# tc08.net
KiCad netlist of a schematic drawn in EAGLE
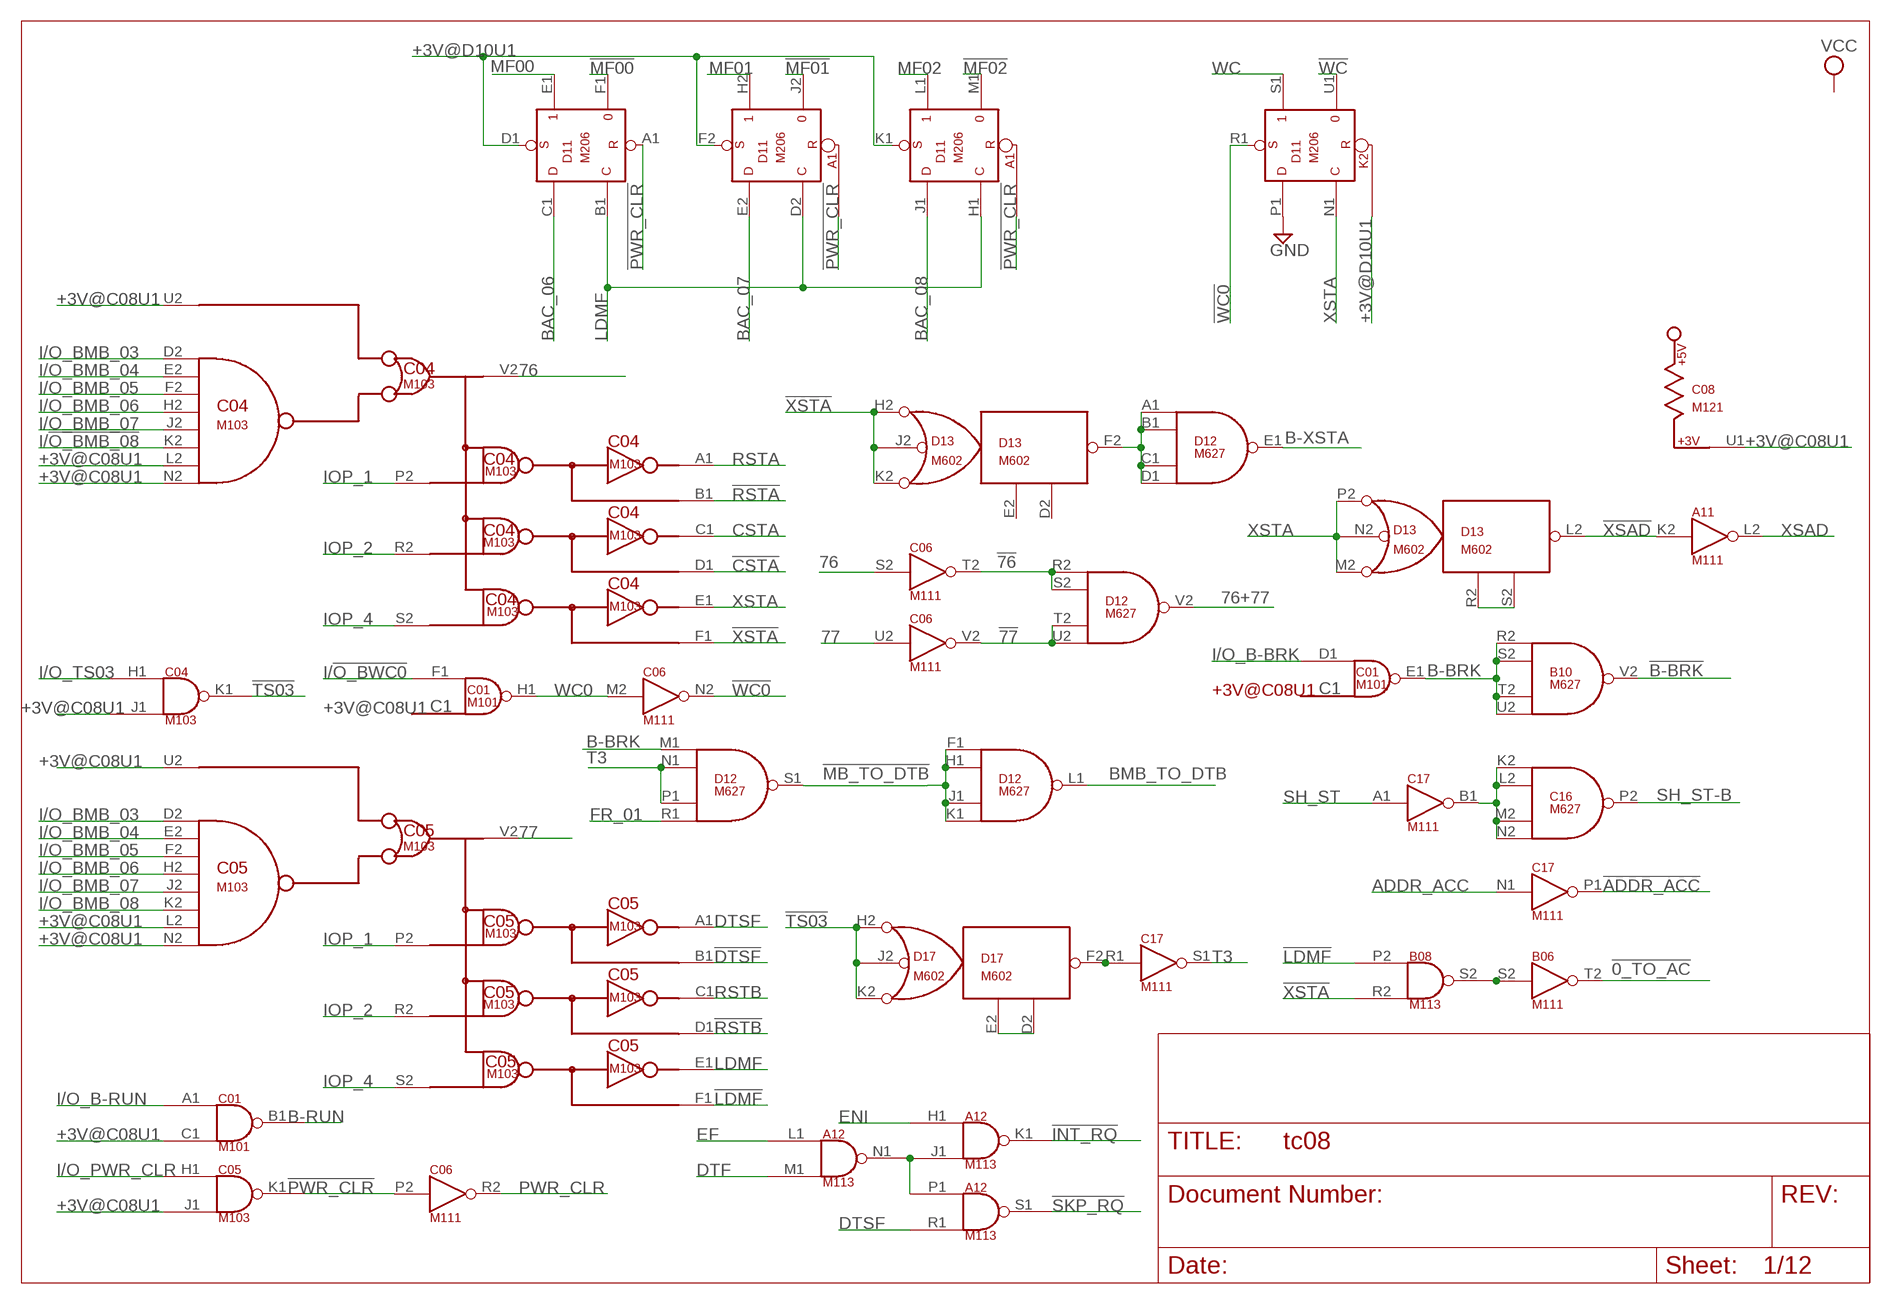
[diagram p0: schematic, sheet 1]
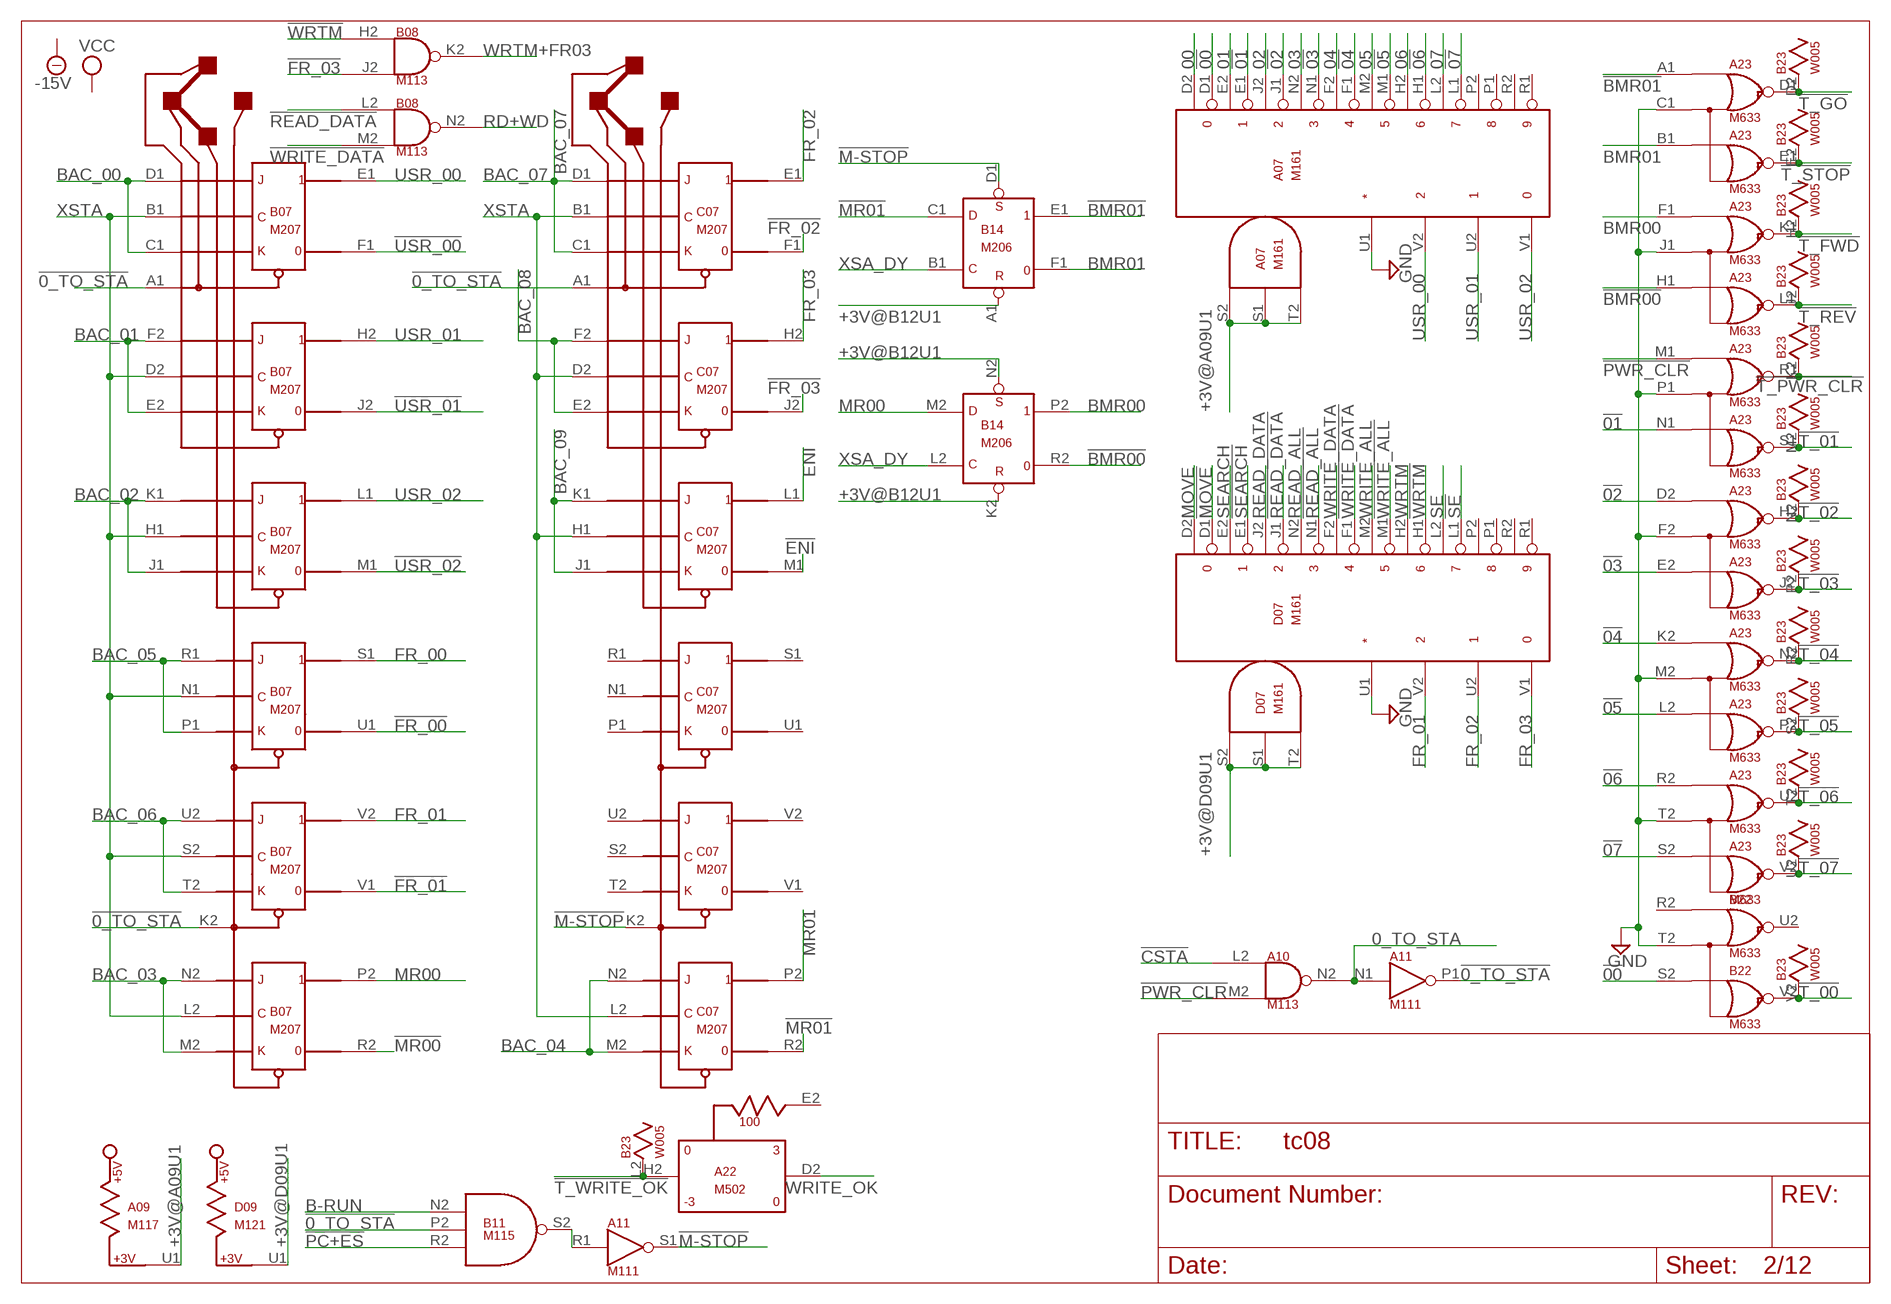
[diagram p1: schematic, sheet 2]
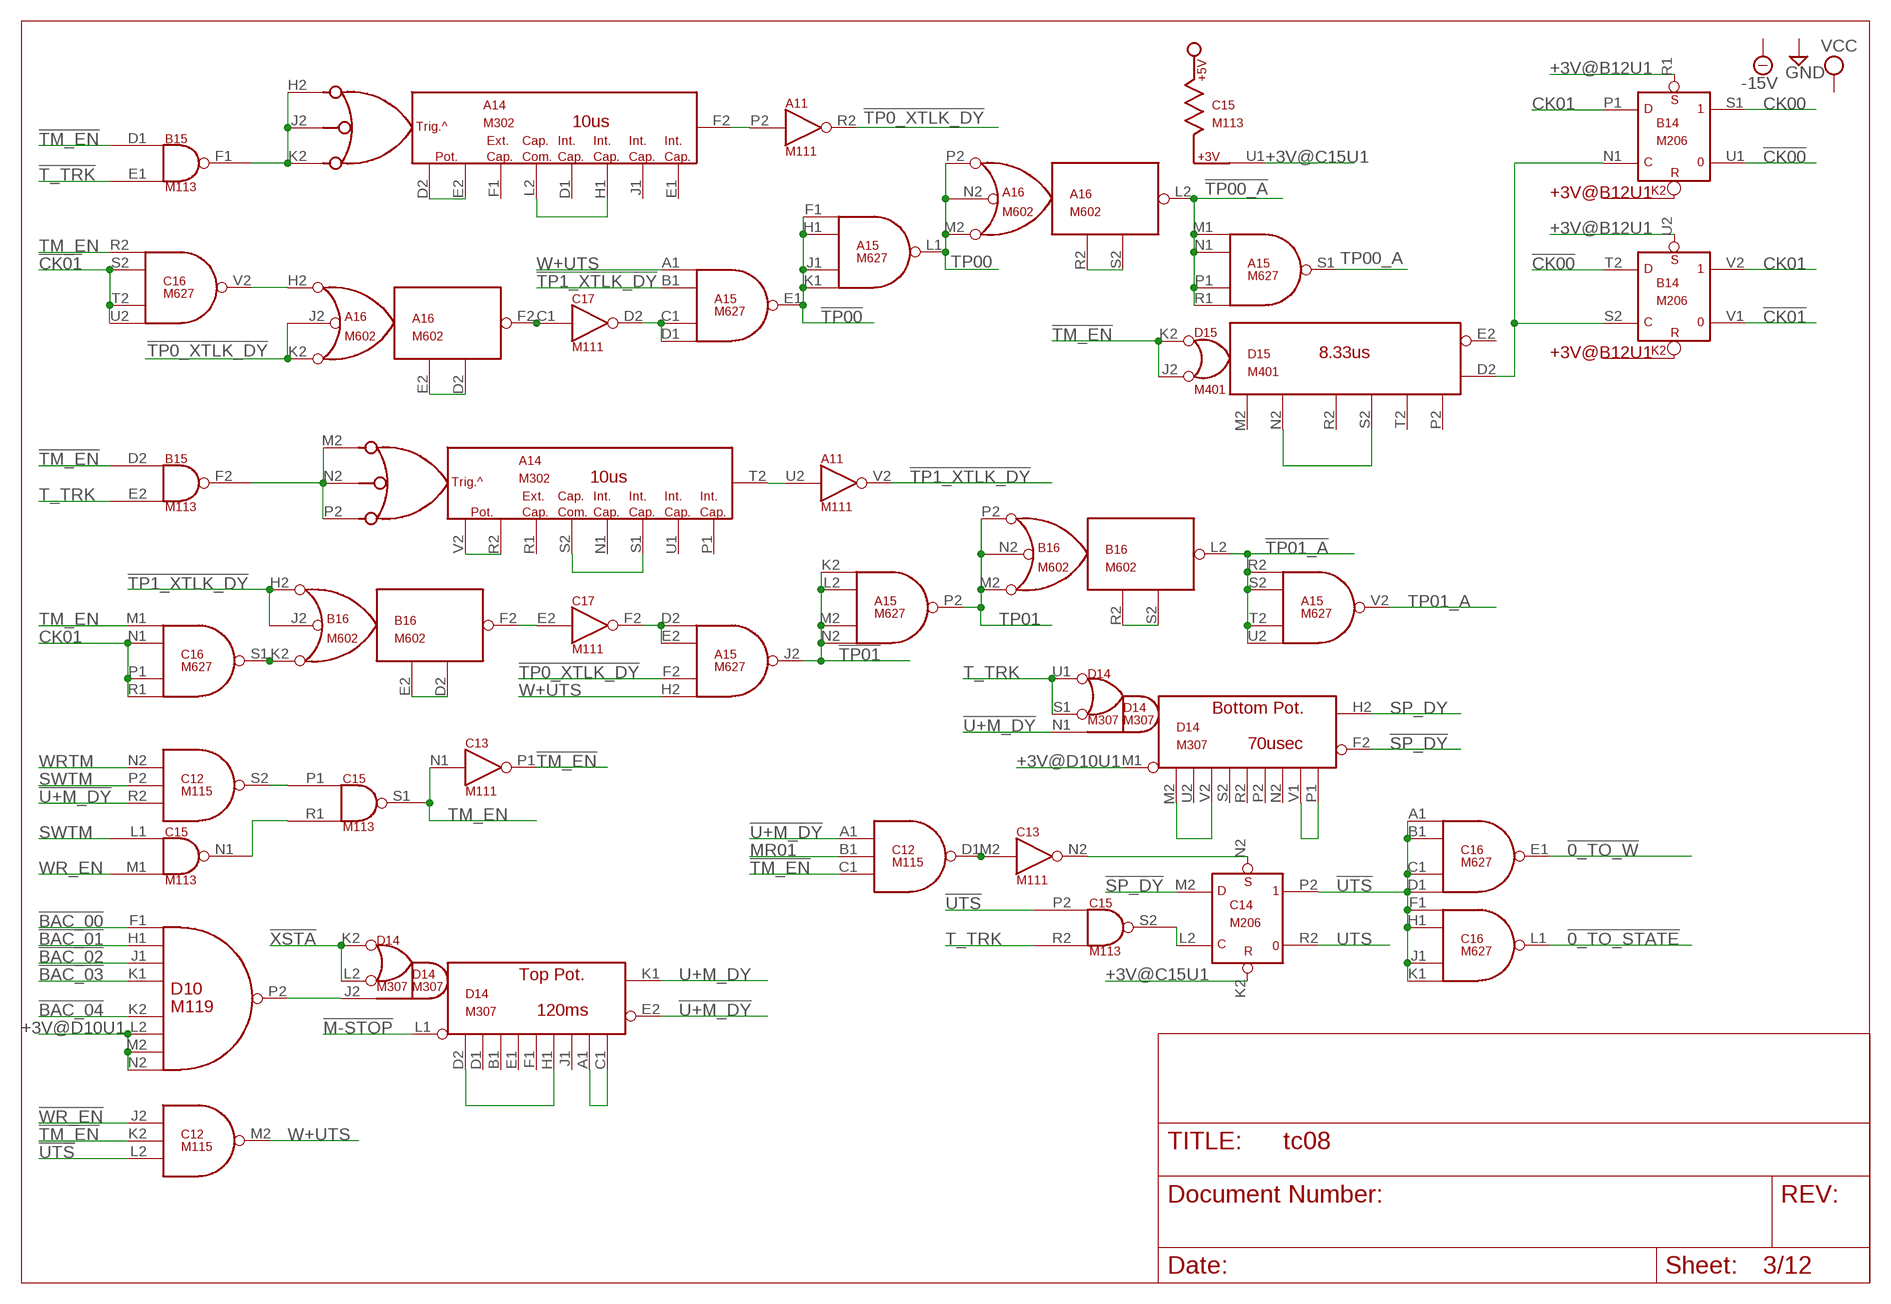
[diagram p2: schematic, sheet 3]
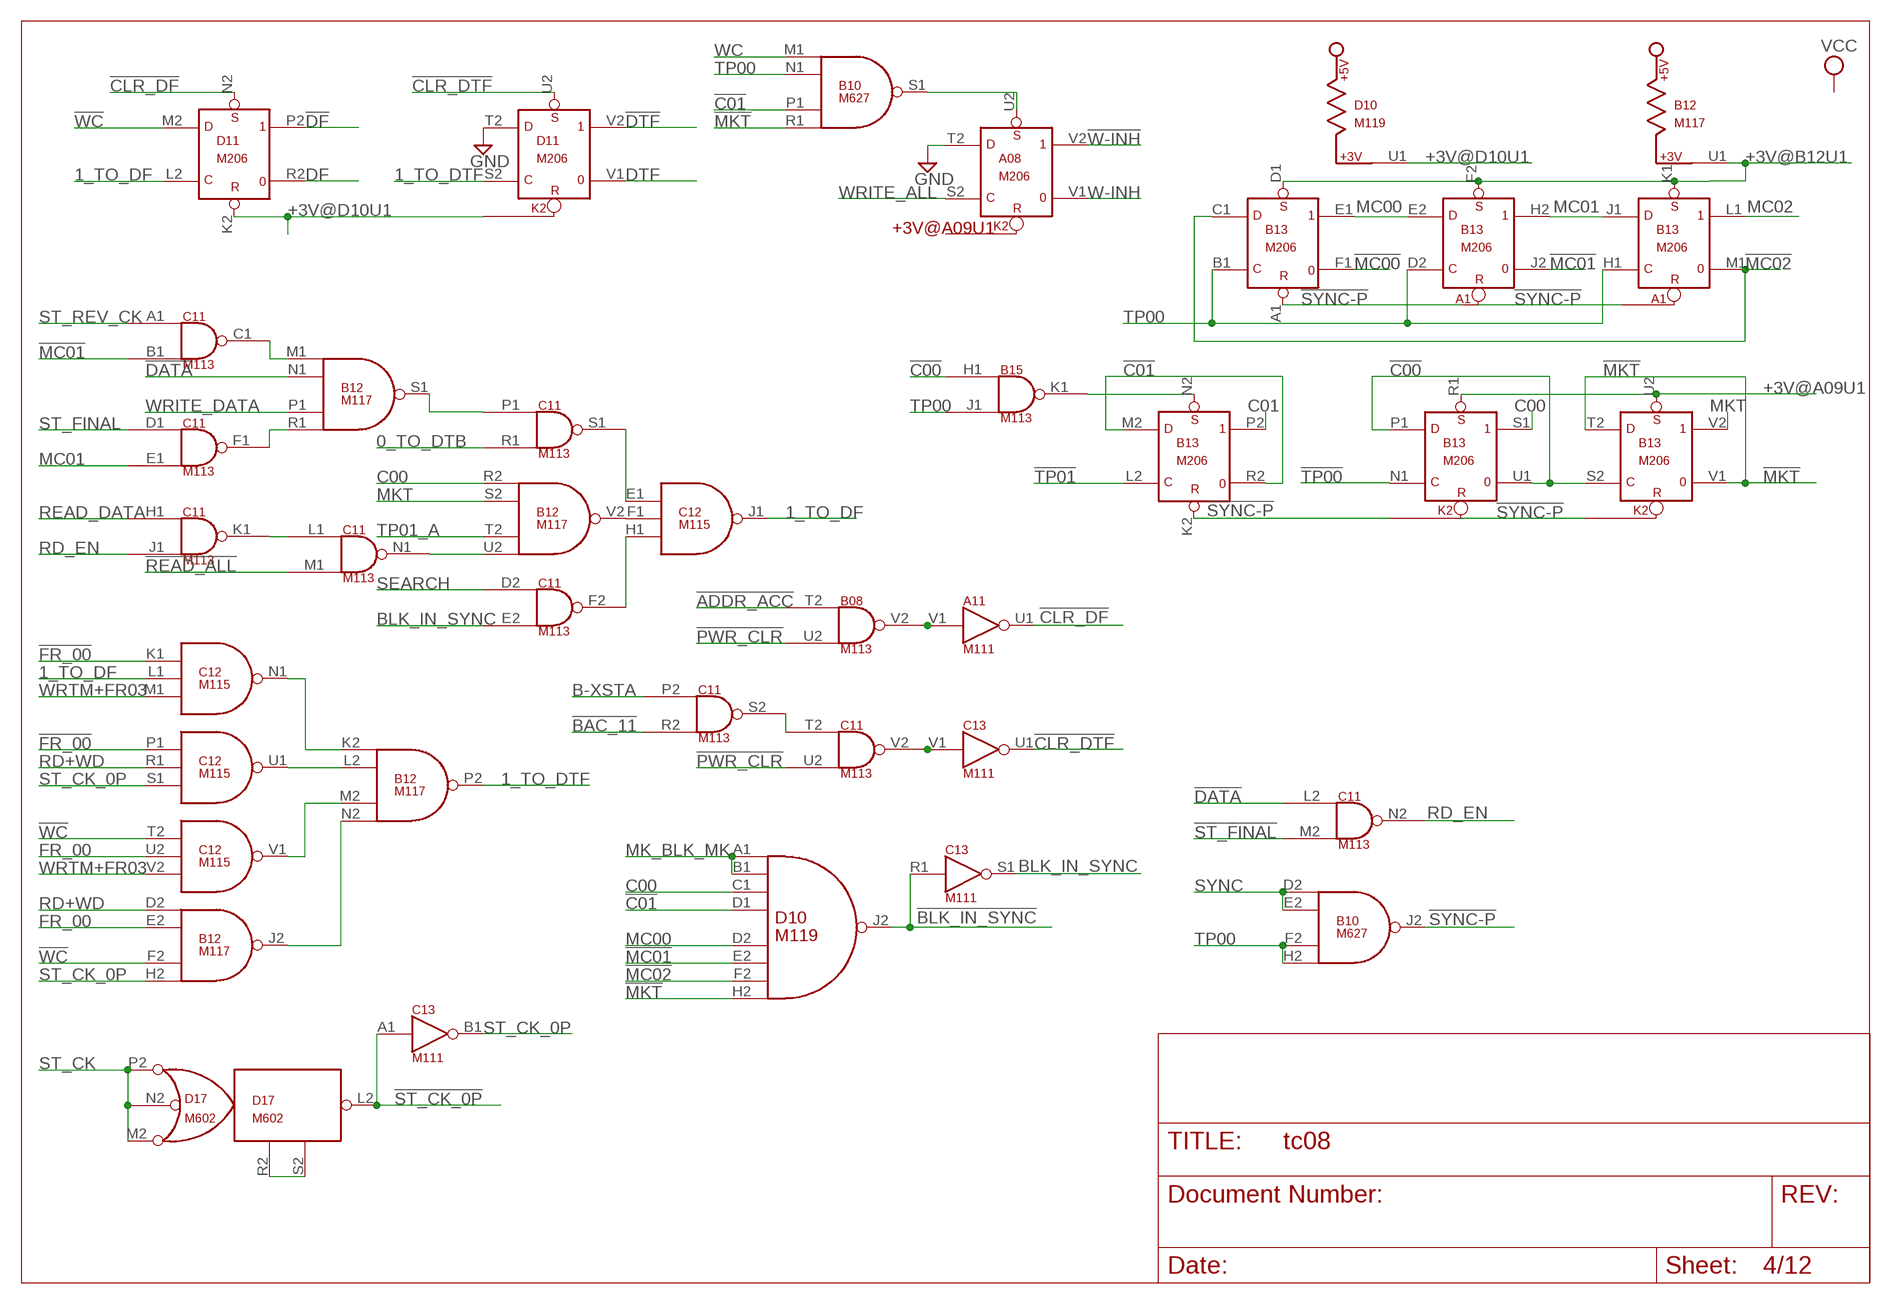
[diagram p3: schematic, sheet 4]
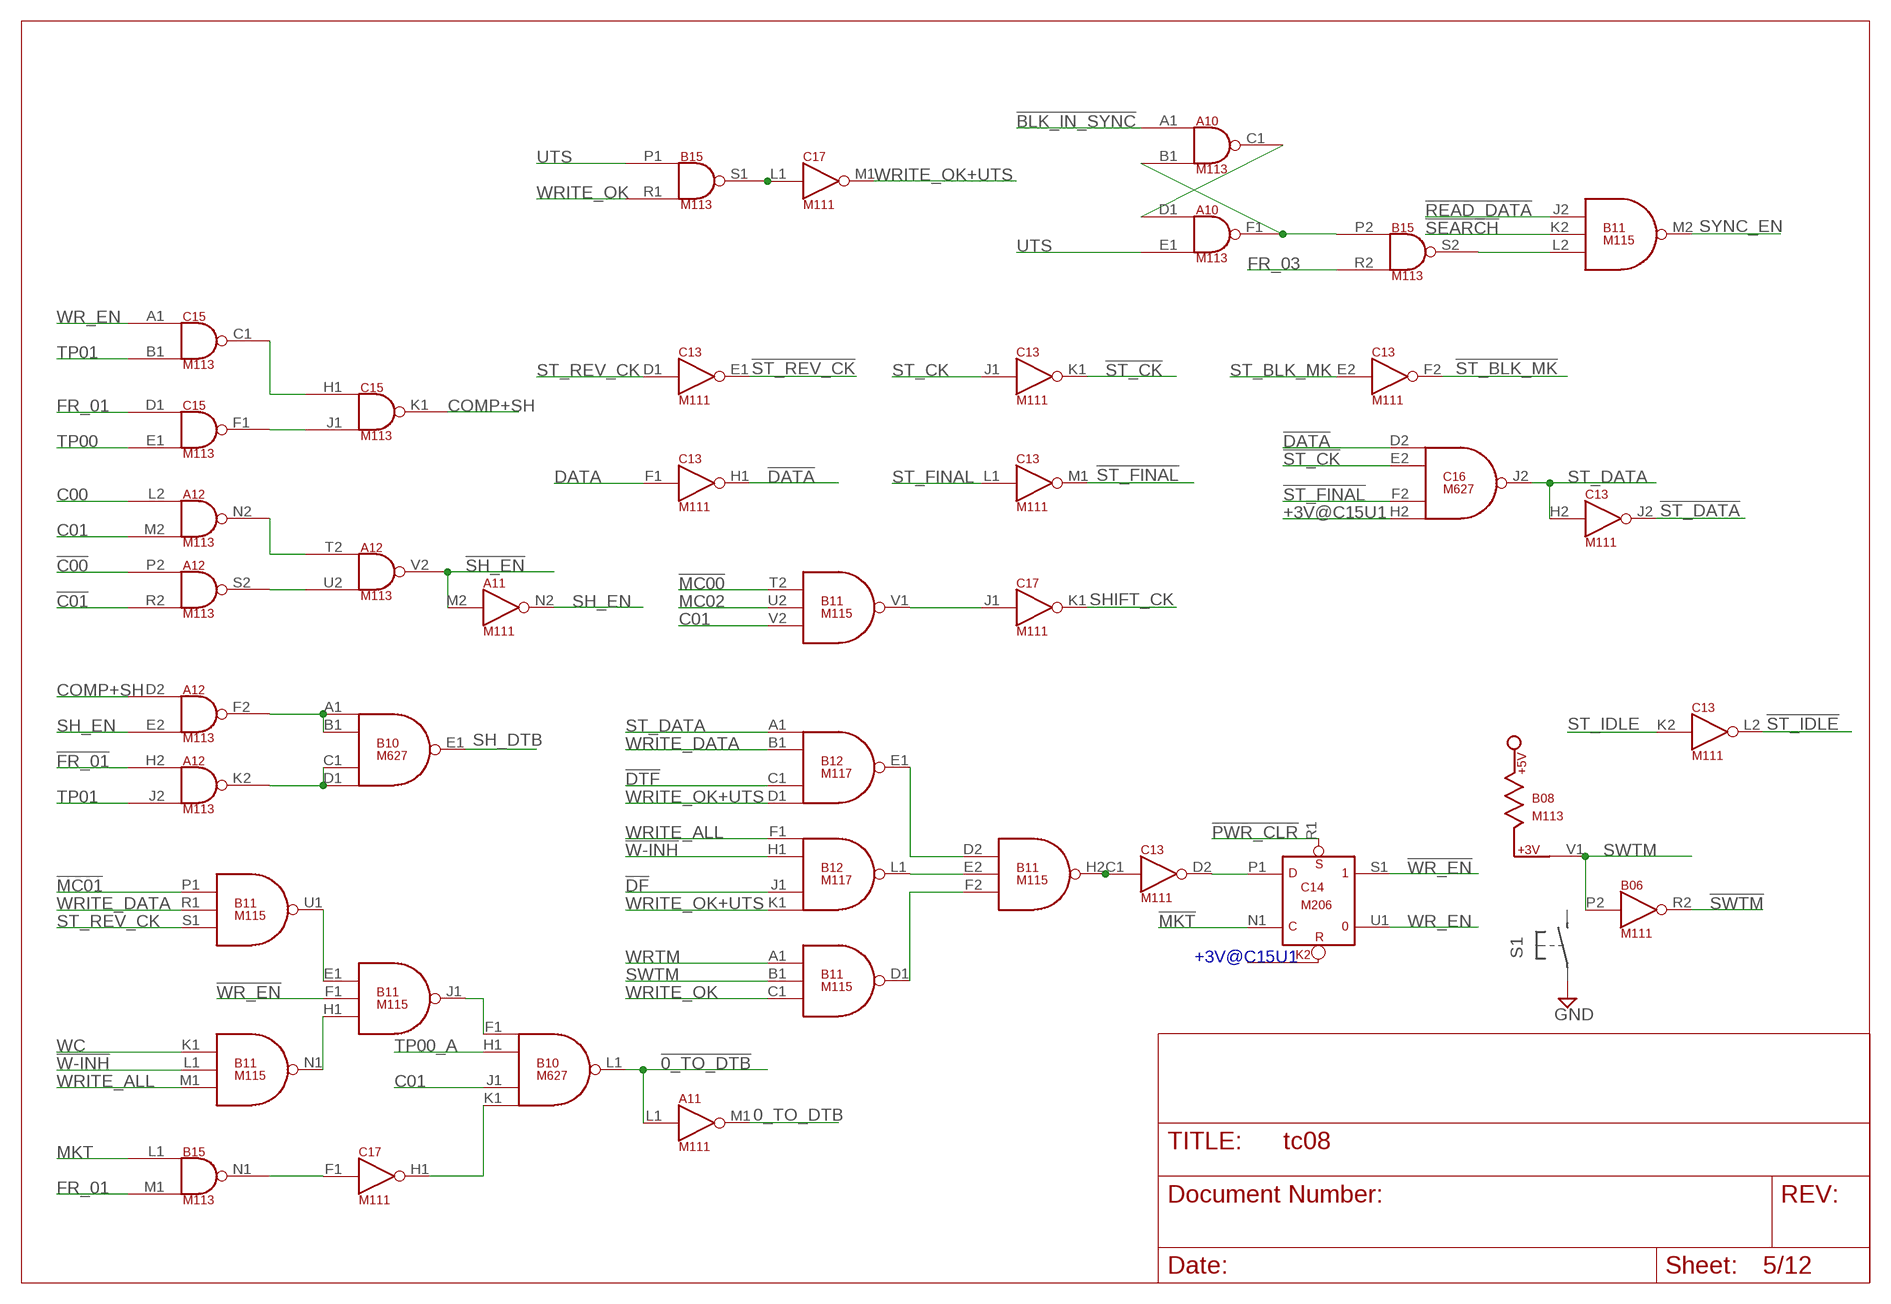
[diagram p4: schematic, sheet 5]
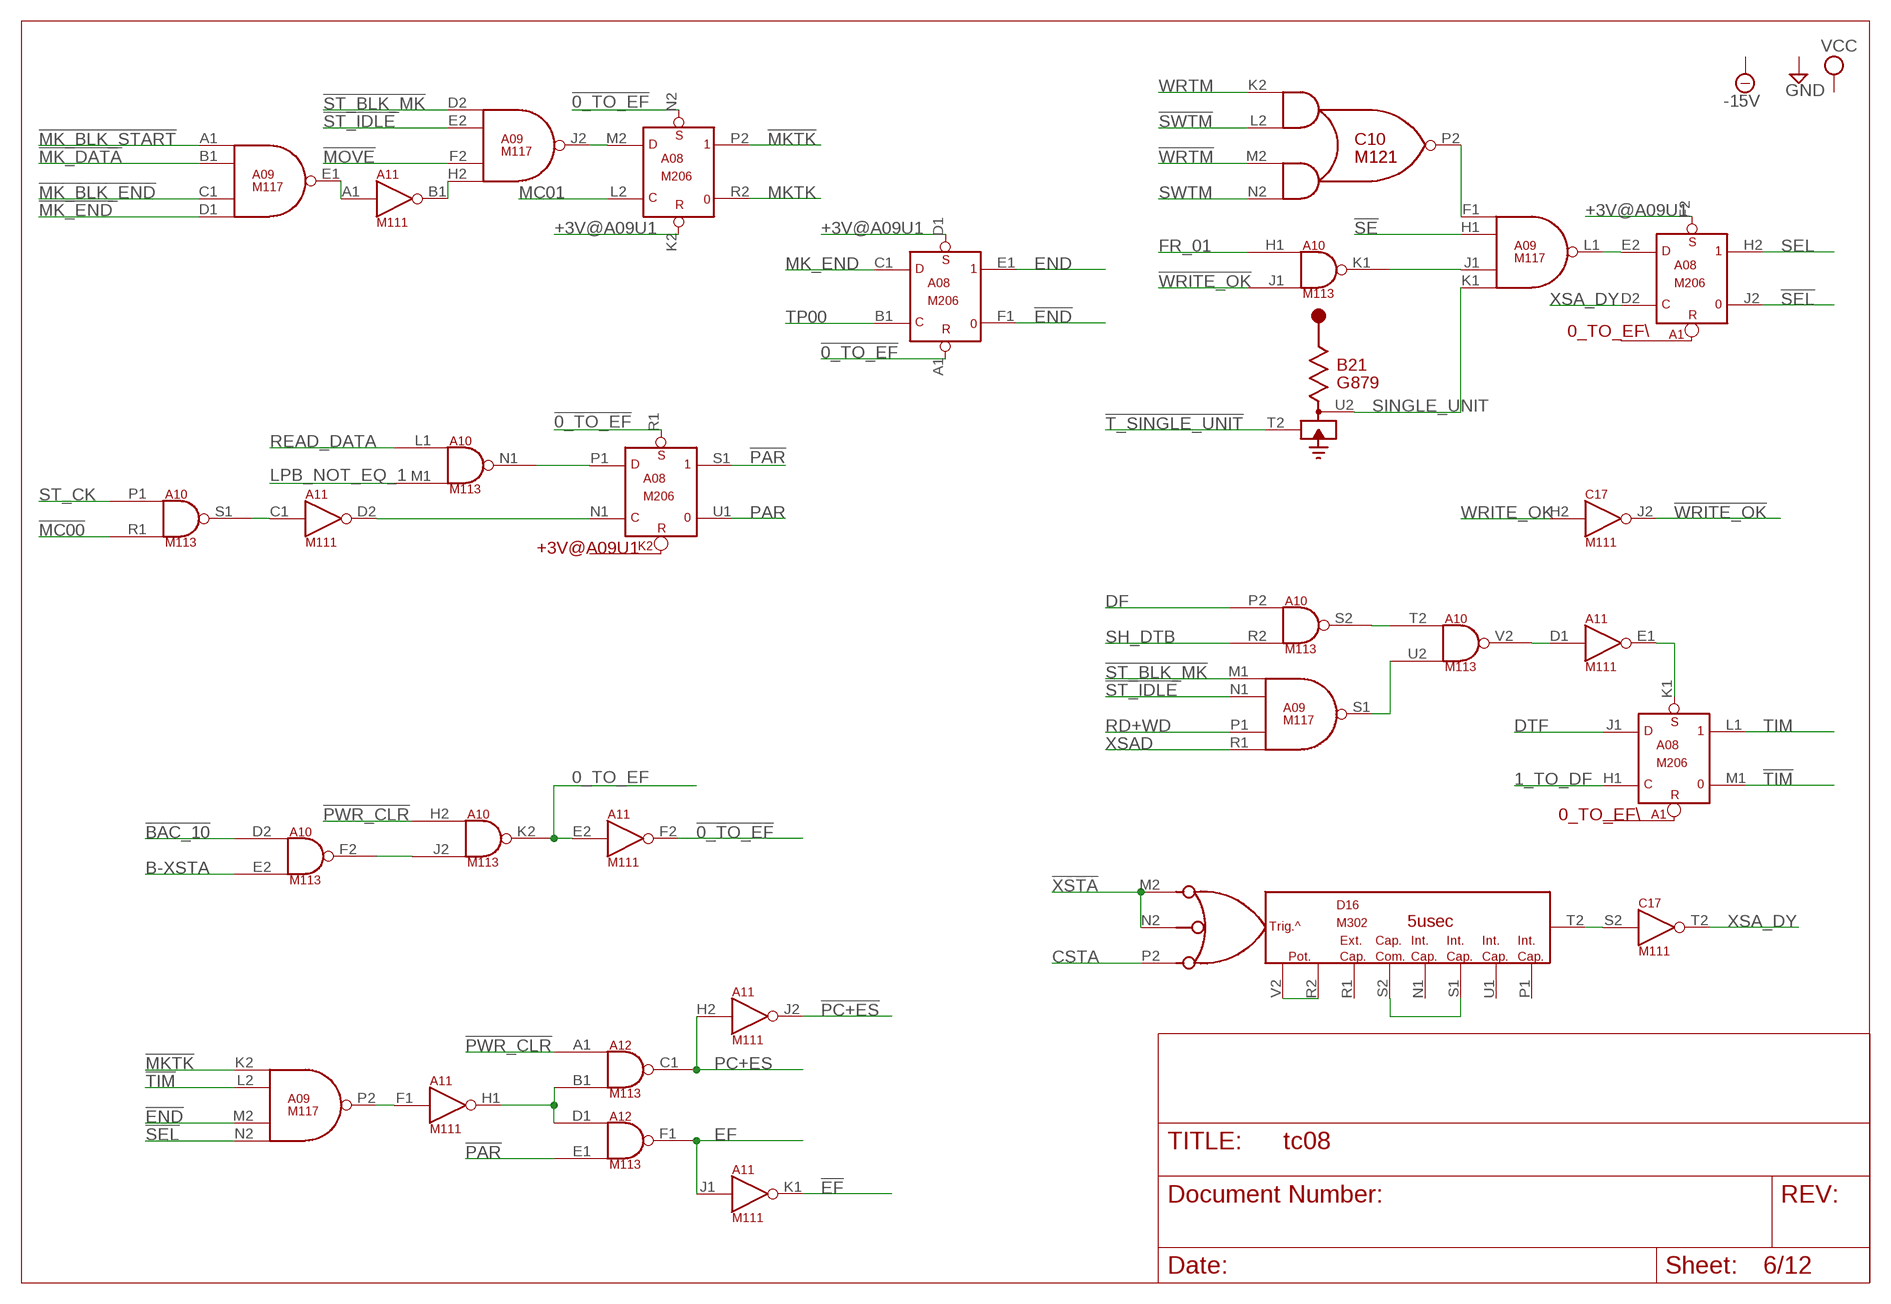
[diagram p5: schematic, sheet 6]
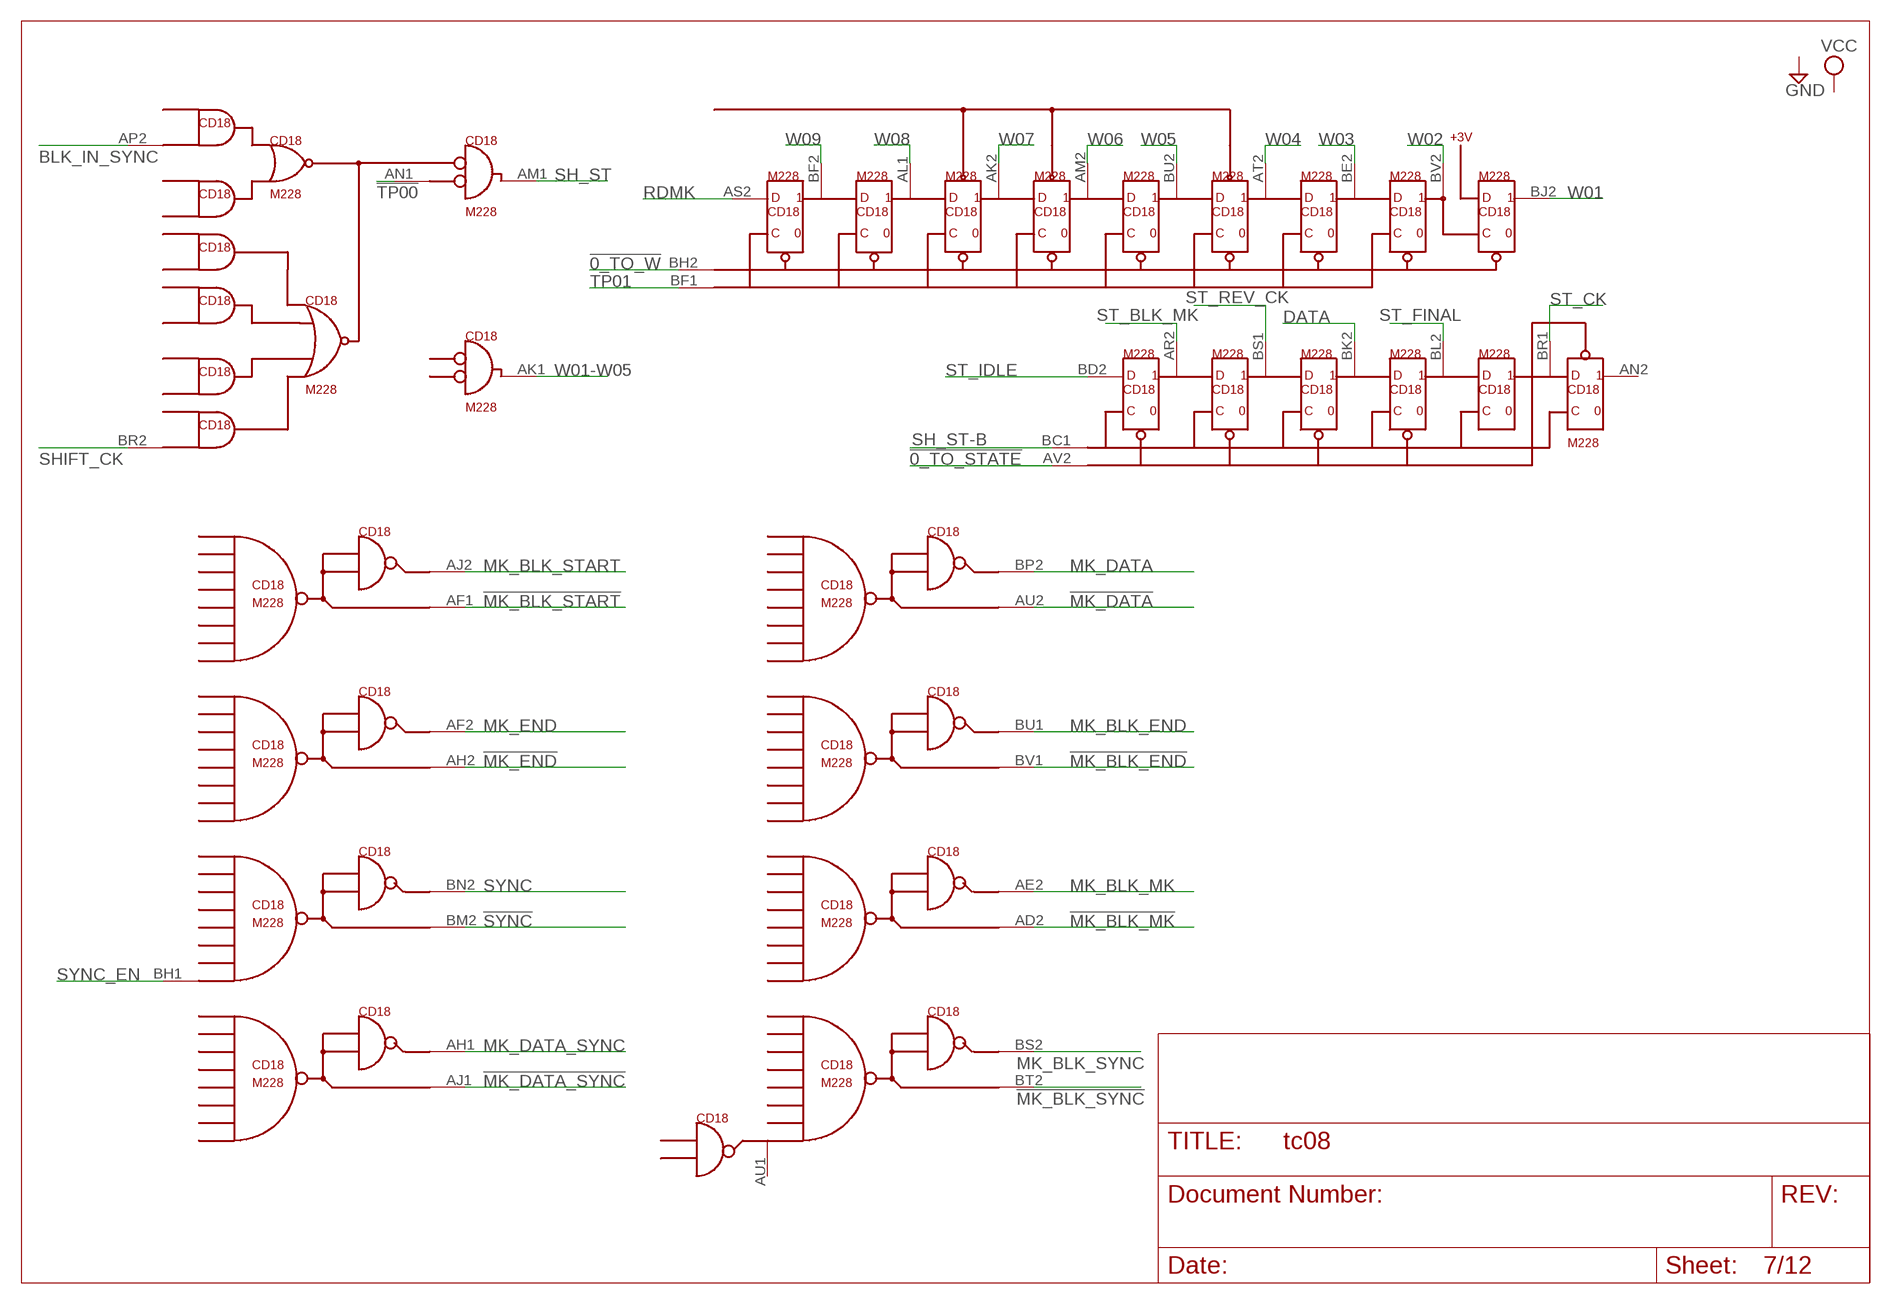
[diagram p6: schematic, sheet 7]
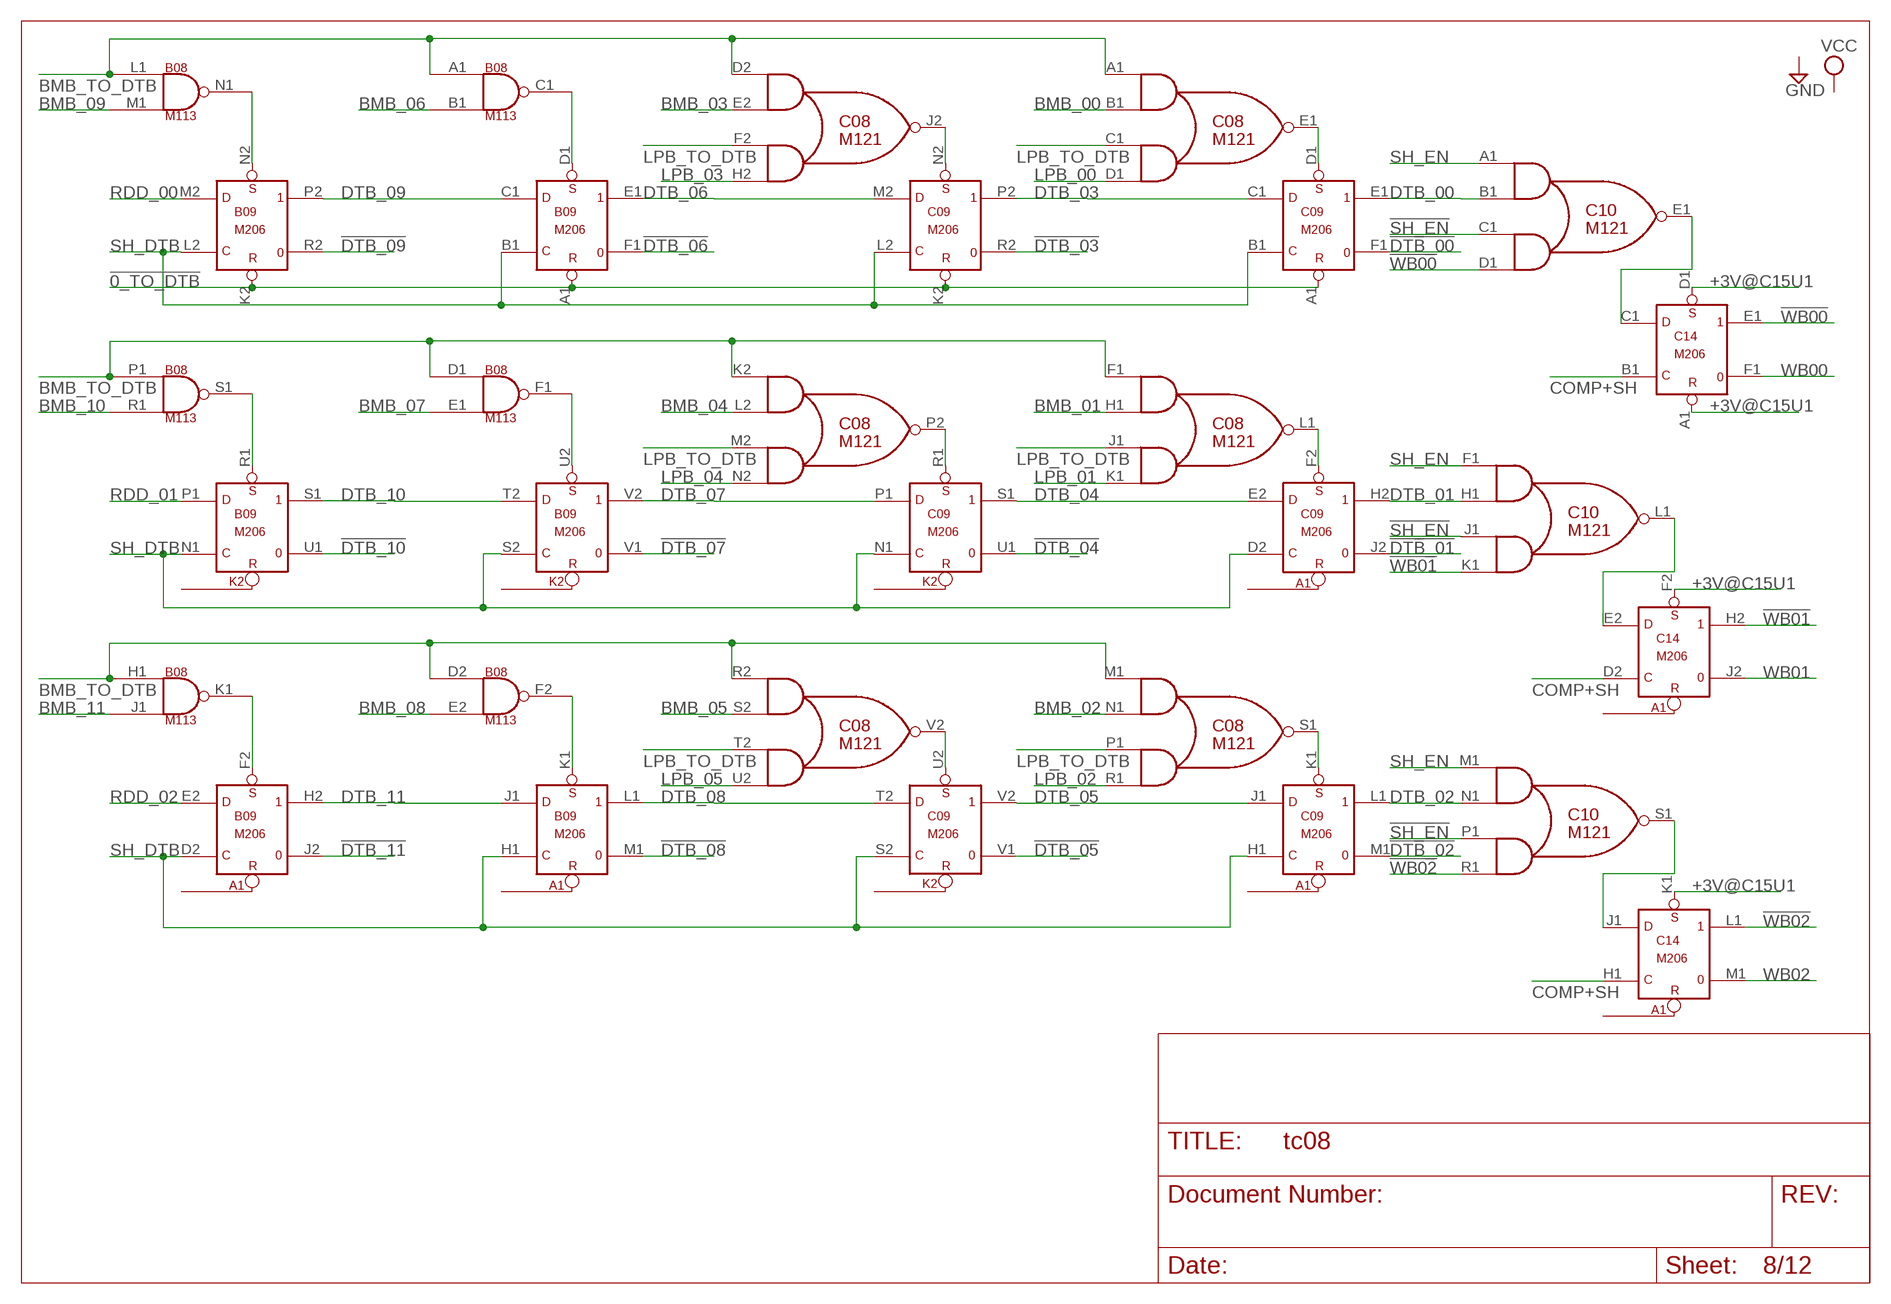
[diagram p7: schematic, sheet 8]
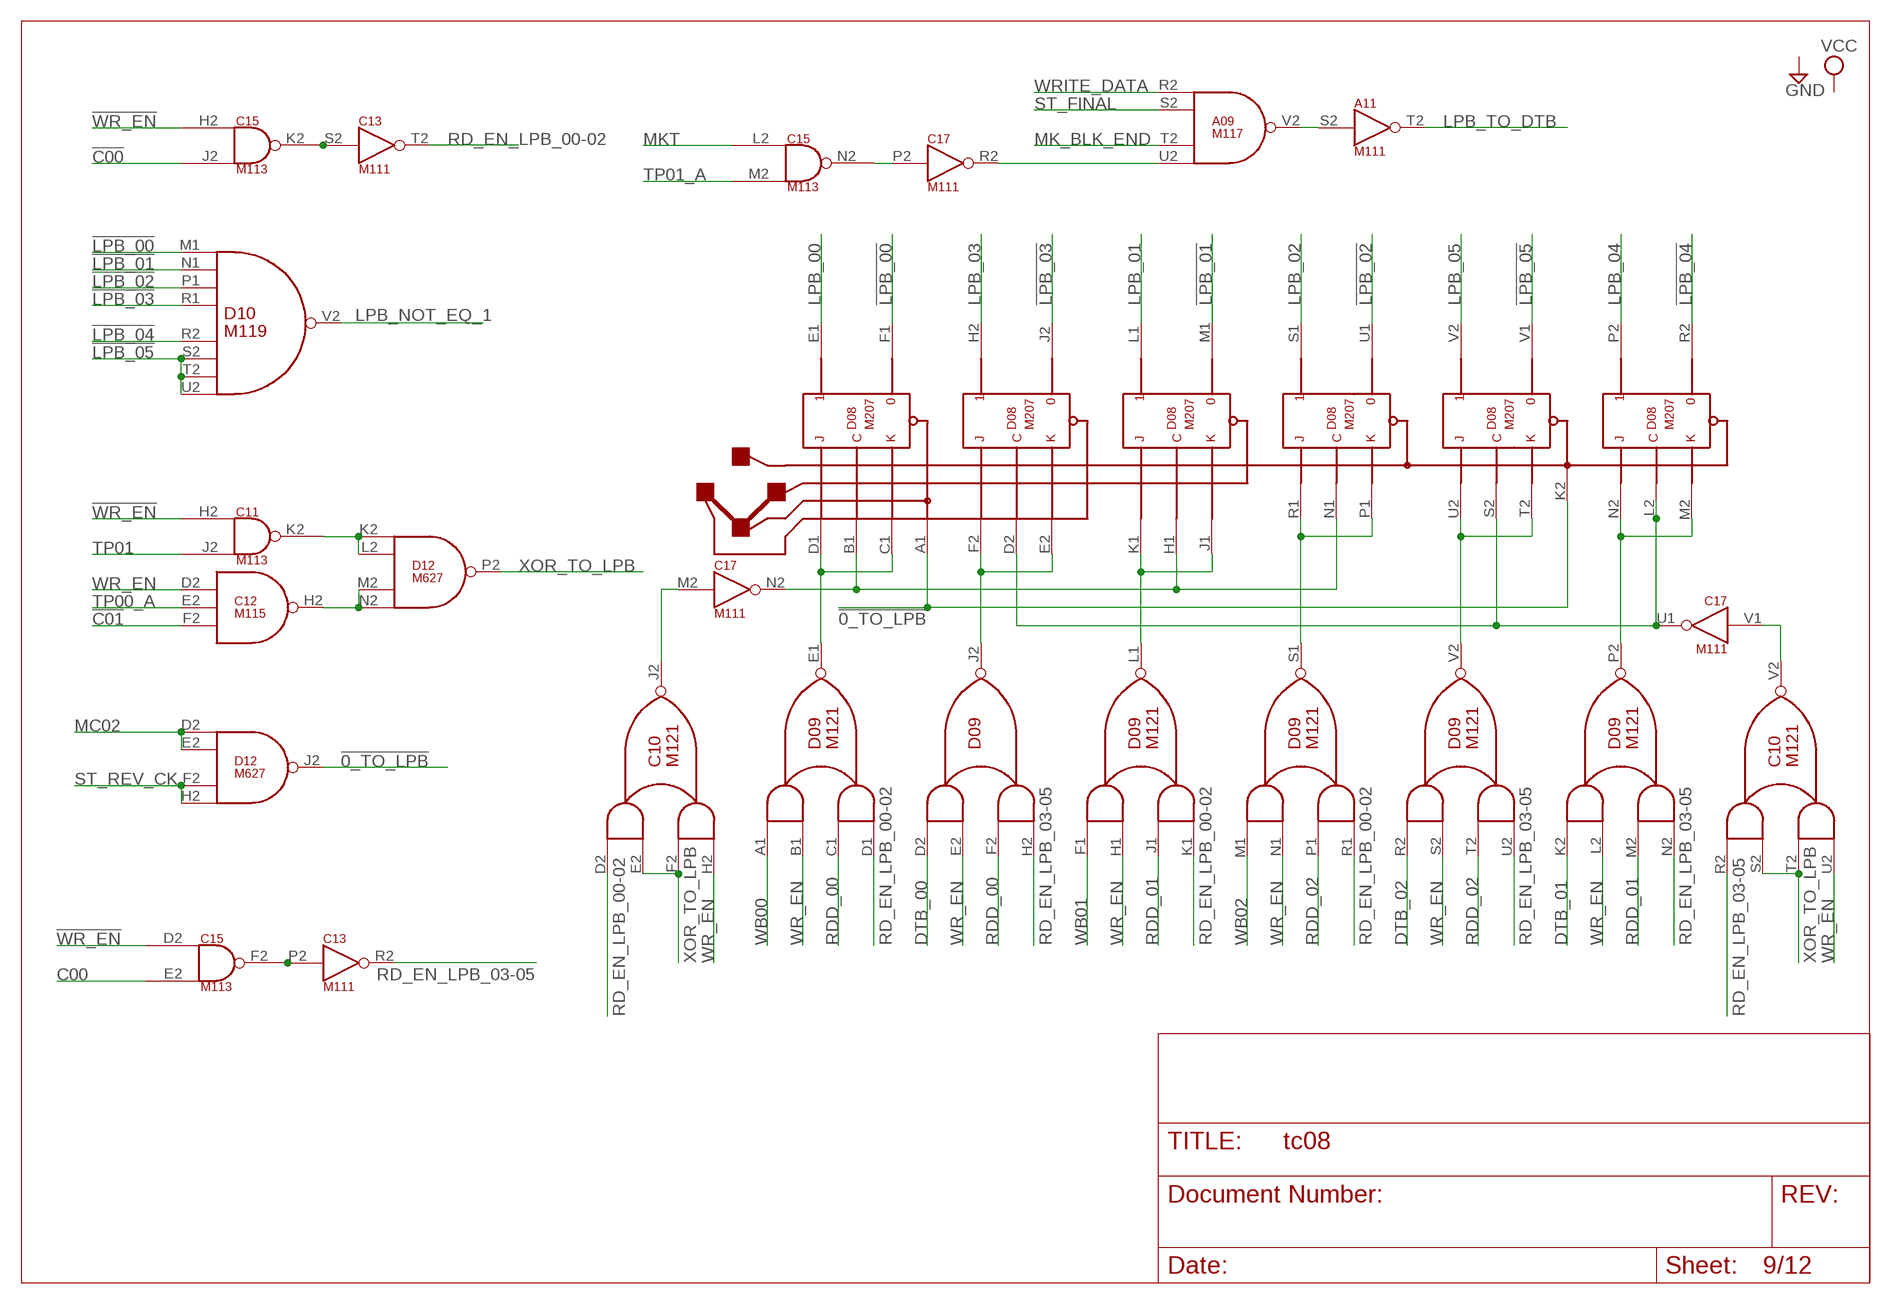
[diagram p8: schematic, sheet 9]
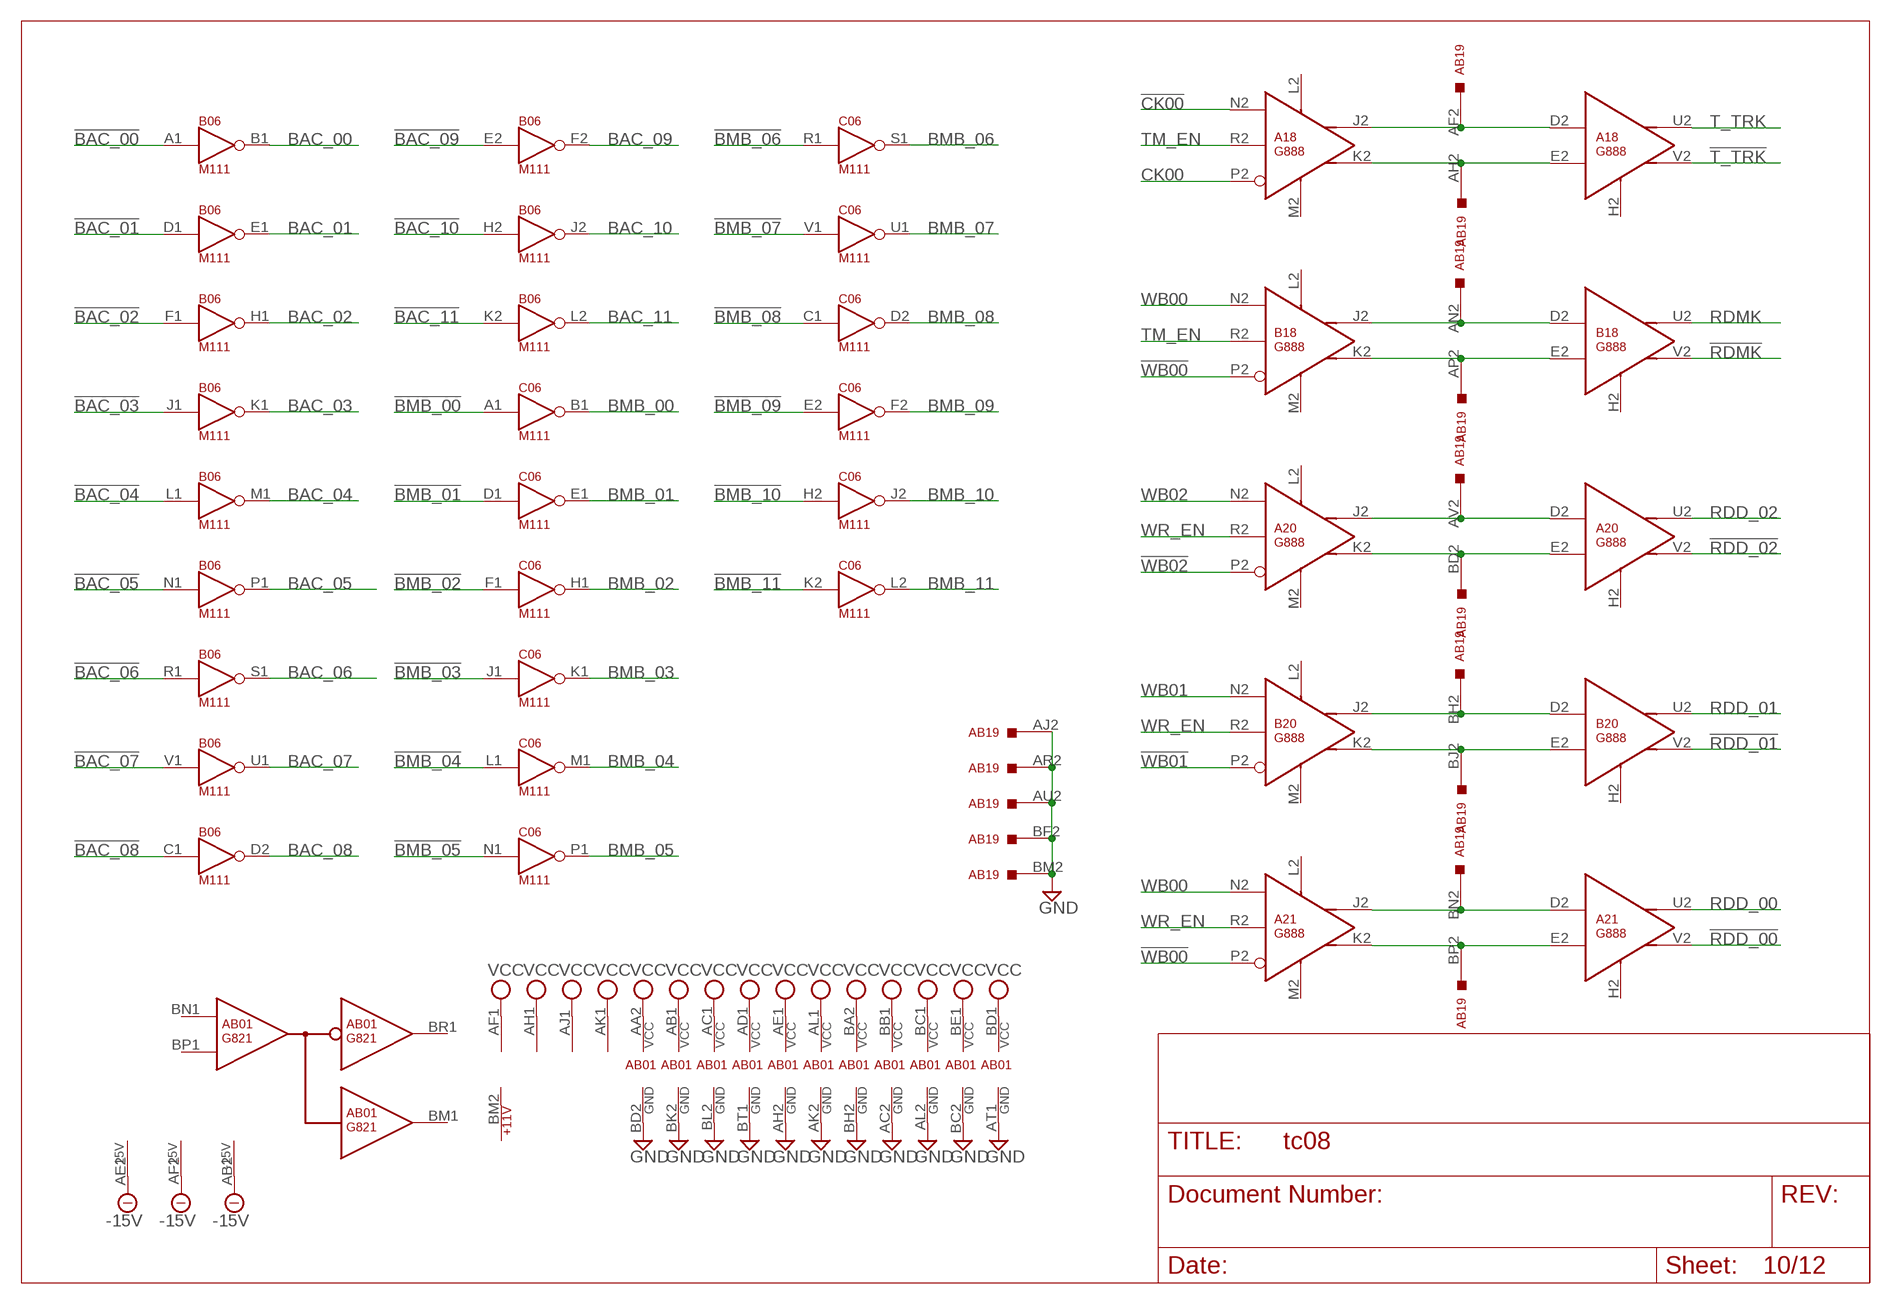
[diagram p9: schematic, sheet 10]
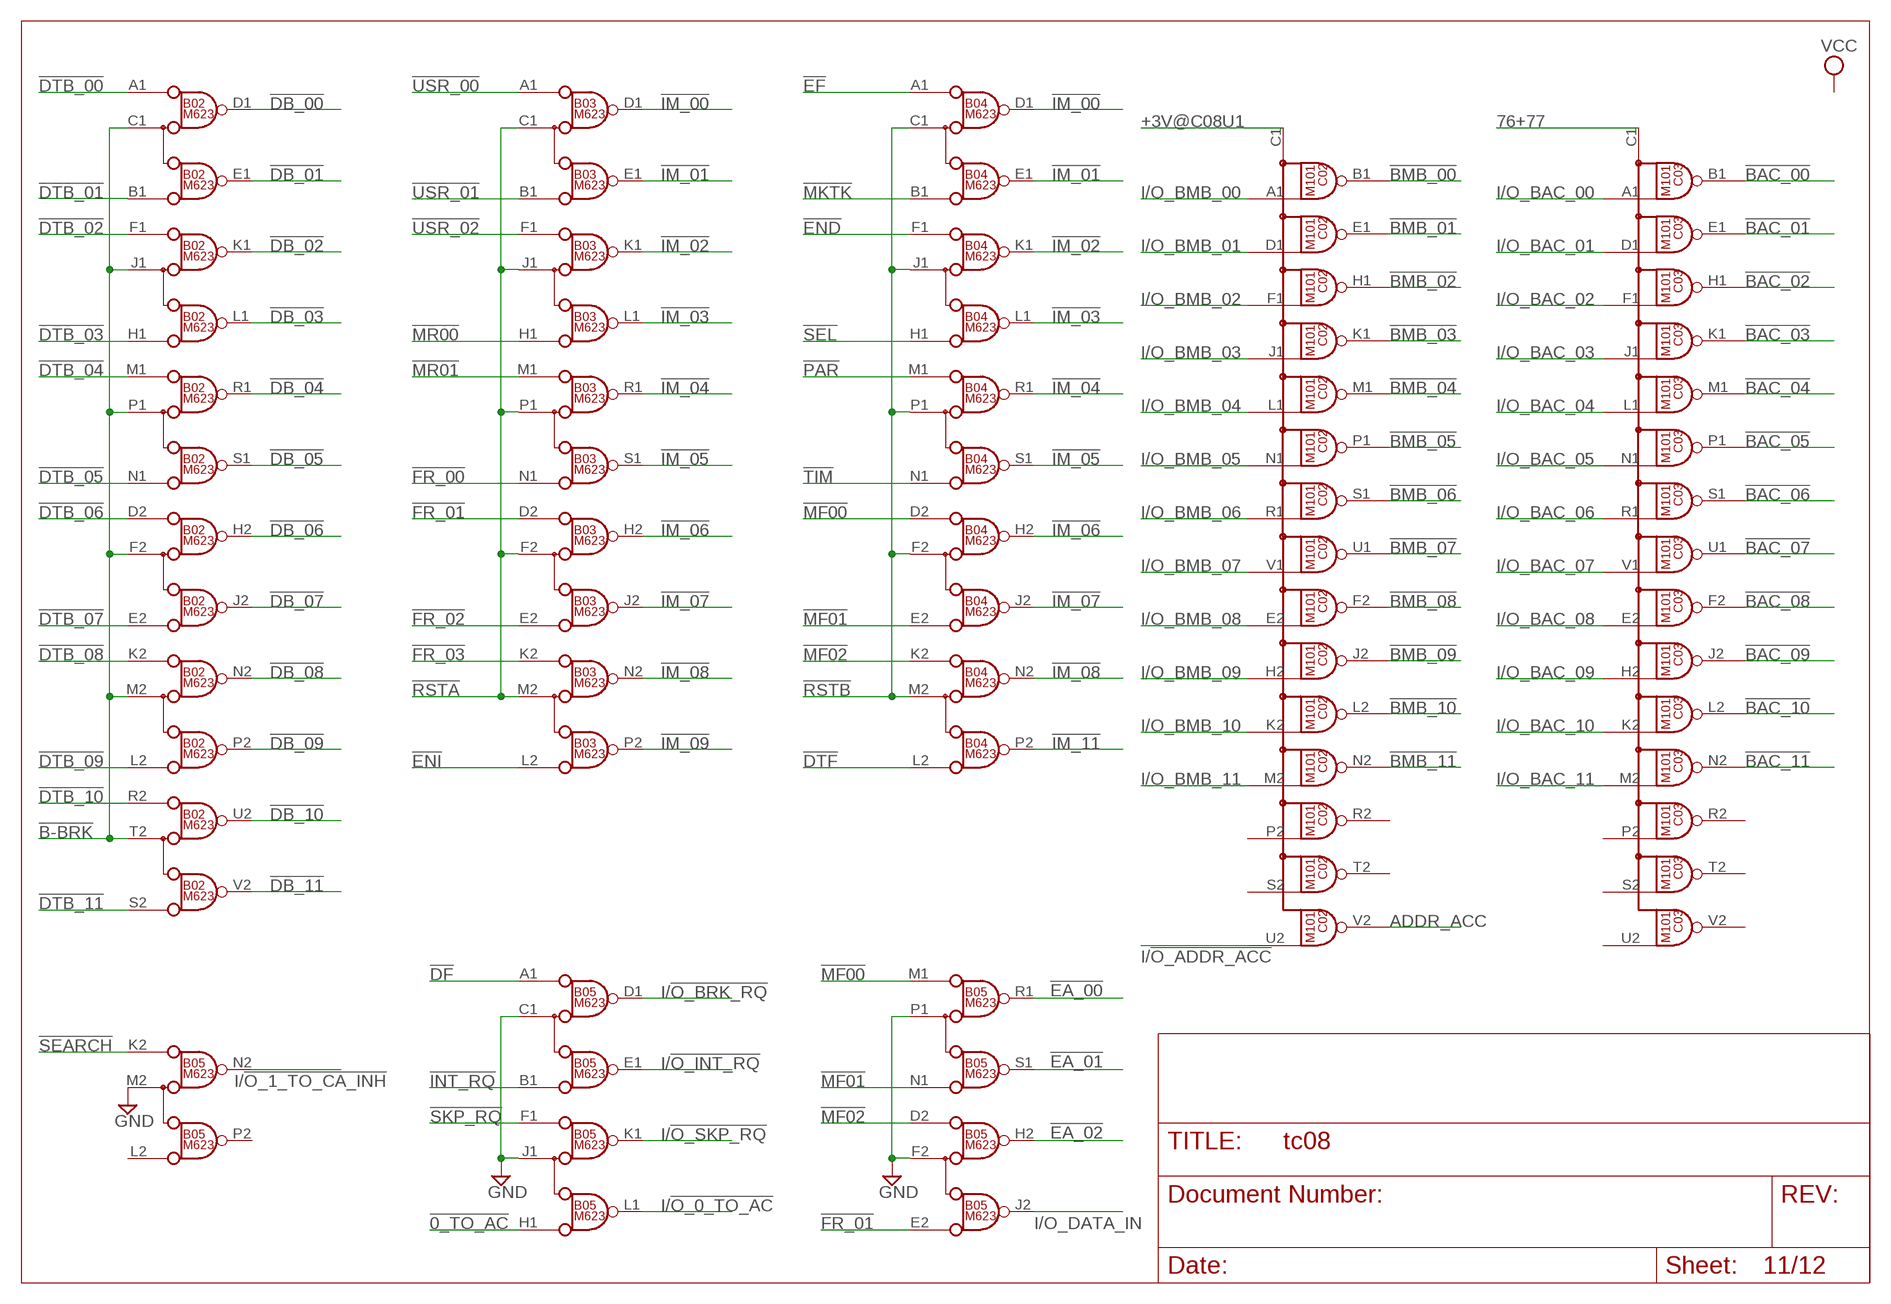
[diagram p10: schematic, sheet 11]
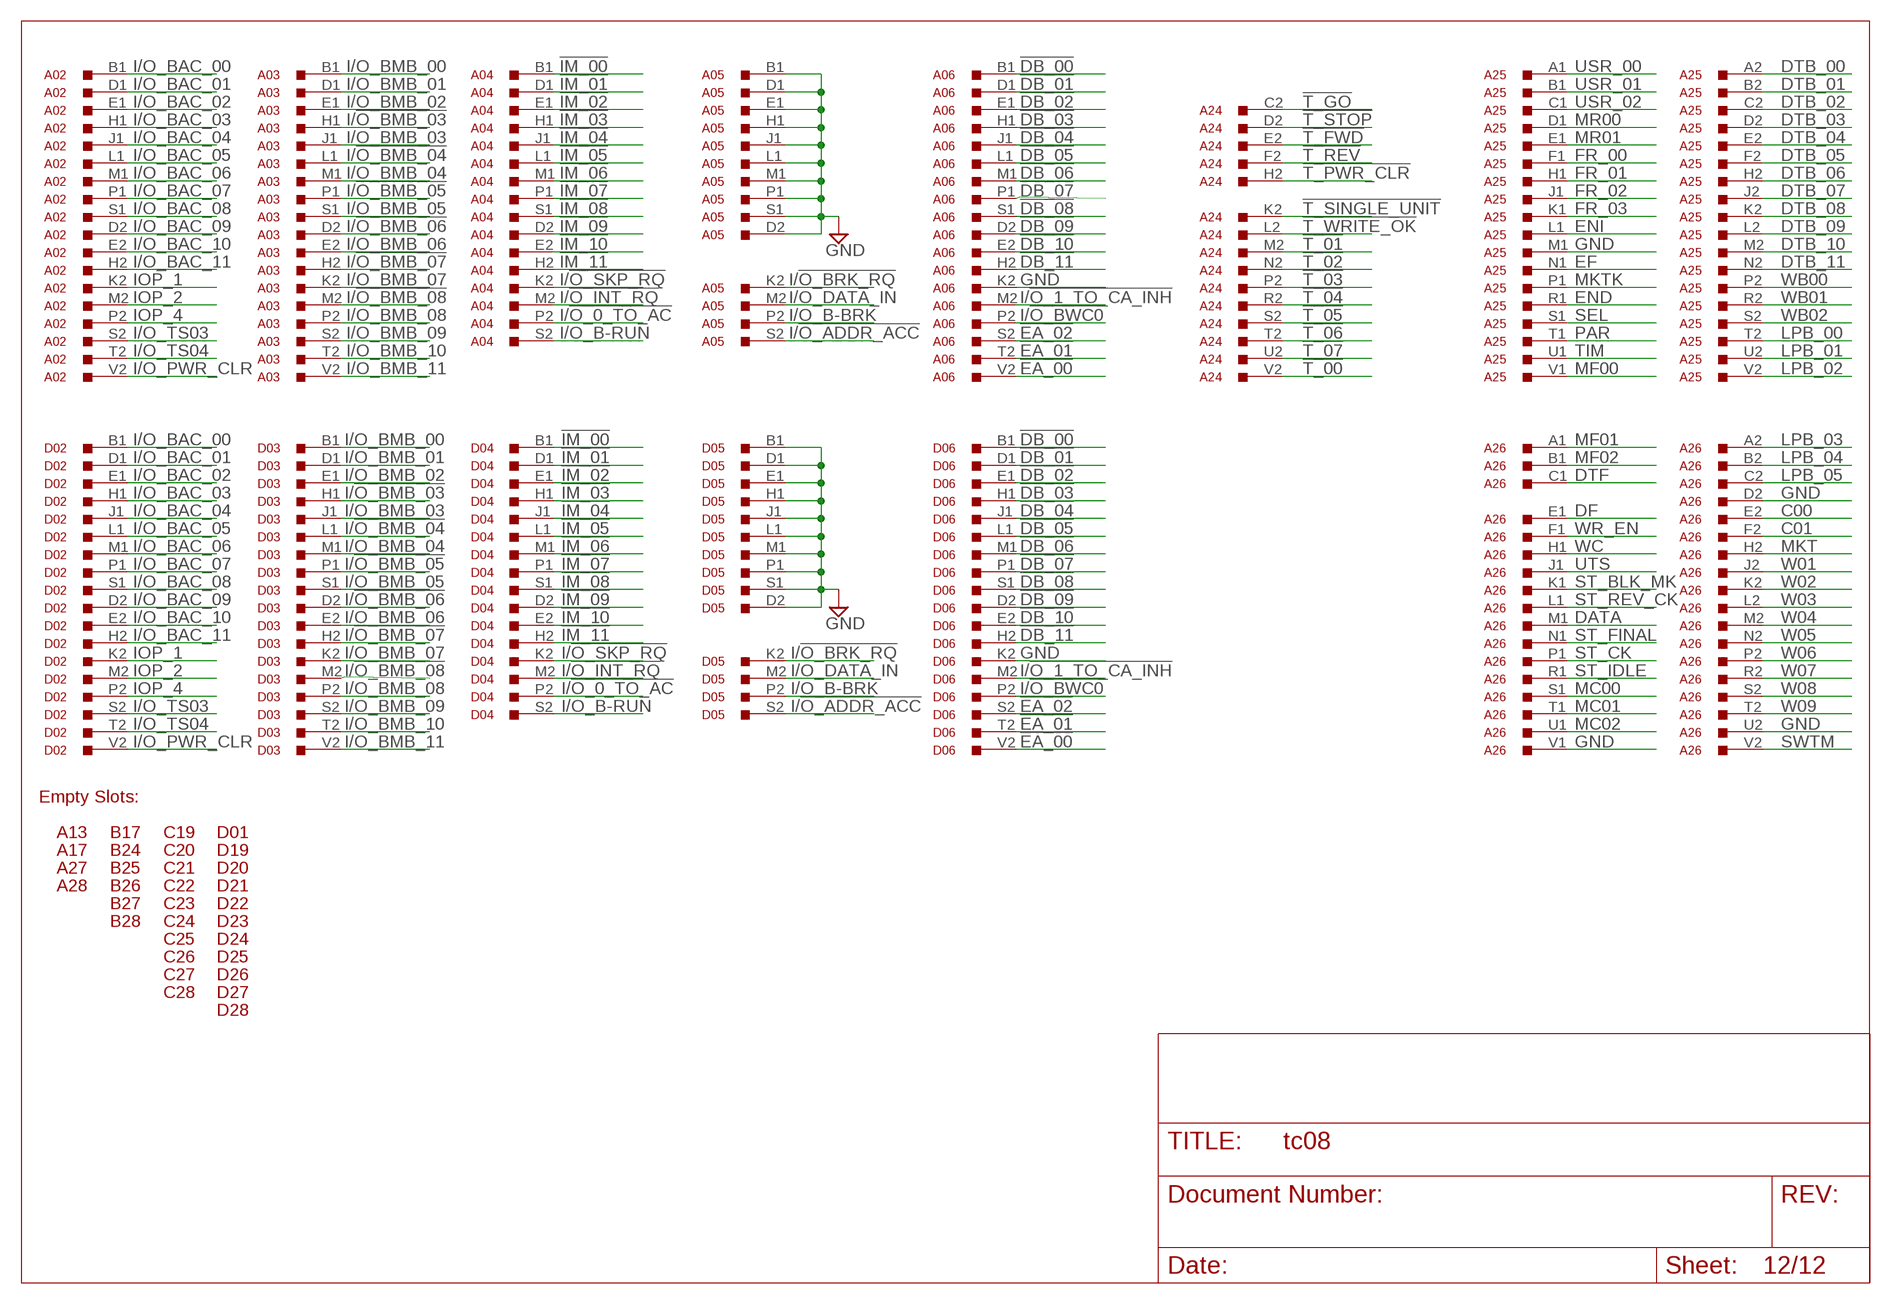
[diagram p11: schematic, sheet 12]

(export (version "E")
  (design (tool "Eeschema 10.0.6"))
  (components
    (comp (ref "B08")
      (value "M113")
      (footprint "eagle-import:H807")
      (libsource (lib "eagle-import") (part "M113"))
    )
    (comp (ref "B09")
      (value "M206")
      (footprint "eagle-import:H807")
      (libsource (lib "eagle-import") (part "M206X"))
    )
    (comp (ref "C08")
      (value "M121")
      (footprint "eagle-import:H807")
      (libsource (lib "eagle-import") (part "M121"))
    )
    (comp (ref "C09")
      (value "M206")
      (footprint "eagle-import:H807")
      (libsource (lib "eagle-import") (part "M206X"))
    )
    (comp (ref "C10")
      (value "M121")
      (footprint "eagle-import:H807")
      (libsource (lib "eagle-import") (part "M121"))
    )
    (comp (ref "C14")
      (value "M206")
      (footprint "eagle-import:H807")
      (libsource (lib "eagle-import") (part "M206X"))
    )
    (comp (ref "A02")
      (value "M903")
      (footprint "eagle-import:H807")
      (libsource (lib "eagle-import") (part "M903"))
    )
    (comp (ref "A03")
      (value "M903")
      (footprint "eagle-import:H807")
      (libsource (lib "eagle-import") (part "M903"))
    )
    (comp (ref "A04")
      (value "M903")
      (footprint "eagle-import:H807")
      (libsource (lib "eagle-import") (part "M903"))
    )
    (comp (ref "A05")
      (value "M903")
      (footprint "eagle-import:H807")
      (libsource (lib "eagle-import") (part "M903"))
    )
    (comp (ref "A06")
      (value "M903")
      (footprint "eagle-import:H807")
      (libsource (lib "eagle-import") (part "M903"))
    )
    (comp (ref "A13")
      (value "H807")
      (footprint "eagle-import:H807")
      (libsource (lib "eagle-import") (part "H807"))
    )
    (comp (ref "A17")
      (value "H807")
      (footprint "eagle-import:H807")
      (libsource (lib "eagle-import") (part "H807"))
    )
    (comp (ref "A24")
      (value "W023")
      (footprint "eagle-import:H807")
      (libsource (lib "eagle-import") (part "W023"))
    )
    (comp (ref "A25")
      (value "M916")
      (footprint "eagle-import:H807")
      (libsource (lib "eagle-import") (part "M916"))
    )
    (comp (ref "A26")
      (value "M916")
      (footprint "eagle-import:H807")
      (libsource (lib "eagle-import") (part "M916"))
    )
    (comp (ref "A27")
      (value "H807")
      (footprint "eagle-import:H807")
      (libsource (lib "eagle-import") (part "H807"))
    )
    (comp (ref "A28")
      (value "H807")
      (footprint "eagle-import:H807")
      (libsource (lib "eagle-import") (part "H807"))
    )
    (comp (ref "B17")
      (value "H807")
      (footprint "eagle-import:H807")
      (libsource (lib "eagle-import") (part "H807"))
    )
    (comp (ref "B24")
      (value "H807")
      (footprint "eagle-import:H807")
      (libsource (lib "eagle-import") (part "H807"))
    )
    (comp (ref "B25")
      (value "H807")
      (footprint "eagle-import:H807")
      (libsource (lib "eagle-import") (part "H807"))
    )
    (comp (ref "B26")
      (value "H807")
      (footprint "eagle-import:H807")
      (libsource (lib "eagle-import") (part "H807"))
    )
    (comp (ref "B27")
      (value "H807")
      (footprint "eagle-import:H807")
      (libsource (lib "eagle-import") (part "H807"))
    )
    (comp (ref "B28")
      (value "H807")
      (footprint "eagle-import:H807")
      (libsource (lib "eagle-import") (part "H807"))
    )
    (comp (ref "C19")
      (value "H807")
      (footprint "eagle-import:H807")
      (libsource (lib "eagle-import") (part "H807"))
    )
    (comp (ref "C20")
      (value "H807")
      (footprint "eagle-import:H807")
      (libsource (lib "eagle-import") (part "H807"))
    )
    (comp (ref "C21")
      (value "H807")
      (footprint "eagle-import:H807")
      (libsource (lib "eagle-import") (part "H807"))
    )
    (comp (ref "C22")
      (value "H807")
      (footprint "eagle-import:H807")
      (libsource (lib "eagle-import") (part "H807"))
    )
    (comp (ref "C23")
      (value "H807")
      (footprint "eagle-import:H807")
      (libsource (lib "eagle-import") (part "H807"))
    )
    (comp (ref "C24")
      (value "H807")
      (footprint "eagle-import:H807")
      (libsource (lib "eagle-import") (part "H807"))
    )
    (comp (ref "C25")
      (value "H807")
      (footprint "eagle-import:H807")
      (libsource (lib "eagle-import") (part "H807"))
    )
    (comp (ref "C26")
      (value "H807")
      (footprint "eagle-import:H807")
      (libsource (lib "eagle-import") (part "H807"))
    )
    (comp (ref "C27")
      (value "H807")
      (footprint "eagle-import:H807")
      (libsource (lib "eagle-import") (part "H807"))
    )
    (comp (ref "C28")
      (value "H807")
      (footprint "eagle-import:H807")
      (libsource (lib "eagle-import") (part "H807"))
    )
    (comp (ref "D01")
      (value "H807")
      (footprint "eagle-import:H807")
      (libsource (lib "eagle-import") (part "H807"))
    )
    (comp (ref "D02")
      (value "M903")
      (footprint "eagle-import:H807")
      (libsource (lib "eagle-import") (part "M903"))
    )
    (comp (ref "D03")
      (value "M903")
      (footprint "eagle-import:H807")
      (libsource (lib "eagle-import") (part "M903"))
    )
    (comp (ref "D04")
      (value "M903")
      (footprint "eagle-import:H807")
      (libsource (lib "eagle-import") (part "M903"))
    )
    (comp (ref "D05")
      (value "M903")
      (footprint "eagle-import:H807")
      (libsource (lib "eagle-import") (part "M903"))
    )
    (comp (ref "D06")
      (value "M903")
      (footprint "eagle-import:H807")
      (libsource (lib "eagle-import") (part "M903"))
    )
    (comp (ref "D19")
      (value "H807")
      (footprint "eagle-import:H807")
      (libsource (lib "eagle-import") (part "H807"))
    )
    (comp (ref "D20")
      (value "H807")
      (footprint "eagle-import:H807")
      (libsource (lib "eagle-import") (part "H807"))
    )
    (comp (ref "D21")
      (value "H807")
      (footprint "eagle-import:H807")
      (libsource (lib "eagle-import") (part "H807"))
    )
    (comp (ref "D22")
      (value "H807")
      (footprint "eagle-import:H807")
      (libsource (lib "eagle-import") (part "H807"))
    )
    (comp (ref "D23")
      (value "H807")
      (footprint "eagle-import:H807")
      (libsource (lib "eagle-import") (part "H807"))
    )
    (comp (ref "D24")
      (value "H807")
      (footprint "eagle-import:H807")
      (libsource (lib "eagle-import") (part "H807"))
    )
    (comp (ref "D25")
      (value "H807")
      (footprint "eagle-import:H807")
      (libsource (lib "eagle-import") (part "H807"))
    )
    (comp (ref "D26")
      (value "H807")
      (footprint "eagle-import:H807")
      (libsource (lib "eagle-import") (part "H807"))
    )
    (comp (ref "D27")
      (value "H807")
      (footprint "eagle-import:H807")
      (libsource (lib "eagle-import") (part "H807"))
    )
    (comp (ref "D28")
      (value "H807")
      (footprint "eagle-import:H807")
      (libsource (lib "eagle-import") (part "H807"))
    )
    (comp (ref "A11")
      (value "M111")
      (footprint "eagle-import:H807")
      (libsource (lib "eagle-import") (part "M111"))
    )
    (comp (ref "A14")
      (value "M302")
      (footprint "eagle-import:H807")
      (libsource (lib "eagle-import") (part "M302"))
    )
    (comp (ref "A15")
      (value "M627")
      (footprint "eagle-import:H807")
      (libsource (lib "eagle-import") (part "M627"))
    )
    (comp (ref "A16")
      (value "M602")
      (footprint "eagle-import:H807")
      (libsource (lib "eagle-import") (part "M602"))
    )
    (comp (ref "B14")
      (value "M206")
      (footprint "eagle-import:H807")
      (libsource (lib "eagle-import") (part "M206X"))
    )
    (comp (ref "B15")
      (value "M113")
      (footprint "eagle-import:H807")
      (libsource (lib "eagle-import") (part "M113"))
    )
    (comp (ref "B16")
      (value "M602")
      (footprint "eagle-import:H807")
      (libsource (lib "eagle-import") (part "M602"))
    )
    (comp (ref "C12")
      (value "M115")
      (footprint "eagle-import:H807")
      (libsource (lib "eagle-import") (part "M115"))
    )
    (comp (ref "C13")
      (value "M111")
      (footprint "eagle-import:H807")
      (libsource (lib "eagle-import") (part "M111"))
    )
    (comp (ref "C15")
      (value "M113")
      (footprint "eagle-import:H807")
      (libsource (lib "eagle-import") (part "M113"))
    )
    (comp (ref "C16")
      (value "M627")
      (footprint "eagle-import:H807")
      (libsource (lib "eagle-import") (part "M627"))
    )
    (comp (ref "C17")
      (value "M111")
      (footprint "eagle-import:H807")
      (libsource (lib "eagle-import") (part "M111"))
    )
    (comp (ref "D10")
      (value "M119")
      (footprint "eagle-import:H807")
      (libsource (lib "eagle-import") (part "M119"))
    )
    (comp (ref "D14")
      (value "M307")
      (footprint "eagle-import:H807")
      (libsource (lib "eagle-import") (part "M307"))
    )
    (comp (ref "D15")
      (value "M401")
      (footprint "eagle-import:H807")
      (libsource (lib "eagle-import") (part "M401"))
    )
    (comp (ref "A07")
      (value "M161")
      (footprint "eagle-import:H807")
      (libsource (lib "eagle-import") (part "M161"))
    )
    (comp (ref "A09")
      (value "M117")
      (footprint "eagle-import:H807")
      (libsource (lib "eagle-import") (part "M117"))
    )
    (comp (ref "A10")
      (value "M113")
      (footprint "eagle-import:H807")
      (libsource (lib "eagle-import") (part "M113"))
    )
    (comp (ref "A22")
      (value "M502")
      (footprint "eagle-import:H807")
      (libsource (lib "eagle-import") (part "M502"))
    )
    (comp (ref "A23")
      (value "M633")
      (footprint "eagle-import:H807")
      (libsource (lib "eagle-import") (part "M633"))
    )
    (comp (ref "B07")
      (value "M207")
      (footprint "eagle-import:H807")
      (libsource (lib "eagle-import") (part "M207"))
    )
    (comp (ref "B11")
      (value "M115")
      (footprint "eagle-import:H807")
      (libsource (lib "eagle-import") (part "M115"))
    )
    (comp (ref "B22")
      (value "M633")
      (footprint "eagle-import:H807")
      (libsource (lib "eagle-import") (part "M633"))
    )
    (comp (ref "B23")
      (value "W005")
      (footprint "eagle-import:H807")
      (libsource (lib "eagle-import") (part "W005"))
    )
    (comp (ref "C07")
      (value "M207")
      (footprint "eagle-import:H807")
      (libsource (lib "eagle-import") (part "M207"))
    )
    (comp (ref "D07")
      (value "M161")
      (footprint "eagle-import:H807")
      (libsource (lib "eagle-import") (part "M161"))
    )
    (comp (ref "D09")
      (value "M121")
      (footprint "eagle-import:H807")
      (libsource (lib "eagle-import") (part "M121"))
    )
    (comp (ref "B02")
      (value "M623")
      (footprint "eagle-import:H807")
      (libsource (lib "eagle-import") (part "M623"))
    )
    (comp (ref "B03")
      (value "M623")
      (footprint "eagle-import:H807")
      (libsource (lib "eagle-import") (part "M623"))
    )
    (comp (ref "B04")
      (value "M623")
      (footprint "eagle-import:H807")
      (libsource (lib "eagle-import") (part "M623"))
    )
    (comp (ref "B05")
      (value "M623")
      (footprint "eagle-import:H807")
      (libsource (lib "eagle-import") (part "M623"))
    )
    (comp (ref "C02")
      (value "M101")
      (footprint "eagle-import:H807")
      (libsource (lib "eagle-import") (part "M101-ARRAY"))
    )
    (comp (ref "C03")
      (value "M101")
      (footprint "eagle-import:H807")
      (libsource (lib "eagle-import") (part "M101-ARRAY"))
    )
    (comp (ref "A12")
      (value "M113")
      (footprint "eagle-import:H807")
      (libsource (lib "eagle-import") (part "M113"))
    )
    (comp (ref "B06")
      (value "M111")
      (footprint "eagle-import:H807")
      (libsource (lib "eagle-import") (part "M111"))
    )
    (comp (ref "B10")
      (value "M627")
      (footprint "eagle-import:H807")
      (libsource (lib "eagle-import") (part "M627"))
    )
    (comp (ref "C01")
      (value "M101")
      (footprint "eagle-import:H807")
      (libsource (lib "eagle-import") (part "M101"))
    )
    (comp (ref "C04")
      (value "M103")
      (footprint "eagle-import:H807")
      (libsource (lib "eagle-import") (part "M103"))
    )
    (comp (ref "C05")
      (value "M103")
      (footprint "eagle-import:H807")
      (libsource (lib "eagle-import") (part "M103"))
    )
    (comp (ref "C06")
      (value "M111")
      (footprint "eagle-import:H807")
      (libsource (lib "eagle-import") (part "M111"))
    )
    (comp (ref "D11")
      (value "M206")
      (footprint "eagle-import:H807")
      (libsource (lib "eagle-import") (part "M206X"))
    )
    (comp (ref "D12")
      (value "M627")
      (footprint "eagle-import:H807")
      (libsource (lib "eagle-import") (part "M627"))
    )
    (comp (ref "D13")
      (value "M602")
      (footprint "eagle-import:H807")
      (libsource (lib "eagle-import") (part "M602"))
    )
    (comp (ref "D17")
      (value "M602")
      (footprint "eagle-import:H807")
      (libsource (lib "eagle-import") (part "M602"))
    )
    (comp (ref "B12")
      (value "M117")
      (footprint "eagle-import:H807")
      (libsource (lib "eagle-import") (part "M117"))
    )
    (comp (ref "C11")
      (value "M113")
      (footprint "eagle-import:H807")
      (libsource (lib "eagle-import") (part "M113"))
    )
    (comp (ref "D08")
      (value "M207")
      (footprint "eagle-import:H807")
      (libsource (lib "eagle-import") (part "M207"))
    )
    (comp (ref "CD18")
      (value "M228")
      (footprint "eagle-import:H807-2")
      (libsource (lib "eagle-import") (part "M228"))
    )
    (comp (ref "A08")
      (value "M206")
      (footprint "eagle-import:H807")
      (libsource (lib "eagle-import") (part "M206X"))
    )
    (comp (ref "B13")
      (value "M206")
      (footprint "eagle-import:H807")
      (libsource (lib "eagle-import") (part "M206X"))
    )
    (comp (ref "B21")
      (value "G879")
      (footprint "eagle-import:H807")
      (libsource (lib "eagle-import") (part "G879"))
    )
    (comp (ref "D16")
      (value "M302")
      (footprint "eagle-import:H807")
      (libsource (lib "eagle-import") (part "M302"))
    )
    (comp (ref "A18")
      (value "G888")
      (footprint "eagle-import:H807")
      (libsource (lib "eagle-import") (part "G888"))
    )
    (comp (ref "A20")
      (value "G888")
      (footprint "eagle-import:H807")
      (libsource (lib "eagle-import") (part "G888"))
    )
    (comp (ref "A21")
      (value "G888")
      (footprint "eagle-import:H807")
      (libsource (lib "eagle-import") (part "G888"))
    )
    (comp (ref "AB01")
      (value "G821")
      (footprint "eagle-import:H807-2")
      (libsource (lib "eagle-import") (part "G821"))
    )
    (comp (ref "AB19")
      (value "W032")
      (footprint "eagle-import:H807-2")
      (libsource (lib "eagle-import") (part "W032"))
    )
    (comp (ref "B18")
      (value "G888")
      (footprint "eagle-import:H807")
      (libsource (lib "eagle-import") (part "G888"))
    )
    (comp (ref "B20")
      (value "G888")
      (footprint "eagle-import:H807")
      (libsource (lib "eagle-import") (part "G888"))
    )
  )
  (nets
    (net (code "1") (name "+3V@A09U1") (class "Default")
      (node (ref "A07") (pin "S1") (pinfunction "EN2_S1") (pintype "input"))
      (node (ref "A07") (pin "S2") (pinfunction "EN1_S2") (pintype "input"))
      (node (ref "A07") (pin "T2") (pinfunction "EN3_T2") (pintype "input"))
      (node (ref "A08") (pin "D1") (pinfunction "S_D1") (pintype "input"))
      (node (ref "A08") (pin "F2") (pinfunction "S_F2") (pintype "input"))
      (node (ref "A08") (pin "K2") (pinfunction "R_K2") (pintype "input"))
      (node (ref "A09") (pin "U1") (pinfunction "P$1_U1") (pintype "passive"))
      (node (ref "B13") (pin "R1") (pinfunction "S_R1") (pintype "input"))
      (node (ref "B13") (pin "U2") (pinfunction "S_U2") (pintype "input"))
    )
    (net (code "2") (name "+3V@B12U1") (class "Default")
      (node (ref "B12") (pin "U1") (pinfunction "P$1_U1") (pintype "passive"))
      (node (ref "B13") (pin "D1") (pinfunction "S_D1") (pintype "input"))
      (node (ref "B13") (pin "F2") (pinfunction "S_F2") (pintype "input"))
      (node (ref "B13") (pin "K1") (pinfunction "S_K1") (pintype "input"))
      (node (ref "B14") (pin "A1") (pinfunction "R_A1") (pintype "input"))
      (node (ref "B14") (pin "K2") (pinfunction "R_K2") (pintype "input"))
      (node (ref "B14") (pin "N2") (pinfunction "S_N2") (pintype "input"))
      (node (ref "B14") (pin "R1") (pinfunction "S_R1") (pintype "input"))
      (node (ref "B14") (pin "U2") (pinfunction "S_U2") (pintype "input"))
    )
    (net (code "3") (name "+3V@C08U1") (class "Default")
      (node (ref "C01") (pin "C1") (pinfunction "IN2_C1") (pintype "input"))
      (node (ref "C02") (pin "C1") (pinfunction "ENABLE_C1") (pintype "input"))
      (node (ref "C04") (pin "J1") (pinfunction "IN2_J1") (pintype "input"))
      (node (ref "C04") (pin "L2") (pinfunction "L2_L2") (pintype "input"))
      (node (ref "C04") (pin "N2") (pinfunction "N2_N2") (pintype "input"))
      (node (ref "C04") (pin "U2") (pinfunction "U2_U2") (pintype "input"))
      (node (ref "C05") (pin "J1") (pinfunction "IN2_J1") (pintype "input"))
      (node (ref "C05") (pin "L2") (pinfunction "L2_L2") (pintype "input"))
      (node (ref "C05") (pin "N2") (pinfunction "N2_N2") (pintype "input"))
      (node (ref "C05") (pin "U2") (pinfunction "U2_U2") (pintype "input"))
      (node (ref "C08") (pin "U1") (pinfunction "P$1_U1") (pintype "passive"))
    )
    (net (code "4") (name "+3V@C15U1") (class "Default")
      (node (ref "C14") (pin "A1") (pinfunction "R_A1") (pintype "input"))
      (node (ref "C14") (pin "D1") (pinfunction "S_D1") (pintype "input"))
      (node (ref "C14") (pin "F2") (pinfunction "S_F2") (pintype "input"))
      (node (ref "C14") (pin "K1") (pinfunction "S_K1") (pintype "input"))
      (node (ref "C14") (pin "K2") (pinfunction "R_K2") (pintype "input"))
      (node (ref "C15") (pin "U1") (pinfunction "P$1_U1") (pintype "passive"))
      (node (ref "C16") (pin "H2") (pinfunction "IN4_H2") (pintype "input"))
    )
    (net (code "5") (name "+3V@D09U1") (class "Default")
      (node (ref "D07") (pin "S1") (pinfunction "EN2_S1") (pintype "input"))
      (node (ref "D07") (pin "S2") (pinfunction "EN1_S2") (pintype "input"))
      (node (ref "D07") (pin "T2") (pinfunction "EN3_T2") (pintype "input"))
      (node (ref "D09") (pin "U1") (pinfunction "P$1_U1") (pintype "passive"))
    )
    (net (code "6") (name "+3V@D10U1") (class "Default")
      (node (ref "D10") (pin "L2") (pinfunction "IN6_L2") (pintype "input"))
      (node (ref "D10") (pin "M2") (pinfunction "IN7_M2") (pintype "input"))
      (node (ref "D10") (pin "N2") (pinfunction "IN8_N2") (pintype "input"))
      (node (ref "D10") (pin "U1") (pinfunction "P$1_U1") (pintype "passive"))
      (node (ref "D11") (pin "D1") (pinfunction "S_D1") (pintype "input"))
      (node (ref "D11") (pin "F2") (pinfunction "S_F2") (pintype "input"))
      (node (ref "D11") (pin "K1") (pinfunction "S_K1") (pintype "input"))
      (node (ref "D11") (pin "K2") (pinfunction "R_K2") (pintype "input"))
      (node (ref "D14") (pin "M1") (pinfunction "M1_M1") (pintype "input"))
    )
    (net (code "7") (name "+11V") (class "Default")
      (node (ref "AB01") (pin "BM2") (pinfunction "+11V_BM2") (pintype "power_in"))
    )
    (net (code "8") (name "-15V") (class "Default")
      (node (ref "AB01") (pin "AB2") (pinfunction "-15V_AB2") (pintype "power_in"))
      (node (ref "AB01") (pin "AE2") (pinfunction "-15V_AE2") (pintype "power_in"))
      (node (ref "AB01") (pin "AF2") (pinfunction "-15V_AF2") (pintype "power_in"))
    )
    (net (code "9") (name "00") (class "Default")
      (node (ref "A07") (pin "D2") (pinfunction "O0_D2") (pintype "output"))
    )
    (net (code "10") (name "0_TO_DTB") (class "Default")
      (node (ref "A11") (pin "M1") (pinfunction "OUT_M1") (pintype "output"))
      (node (ref "C11") (pin "R1") (pinfunction "IN2_R1") (pintype "input"))
    )
    (net (code "11") (name "0_TO_EF") (class "Default")
      (node (ref "A10") (pin "K2") (pinfunction "OUT_K2") (pintype "output"))
      (node (ref "A11") (pin "E2") (pinfunction "IN_E2") (pintype "input"))
    )
    (net (code "12") (name "0_TO_STA") (class "Default")
      (node (ref "A10") (pin "N2") (pinfunction "OUT_N2") (pintype "output"))
      (node (ref "A11") (pin "N1") (pinfunction "IN_N1") (pintype "input"))
    )
    (net (code "13") (name "01") (class "Default")
      (node (ref "A07") (pin "E2") (pinfunction "O1_E2") (pintype "output"))
    )
    (net (code "14") (name "1_TO_DF") (class "Default")
      (node (ref "A08") (pin "H1") (pinfunction "C_H1") (pintype "input"))
      (node (ref "C12") (pin "J1") (pinfunction "OUT_J1") (pintype "output"))
      (node (ref "C12") (pin "L1") (pinfunction "IN2_L1") (pintype "input"))
      (node (ref "D11") (pin "L2") (pinfunction "C_L2") (pintype "input"))
    )
    (net (code "15") (name "1_TO_DTF") (class "Default")
      (node (ref "B12") (pin "P2") (pinfunction "OUT_P2") (pintype "output"))
      (node (ref "D11") (pin "S2") (pinfunction "C_S2") (pintype "input"))
    )
    (net (code "16") (name "02") (class "Default")
      (node (ref "A07") (pin "J2") (pinfunction "O2_J2") (pintype "output"))
    )
    (net (code "17") (name "03") (class "Default")
      (node (ref "A07") (pin "N2") (pinfunction "O3_N2") (pintype "output"))
    )
    (net (code "18") (name "04") (class "Default")
      (node (ref "A07") (pin "F2") (pinfunction "O4_F2") (pintype "output"))
    )
    (net (code "19") (name "05") (class "Default")
      (node (ref "A07") (pin "M2") (pinfunction "O5_M2") (pintype "output"))
    )
    (net (code "20") (name "06") (class "Default")
      (node (ref "A07") (pin "H2") (pinfunction "O6_H2") (pintype "output"))
    )
    (net (code "21") (name "07") (class "Default")
      (node (ref "A07") (pin "L2") (pinfunction "O7_L2") (pintype "output"))
    )
    (net (code "22") (name "76") (class "Default")
      (node (ref "C04") (pin "V2") (pinfunction "V2_V2") (pintype "output"))
      (node (ref "C06") (pin "S2") (pinfunction "IN_S2") (pintype "input"))
    )
    (net (code "23") (name "76+77") (class "Default")
      (node (ref "C03") (pin "C1") (pinfunction "ENABLE_C1") (pintype "input"))
      (node (ref "D12") (pin "V2") (pinfunction "OUT_V2") (pintype "output"))
    )
    (net (code "24") (name "77") (class "Default")
      (node (ref "C05") (pin "V2") (pinfunction "V2_V2") (pintype "output"))
      (node (ref "C06") (pin "U2") (pinfunction "IN_U2") (pintype "input"))
    )
    (net (code "25") (name "ADDR_ACC") (class "Default")
      (node (ref "C02") (pin "V2") (pinfunction "O15_V2") (pintype "output"))
      (node (ref "C17") (pin "N1") (pinfunction "IN_N1") (pintype "input"))
    )
    (net (code "26") (name "B-BRK") (class "Default")
      (node (ref "B10") (pin "R2") (pinfunction "IN1_R2") (pintype "input"))
      (node (ref "B10") (pin "S2") (pinfunction "IN2_S2") (pintype "input"))
      (node (ref "B10") (pin "T2") (pinfunction "IN3_T2") (pintype "input"))
      (node (ref "B10") (pin "U2") (pinfunction "IN4_U2") (pintype "input"))
      (node (ref "C01") (pin "E1") (pinfunction "OUT_E1") (pintype "output"))
      (node (ref "D12") (pin "M1") (pinfunction "IN1_M1") (pintype "input"))
    )
    (net (code "27") (name "B-RUN") (class "Default")
      (node (ref "B11") (pin "N2") (pinfunction "IN1_N2") (pintype "input"))
      (node (ref "C01") (pin "B1") (pinfunction "OUT_B1") (pintype "output"))
    )
    (net (code "28") (name "B-XSTA") (class "Default")
      (node (ref "A10") (pin "E2") (pinfunction "IN2_E2") (pintype "input"))
      (node (ref "C11") (pin "P2") (pinfunction "IN1_P2") (pintype "input"))
      (node (ref "D12") (pin "E1") (pinfunction "OUT_E1") (pintype "output"))
    )
    (net (code "29") (name "BAC_00") (class "Default")
      (node (ref "B06") (pin "B1") (pinfunction "OUT_B1") (pintype "output"))
      (node (ref "B07") (pin "C1") (pinfunction "C1_C1") (pintype "input"))
      (node (ref "B07") (pin "D1") (pinfunction "D1_D1") (pintype "input"))
    )
    (net (code "30") (name "BAC_01") (class "Default")
      (node (ref "B06") (pin "E1") (pinfunction "OUT_E1") (pintype "output"))
      (node (ref "B07") (pin "E2") (pinfunction "E2_E2") (pintype "input"))
      (node (ref "B07") (pin "F2") (pinfunction "F2_F2") (pintype "input"))
    )
    (net (code "31") (name "BAC_02") (class "Default")
      (node (ref "B06") (pin "H1") (pinfunction "OUT_H1") (pintype "output"))
      (node (ref "B07") (pin "J1") (pinfunction "J1_J1") (pintype "input"))
      (node (ref "B07") (pin "K1") (pinfunction "K1_K1") (pintype "input"))
    )
    (net (code "32") (name "BAC_03") (class "Default")
      (node (ref "B06") (pin "K1") (pinfunction "OUT_K1") (pintype "output"))
      (node (ref "B07") (pin "M2") (pinfunction "M2_M2") (pintype "input"))
      (node (ref "B07") (pin "N2") (pinfunction "N2_N2") (pintype "input"))
    )
    (net (code "33") (name "BAC_04") (class "Default")
      (node (ref "B06") (pin "M1") (pinfunction "OUT_M1") (pintype "output"))
      (node (ref "C07") (pin "M2") (pinfunction "M2_M2") (pintype "input"))
      (node (ref "C07") (pin "N2") (pinfunction "N2_N2") (pintype "input"))
    )
    (net (code "34") (name "BAC_05") (class "Default")
      (node (ref "B06") (pin "P1") (pinfunction "OUT_P1") (pintype "output"))
      (node (ref "B07") (pin "P1") (pinfunction "P1_P1") (pintype "input"))
      (node (ref "B07") (pin "R1") (pinfunction "R1_R1") (pintype "input"))
    )
    (net (code "35") (name "BAC_06") (class "Default")
      (node (ref "B06") (pin "S1") (pinfunction "OUT_S1") (pintype "output"))
      (node (ref "B07") (pin "T2") (pinfunction "T2_T2") (pintype "input"))
      (node (ref "B07") (pin "U2") (pinfunction "U2_U2") (pintype "input"))
      (node (ref "D11") (pin "C1") (pinfunction "D_C1") (pintype "input"))
    )
    (net (code "36") (name "BAC_07") (class "Default")
      (node (ref "B06") (pin "U1") (pinfunction "OUT_U1") (pintype "output"))
      (node (ref "C07") (pin "C1") (pinfunction "C1_C1") (pintype "input"))
      (node (ref "C07") (pin "D1") (pinfunction "D1_D1") (pintype "input"))
      (node (ref "D11") (pin "E2") (pinfunction "D_E2") (pintype "input"))
    )
    (net (code "37") (name "BAC_08") (class "Default")
      (node (ref "B06") (pin "D2") (pinfunction "OUT_D2") (pintype "output"))
      (node (ref "C07") (pin "E2") (pinfunction "E2_E2") (pintype "input"))
      (node (ref "C07") (pin "F2") (pinfunction "F2_F2") (pintype "input"))
      (node (ref "D11") (pin "J1") (pinfunction "D_J1") (pintype "input"))
    )
    (net (code "38") (name "BAC_09") (class "Default")
      (node (ref "B06") (pin "F2") (pinfunction "OUT_F2") (pintype "output"))
      (node (ref "C07") (pin "J1") (pinfunction "J1_J1") (pintype "input"))
      (node (ref "C07") (pin "K1") (pinfunction "K1_K1") (pintype "input"))
    )
    (net (code "39") (name "BAC_10") (class "Default")
      (node (ref "B06") (pin "J2") (pinfunction "OUT_J2") (pintype "output"))
    )
    (net (code "40") (name "BAC_11") (class "Default")
      (node (ref "B06") (pin "L2") (pinfunction "OUT_L2") (pintype "output"))
    )
    (net (code "41") (name "BLK_IN_SYNC") (class "Default")
      (node (ref "C11") (pin "E2") (pinfunction "IN2_E2") (pintype "input"))
      (node (ref "C13") (pin "S1") (pinfunction "OUT_S1") (pintype "output"))
      (node (ref "CD18") (pin "AP2") (pinfunction "AP2_AP2") (pintype "input"))
    )
    (net (code "42") (name "BMB_00") (class "Default")
      (node (ref "C06") (pin "B1") (pinfunction "OUT_B1") (pintype "output"))
      (node (ref "C08") (pin "B1") (pinfunction "IN1B_B1") (pintype "input"))
    )
    (net (code "43") (name "BMB_01") (class "Default")
      (node (ref "C06") (pin "E1") (pinfunction "OUT_E1") (pintype "output"))
      (node (ref "C08") (pin "H1") (pinfunction "IN1B_H1") (pintype "input"))
    )
    (net (code "44") (name "BMB_02") (class "Default")
      (node (ref "C06") (pin "H1") (pinfunction "OUT_H1") (pintype "output"))
      (node (ref "C08") (pin "N1") (pinfunction "IN1B_N1") (pintype "input"))
    )
    (net (code "45") (name "BMB_03") (class "Default")
      (node (ref "C06") (pin "K1") (pinfunction "OUT_K1") (pintype "output"))
      (node (ref "C08") (pin "E2") (pinfunction "IN1B_E2") (pintype "input"))
    )
    (net (code "46") (name "BMB_04") (class "Default")
      (node (ref "C06") (pin "M1") (pinfunction "OUT_M1") (pintype "output"))
      (node (ref "C08") (pin "L2") (pinfunction "IN1B_L2") (pintype "input"))
    )
    (net (code "47") (name "BMB_05") (class "Default")
      (node (ref "C06") (pin "P1") (pinfunction "OUT_P1") (pintype "output"))
      (node (ref "C08") (pin "S2") (pinfunction "IN1B_S2") (pintype "input"))
    )
    (net (code "48") (name "BMB_06") (class "Default")
      (node (ref "B08") (pin "B1") (pinfunction "IN2_B1") (pintype "input"))
      (node (ref "C06") (pin "S1") (pinfunction "OUT_S1") (pintype "output"))
    )
    (net (code "49") (name "BMB_07") (class "Default")
      (node (ref "B08") (pin "E1") (pinfunction "IN2_E1") (pintype "input"))
      (node (ref "C06") (pin "U1") (pinfunction "OUT_U1") (pintype "output"))
    )
    (net (code "50") (name "BMB_08") (class "Default")
      (node (ref "B08") (pin "E2") (pinfunction "IN2_E2") (pintype "input"))
      (node (ref "C06") (pin "D2") (pinfunction "OUT_D2") (pintype "output"))
    )
    (net (code "51") (name "BMB_09") (class "Default")
      (node (ref "B08") (pin "M1") (pinfunction "IN2_M1") (pintype "input"))
      (node (ref "C06") (pin "F2") (pinfunction "OUT_F2") (pintype "output"))
    )
    (net (code "52") (name "BMB_10") (class "Default")
      (node (ref "B08") (pin "R1") (pinfunction "IN2_R1") (pintype "input"))
      (node (ref "C06") (pin "J2") (pinfunction "OUT_J2") (pintype "output"))
    )
    (net (code "53") (name "BMB_11") (class "Default")
      (node (ref "B08") (pin "J1") (pinfunction "IN2_J1") (pintype "input"))
      (node (ref "C06") (pin "L2") (pinfunction "OUT_L2") (pintype "output"))
    )
    (net (code "54") (name "BMB_TO_DTB") (class "Default")
      (node (ref "B08") (pin "A1") (pinfunction "IN1_A1") (pintype "input"))
      (node (ref "B08") (pin "D1") (pinfunction "IN1_D1") (pintype "input"))
      (node (ref "B08") (pin "D2") (pinfunction "IN1_D2") (pintype "input"))
      (node (ref "B08") (pin "H1") (pinfunction "IN1_H1") (pintype "input"))
      (node (ref "B08") (pin "L1") (pinfunction "IN1_L1") (pintype "input"))
      (node (ref "B08") (pin "P1") (pinfunction "IN1_P1") (pintype "input"))
      (node (ref "C08") (pin "A1") (pinfunction "IN1A_A1") (pintype "input"))
      (node (ref "C08") (pin "D2") (pinfunction "IN1A_D2") (pintype "input"))
      (node (ref "C08") (pin "F1") (pinfunction "IN1A_F1") (pintype "input"))
      (node (ref "C08") (pin "K2") (pinfunction "IN1A_K2") (pintype "input"))
      (node (ref "C08") (pin "M1") (pinfunction "IN1A_M1") (pintype "input"))
      (node (ref "C08") (pin "R2") (pinfunction "IN1A_R2") (pintype "input"))
      (node (ref "D12") (pin "L1") (pinfunction "OUT_L1") (pintype "output"))
    )
    (net (code "55") (name "BMR00") (class "Default")
      (node (ref "A23") (pin "F1") (pinfunction "A_F1") (pintype "input"))
      (node (ref "B14") (pin "P2") (pinfunction "1_P2") (pintype "output"))
    )
    (net (code "56") (name "BMR01") (class "Default")
      (node (ref "A23") (pin "B1") (pinfunction "B_B1") (pintype "input"))
      (node (ref "B14") (pin "F1") (pinfunction "0_F1") (pintype "output"))
    )
    (net (code "57") (name "C00") (class "Default")
      (node (ref "A12") (pin "L2") (pinfunction "IN1_L2") (pintype "input"))
      (node (ref "A26") (pin "E2") (pinfunction "P$2_E2") (pintype "bidirectional"))
      (node (ref "B12") (pin "R2") (pinfunction "IN1_R2") (pintype "input"))
      (node (ref "B13") (pin "S1") (pinfunction "1_S1") (pintype "output"))
      (node (ref "C15") (pin "E2") (pinfunction "IN2_E2") (pintype "input"))
      (node (ref "D10") (pin "C1") (pinfunction "IN3_C1") (pintype "input"))
    )
    (net (code "58") (name "C01") (class "Default")
      (node (ref "A12") (pin "M2") (pinfunction "IN2_M2") (pintype "input"))
      (node (ref "A26") (pin "F2") (pinfunction "P$2_F2") (pintype "bidirectional"))
      (node (ref "B10") (pin "J1") (pinfunction "IN3_J1") (pintype "input"))
      (node (ref "B11") (pin "V2") (pinfunction "IN3_V2") (pintype "input"))
      (node (ref "B13") (pin "P2") (pinfunction "1_P2") (pintype "output"))
    )
    (net (code "59") (name "CK00") (class "Default")
      (node (ref "A18") (pin "P2") (pinfunction "P2_P2") (pintype "input"))
      (node (ref "B14") (pin "S1") (pinfunction "1_S1") (pintype "output"))
    )
    (net (code "60") (name "CK01") (class "Default")
      (node (ref "B14") (pin "P1") (pinfunction "D_P1") (pintype "input"))
      (node (ref "B14") (pin "V2") (pinfunction "1_V2") (pintype "output"))
      (node (ref "C16") (pin "N1") (pinfunction "IN2_N1") (pintype "input"))
      (node (ref "C16") (pin "P1") (pinfunction "IN3_P1") (pintype "input"))
      (node (ref "C16") (pin "R1") (pinfunction "IN4_R1") (pintype "input"))
    )
    (net (code "61") (name "COMP+SH") (class "Default")
      (node (ref "A12") (pin "D2") (pinfunction "IN1_D2") (pintype "input"))
      (node (ref "C14") (pin "B1") (pinfunction "C_B1") (pintype "input"))
      (node (ref "C14") (pin "D2") (pinfunction "C_D2") (pintype "input"))
      (node (ref "C14") (pin "H1") (pinfunction "C_H1") (pintype "input"))
      (node (ref "C15") (pin "K1") (pinfunction "OUT_K1") (pintype "output"))
    )
    (net (code "62") (name "CSTA") (class "Default")
      (node (ref "C04") (pin "C1") (pinfunction "C1_C1") (pintype "output"))
      (node (ref "D16") (pin "P2") (pinfunction "K2_P2") (pintype "input"))
    )
    (net (code "63") (name "DATA") (class "Default")
      (node (ref "A26") (pin "M1") (pinfunction "P$2_M1") (pintype "bidirectional"))
      (node (ref "C13") (pin "F1") (pinfunction "IN_F1") (pintype "input"))
      (node (ref "CD18") (pin "BK2") (pinfunction "BK2_BK2") (pintype "output"))
    )
    (net (code "64") (name "DF") (class "Default")
      (node (ref "A10") (pin "P2") (pinfunction "IN1_P2") (pintype "input"))
      (node (ref "A26") (pin "E1") (pinfunction "P$2_E1") (pintype "bidirectional"))
      (node (ref "D11") (pin "R2") (pinfunction "0_R2") (pintype "output"))
    )
    (net (code "65") (name "DTB_00") (class "Default")
      (node (ref "A25") (pin "A2") (pinfunction "P$2_A2") (pintype "bidirectional"))
      (node (ref "C09") (pin "E1") (pinfunction "1_E1") (pintype "output"))
      (node (ref "C10") (pin "B1") (pinfunction "IN1B_B1") (pintype "input"))
      (node (ref "D09") (pin "D2") (pinfunction "IN1A_D2") (pintype "input"))
    )
    (net (code "66") (name "DTB_01") (class "Default")
      (node (ref "A25") (pin "B2") (pinfunction "P$2_B2") (pintype "bidirectional"))
      (node (ref "C09") (pin "H2") (pinfunction "1_H2") (pintype "output"))
      (node (ref "C10") (pin "H1") (pinfunction "IN1B_H1") (pintype "input"))
      (node (ref "D09") (pin "K2") (pinfunction "IN1A_K2") (pintype "input"))
    )
    (net (code "67") (name "DTB_02") (class "Default")
      (node (ref "A25") (pin "C2") (pinfunction "P$2_C2") (pintype "bidirectional"))
      (node (ref "C09") (pin "L1") (pinfunction "1_L1") (pintype "output"))
      (node (ref "C10") (pin "N1") (pinfunction "IN1B_N1") (pintype "input"))
      (node (ref "D09") (pin "R2") (pinfunction "IN1A_R2") (pintype "input"))
    )
    (net (code "68") (name "DTB_03") (class "Default")
      (node (ref "A25") (pin "D2") (pinfunction "P$2_D2") (pintype "bidirectional"))
      (node (ref "C09") (pin "C1") (pinfunction "D_C1") (pintype "input"))
      (node (ref "C09") (pin "P2") (pinfunction "1_P2") (pintype "output"))
    )
    (net (code "69") (name "DTB_04") (class "Default")
      (node (ref "A25") (pin "E2") (pinfunction "P$2_E2") (pintype "bidirectional"))
      (node (ref "C09") (pin "E2") (pinfunction "D_E2") (pintype "input"))
      (node (ref "C09") (pin "S1") (pinfunction "1_S1") (pintype "output"))
    )
    (net (code "70") (name "DTB_05") (class "Default")
      (node (ref "A25") (pin "F2") (pinfunction "P$2_F2") (pintype "bidirectional"))
      (node (ref "C09") (pin "J1") (pinfunction "D_J1") (pintype "input"))
      (node (ref "C09") (pin "V2") (pinfunction "1_V2") (pintype "output"))
    )
    (net (code "71") (name "DTB_06") (class "Default")
      (node (ref "A25") (pin "H2") (pinfunction "P$2_H2") (pintype "bidirectional"))
      (node (ref "B09") (pin "E1") (pinfunction "1_E1") (pintype "output"))
      (node (ref "C09") (pin "M2") (pinfunction "D_M2") (pintype "input"))
    )
    (net (code "72") (name "DTB_07") (class "Default")
      (node (ref "A25") (pin "J2") (pinfunction "P$2_J2") (pintype "bidirectional"))
      (node (ref "B09") (pin "V2") (pinfunction "1_V2") (pintype "output"))
      (node (ref "C09") (pin "P1") (pinfunction "D_P1") (pintype "input"))
    )
    (net (code "73") (name "DTB_08") (class "Default")
      (node (ref "A25") (pin "K2") (pinfunction "P$2_K2") (pintype "bidirectional"))
      (node (ref "B09") (pin "L1") (pinfunction "1_L1") (pintype "output"))
      (node (ref "C09") (pin "T2") (pinfunction "D_T2") (pintype "input"))
    )
    (net (code "74") (name "DTB_09") (class "Default")
      (node (ref "A25") (pin "L2") (pinfunction "P$2_L2") (pintype "bidirectional"))
      (node (ref "B09") (pin "C1") (pinfunction "D_C1") (pintype "input"))
      (node (ref "B09") (pin "P2") (pinfunction "1_P2") (pintype "output"))
    )
    (net (code "75") (name "DTB_10") (class "Default")
      (node (ref "A25") (pin "M2") (pinfunction "P$2_M2") (pintype "bidirectional"))
      (node (ref "B09") (pin "S1") (pinfunction "1_S1") (pintype "output"))
      (node (ref "B09") (pin "T2") (pinfunction "D_T2") (pintype "input"))
    )
    (net (code "76") (name "DTB_11") (class "Default")
      (node (ref "A25") (pin "N2") (pinfunction "P$2_N2") (pintype "bidirectional"))
      (node (ref "B09") (pin "H2") (pinfunction "1_H2") (pintype "output"))
      (node (ref "B09") (pin "J1") (pinfunction "D_J1") (pintype "input"))
    )
    (net (code "77") (name "DTF") (class "Default")
      (node (ref "A08") (pin "J1") (pinfunction "D_J1") (pintype "input"))
      (node (ref "A12") (pin "M1") (pinfunction "IN2_M1") (pintype "input"))
      (node (ref "A26") (pin "C1") (pinfunction "P$2_C1") (pintype "bidirectional"))
      (node (ref "D11") (pin "V1") (pinfunction "0_V1") (pintype "output"))
    )
    (net (code "78") (name "DTSF") (class "Default")
      (node (ref "A12") (pin "R1") (pinfunction "IN2_R1") (pintype "input"))
      (node (ref "C05") (pin "A1") (pinfunction "A1_A1") (pintype "output"))
    )
    (net (code "79") (name "EF") (class "Default")
      (node (ref "A11") (pin "J1") (pinfunction "IN_J1") (pintype "input"))
      (node (ref "A12") (pin "F1") (pinfunction "OUT_F1") (pintype "output"))
      (node (ref "A12") (pin "L1") (pinfunction "IN1_L1") (pintype "input"))
      (node (ref "A25") (pin "N1") (pinfunction "P$2_N1") (pintype "bidirectional"))
    )
    (net (code "80") (name "END") (class "Default")
      (node (ref "A08") (pin "E1") (pinfunction "1_E1") (pintype "output"))
      (node (ref "A25") (pin "R1") (pinfunction "P$2_R1") (pintype "bidirectional"))
    )
    (net (code "81") (name "ENI") (class "Default")
      (node (ref "A12") (pin "H1") (pinfunction "IN1_H1") (pintype "input"))
      (node (ref "A25") (pin "L1") (pinfunction "P$2_L1") (pintype "bidirectional"))
      (node (ref "C07") (pin "L1") (pinfunction "L1_L1") (pintype "output"))
    )
    (net (code "82") (name "FR_00") (class "Default")
      (node (ref "A25") (pin "F1") (pinfunction "P$2_F1") (pintype "bidirectional"))
      (node (ref "B07") (pin "S1") (pinfunction "S1_S1") (pintype "output"))
      (node (ref "B12") (pin "E2") (pinfunction "IN2_E2") (pintype "input"))
      (node (ref "C12") (pin "U2") (pinfunction "IN2_U2") (pintype "input"))
    )
    (net (code "83") (name "FR_01") (class "Default")
      (node (ref "A10") (pin "H1") (pinfunction "IN1_H1") (pintype "input"))
      (node (ref "A25") (pin "H1") (pinfunction "P$2_H1") (pintype "bidirectional"))
      (node (ref "B07") (pin "V2") (pinfunction "V2_V2") (pintype "output"))
      (node (ref "B15") (pin "M1") (pinfunction "IN2_M1") (pintype "input"))
      (node (ref "C15") (pin "D1") (pinfunction "IN1_D1") (pintype "input"))
      (node (ref "D07") (pin "V2") (pinfunction "IN2_V2") (pintype "input"))
      (node (ref "D12") (pin "R1") (pinfunction "IN4_R1") (pintype "input"))
    )
    (net (code "84") (name "FR_02") (class "Default")
      (node (ref "A25") (pin "J1") (pinfunction "P$2_J1") (pintype "bidirectional"))
      (node (ref "C07") (pin "E1") (pinfunction "E1_E1") (pintype "output"))
      (node (ref "D07") (pin "U2") (pinfunction "IN1_U2") (pintype "input"))
    )
    (net (code "85") (name "FR_03") (class "Default")
      (node (ref "A25") (pin "K1") (pinfunction "P$2_K1") (pintype "bidirectional"))
      (node (ref "B15") (pin "R2") (pinfunction "IN2_R2") (pintype "input"))
      (node (ref "C07") (pin "H2") (pinfunction "H2_H2") (pintype "output"))
      (node (ref "D07") (pin "V1") (pinfunction "IN0_V1") (pintype "input"))
    )
    (net (code "86") (name "GND") (class "Default")
      (node (ref "A05") (pin "B1") (pinfunction "P$2_B1") (pintype "bidirectional"))
      (node (ref "A05") (pin "D1") (pinfunction "P$2_D1") (pintype "bidirectional"))
      (node (ref "A05") (pin "D2") (pinfunction "P$2_D2") (pintype "bidirectional"))
      (node (ref "A05") (pin "E1") (pinfunction "P$2_E1") (pintype "bidirectional"))
      (node (ref "A05") (pin "H1") (pinfunction "P$2_H1") (pintype "bidirectional"))
      (node (ref "A05") (pin "J1") (pinfunction "P$2_J1") (pintype "bidirectional"))
      (node (ref "A05") (pin "L1") (pinfunction "P$2_L1") (pintype "bidirectional"))
      (node (ref "A05") (pin "M1") (pinfunction "P$2_M1") (pintype "bidirectional"))
      (node (ref "A05") (pin "P1") (pinfunction "P$2_P1") (pintype "bidirectional"))
      (node (ref "A05") (pin "S1") (pinfunction "P$2_S1") (pintype "bidirectional"))
      (node (ref "A06") (pin "K2") (pinfunction "P$2_K2") (pintype "bidirectional"))
      (node (ref "A07") (pin "U1") (pinfunction "IN*_U1") (pintype "input"))
      (node (ref "A08") (pin "T2") (pinfunction "D_T2") (pintype "input"))
      (node (ref "A23") (pin "C1") (pinfunction "C_C1") (pintype "input"))
      (node (ref "A23") (pin "F2") (pinfunction "C_F2") (pintype "input"))
      (node (ref "A23") (pin "J1") (pinfunction "C_J1") (pintype "input"))
      (node (ref "A23") (pin "M2") (pinfunction "C_M2") (pintype "input"))
      (node (ref "A23") (pin "P1") (pinfunction "C_P1") (pintype "input"))
      (node (ref "A23") (pin "T2") (pinfunction "C_T2") (pintype "input"))
      (node (ref "A25") (pin "M1") (pinfunction "P$2_M1") (pintype "bidirectional"))
      (node (ref "A26") (pin "D2") (pinfunction "P$2_D2") (pintype "bidirectional"))
      (node (ref "A26") (pin "U2") (pinfunction "P$2_U2") (pintype "bidirectional"))
      (node (ref "A26") (pin "V1") (pinfunction "P$2_V1") (pintype "bidirectional"))
      (node (ref "AB01") (pin "AC2") (pinfunction "GND_AC2") (pintype "power_in"))
      (node (ref "AB01") (pin "AH2") (pinfunction "GND_AH2") (pintype "power_in"))
      (node (ref "AB01") (pin "AK2") (pinfunction "GND_AK2") (pintype "power_in"))
      (node (ref "AB01") (pin "AL2") (pinfunction "GND_AL2") (pintype "power_in"))
      (node (ref "AB01") (pin "AT1") (pinfunction "GND_AT1") (pintype "power_in"))
      (node (ref "AB01") (pin "BC2") (pinfunction "GND_BC2") (pintype "power_in"))
      (node (ref "AB01") (pin "BD2") (pinfunction "GND_BD2") (pintype "power_in"))
      (node (ref "AB01") (pin "BH2") (pinfunction "GND_BH2") (pintype "power_in"))
      (node (ref "AB01") (pin "BK2") (pinfunction "GND_BK2") (pintype "power_in"))
      (node (ref "AB01") (pin "BL2") (pinfunction "GND_BL2") (pintype "power_in"))
      (node (ref "AB01") (pin "BT1") (pinfunction "GND_BT1") (pintype "power_in"))
      (node (ref "AB19") (pin "AJ2") (pinfunction "P$2_AJ2") (pintype "bidirectional"))
      (node (ref "AB19") (pin "AR2") (pinfunction "P$2_AR2") (pintype "bidirectional"))
      (node (ref "AB19") (pin "AU2") (pinfunction "P$2_AU2") (pintype "bidirectional"))
      (node (ref "AB19") (pin "BF2") (pinfunction "P$2_BF2") (pintype "bidirectional"))
      (node (ref "AB19") (pin "BM2") (pinfunction "P$2_BM2") (pintype "bidirectional"))
      (node (ref "B05") (pin "C1") (pinfunction "C_C1") (pintype "input"))
      (node (ref "B05") (pin "F2") (pinfunction "C_F2") (pintype "input"))
      (node (ref "B05") (pin "J1") (pinfunction "C_J1") (pintype "input"))
      (node (ref "B05") (pin "M2") (pinfunction "C_M2") (pintype "input"))
      (node (ref "B05") (pin "P1") (pinfunction "C_P1") (pintype "input"))
      (node (ref "B22") (pin "T2") (pinfunction "C_T2") (pintype "input"))
      (node (ref "D05") (pin "B1") (pinfunction "P$2_B1") (pintype "bidirectional"))
      (node (ref "D05") (pin "D1") (pinfunction "P$2_D1") (pintype "bidirectional"))
      (node (ref "D05") (pin "D2") (pinfunction "P$2_D2") (pintype "bidirectional"))
      (node (ref "D05") (pin "E1") (pinfunction "P$2_E1") (pintype "bidirectional"))
      (node (ref "D05") (pin "H1") (pinfunction "P$2_H1") (pintype "bidirectional"))
      (node (ref "D05") (pin "J1") (pinfunction "P$2_J1") (pintype "bidirectional"))
      (node (ref "D05") (pin "L1") (pinfunction "P$2_L1") (pintype "bidirectional"))
      (node (ref "D05") (pin "M1") (pinfunction "P$2_M1") (pintype "bidirectional"))
      (node (ref "D05") (pin "P1") (pinfunction "P$2_P1") (pintype "bidirectional"))
      (node (ref "D05") (pin "S1") (pinfunction "P$2_S1") (pintype "bidirectional"))
      (node (ref "D06") (pin "K2") (pinfunction "P$2_K2") (pintype "bidirectional"))
      (node (ref "D07") (pin "U1") (pinfunction "IN*_U1") (pintype "input"))
      (node (ref "D11") (pin "P1") (pinfunction "D_P1") (pintype "input"))
      (node (ref "D11") (pin "T2") (pinfunction "D_T2") (pintype "input"))
    )
    (net (code "87") (name "IOP_1") (class "Default")
      (node (ref "A02") (pin "K2") (pinfunction "P$2_K2") (pintype "bidirectional"))
      (node (ref "C04") (pin "P2") (pinfunction "P2_P2") (pintype "input"))
      (node (ref "C05") (pin "P2") (pinfunction "P2_P2") (pintype "input"))
      (node (ref "D02") (pin "K2") (pinfunction "P$2_K2") (pintype "bidirectional"))
    )
    (net (code "88") (name "IOP_2") (class "Default")
      (node (ref "A02") (pin "M2") (pinfunction "P$2_M2") (pintype "bidirectional"))
      (node (ref "C04") (pin "R2") (pinfunction "R2_R2") (pintype "input"))
      (node (ref "C05") (pin "R2") (pinfunction "R2_R2") (pintype "input"))
      (node (ref "D02") (pin "M2") (pinfunction "P$2_M2") (pintype "bidirectional"))
    )
    (net (code "89") (name "IOP_4") (class "Default")
      (node (ref "A02") (pin "P2") (pinfunction "P$2_P2") (pintype "bidirectional"))
      (node (ref "C04") (pin "S2") (pinfunction "S2_S2") (pintype "input"))
      (node (ref "C05") (pin "S2") (pinfunction "S2_S2") (pintype "input"))
      (node (ref "D02") (pin "P2") (pinfunction "P$2_P2") (pintype "bidirectional"))
    )
    (net (code "90") (name "I{slash}O_B-BRK") (class "Default")
      (node (ref "A05") (pin "P2") (pinfunction "P$2_P2") (pintype "bidirectional"))
      (node (ref "C01") (pin "D1") (pinfunction "IN_D1") (pintype "input"))
      (node (ref "D05") (pin "P2") (pinfunction "P$2_P2") (pintype "bidirectional"))
    )
    (net (code "91") (name "I{slash}O_B-RUN") (class "Default")
      (node (ref "A04") (pin "S2") (pinfunction "P$2_S2") (pintype "bidirectional"))
      (node (ref "C01") (pin "A1") (pinfunction "IN1_A1") (pintype "input"))
      (node (ref "D04") (pin "S2") (pinfunction "P$2_S2") (pintype "bidirectional"))
    )
    (net (code "92") (name "I{slash}O_BAC_00") (class "Default")
      (node (ref "A02") (pin "B1") (pinfunction "P$2_B1") (pintype "bidirectional"))
      (node (ref "C03") (pin "A1") (pinfunction "IN1_A1") (pintype "input"))
      (node (ref "D02") (pin "B1") (pinfunction "P$2_B1") (pintype "bidirectional"))
    )
    (net (code "93") (name "I{slash}O_BAC_01") (class "Default")
      (node (ref "A02") (pin "D1") (pinfunction "P$2_D1") (pintype "bidirectional"))
      (node (ref "C03") (pin "D1") (pinfunction "IN2_D1") (pintype "input"))
      (node (ref "D02") (pin "D1") (pinfunction "P$2_D1") (pintype "bidirectional"))
    )
    (net (code "94") (name "I{slash}O_BAC_02") (class "Default")
      (node (ref "A02") (pin "E1") (pinfunction "P$2_E1") (pintype "bidirectional"))
      (node (ref "C03") (pin "F1") (pinfunction "IN3_F1") (pintype "input"))
      (node (ref "D02") (pin "E1") (pinfunction "P$2_E1") (pintype "bidirectional"))
    )
    (net (code "95") (name "I{slash}O_BAC_03") (class "Default")
      (node (ref "A02") (pin "H1") (pinfunction "P$2_H1") (pintype "bidirectional"))
      (node (ref "C03") (pin "J1") (pinfunction "IN4_J1") (pintype "input"))
      (node (ref "D02") (pin "H1") (pinfunction "P$2_H1") (pintype "bidirectional"))
    )
    (net (code "96") (name "I{slash}O_BAC_04") (class "Default")
      (node (ref "A02") (pin "J1") (pinfunction "P$2_J1") (pintype "bidirectional"))
      (node (ref "C03") (pin "L1") (pinfunction "IN5_L1") (pintype "input"))
      (node (ref "D02") (pin "J1") (pinfunction "P$2_J1") (pintype "bidirectional"))
    )
    (net (code "97") (name "I{slash}O_BAC_05") (class "Default")
      (node (ref "A02") (pin "L1") (pinfunction "P$2_L1") (pintype "bidirectional"))
      (node (ref "C03") (pin "N1") (pinfunction "IN6_N1") (pintype "input"))
      (node (ref "D02") (pin "L1") (pinfunction "P$2_L1") (pintype "bidirectional"))
    )
    (net (code "98") (name "I{slash}O_BAC_06") (class "Default")
      (node (ref "A02") (pin "M1") (pinfunction "P$2_M1") (pintype "bidirectional"))
      (node (ref "C03") (pin "R1") (pinfunction "IN7_R1") (pintype "input"))
      (node (ref "D02") (pin "M1") (pinfunction "P$2_M1") (pintype "bidirectional"))
    )
    (net (code "99") (name "I{slash}O_BAC_07") (class "Default")
      (node (ref "A02") (pin "P1") (pinfunction "P$2_P1") (pintype "bidirectional"))
      (node (ref "C03") (pin "V1") (pinfunction "IN8_V1") (pintype "input"))
      (node (ref "D02") (pin "P1") (pinfunction "P$2_P1") (pintype "bidirectional"))
    )
    (net (code "100") (name "I{slash}O_BAC_08") (class "Default")
      (node (ref "A02") (pin "S1") (pinfunction "P$2_S1") (pintype "bidirectional"))
      (node (ref "C03") (pin "E2") (pinfunction "IN9_E2") (pintype "input"))
      (node (ref "D02") (pin "S1") (pinfunction "P$2_S1") (pintype "bidirectional"))
    )
    (net (code "101") (name "I{slash}O_BAC_09") (class "Default")
      (node (ref "A02") (pin "D2") (pinfunction "P$2_D2") (pintype "bidirectional"))
      (node (ref "C03") (pin "H2") (pinfunction "IN10_H2") (pintype "input"))
      (node (ref "D02") (pin "D2") (pinfunction "P$2_D2") (pintype "bidirectional"))
    )
    (net (code "102") (name "I{slash}O_BAC_10") (class "Default")
      (node (ref "A02") (pin "E2") (pinfunction "P$2_E2") (pintype "bidirectional"))
      (node (ref "C03") (pin "K2") (pinfunction "IN11_K2") (pintype "input"))
      (node (ref "D02") (pin "E2") (pinfunction "P$2_E2") (pintype "bidirectional"))
    )
    (net (code "103") (name "I{slash}O_BAC_11") (class "Default")
      (node (ref "A02") (pin "H2") (pinfunction "P$2_H2") (pintype "bidirectional"))
      (node (ref "C03") (pin "M2") (pinfunction "IN12_M2") (pintype "input"))
      (node (ref "D02") (pin "H2") (pinfunction "P$2_H2") (pintype "bidirectional"))
    )
    (net (code "104") (name "I{slash}O_BMB_00") (class "Default")
      (node (ref "A03") (pin "B1") (pinfunction "P$2_B1") (pintype "bidirectional"))
      (node (ref "C02") (pin "A1") (pinfunction "IN1_A1") (pintype "input"))
      (node (ref "D03") (pin "B1") (pinfunction "P$2_B1") (pintype "bidirectional"))
    )
    (net (code "105") (name "I{slash}O_BMB_01") (class "Default")
      (node (ref "A03") (pin "D1") (pinfunction "P$2_D1") (pintype "bidirectional"))
      (node (ref "C02") (pin "D1") (pinfunction "IN2_D1") (pintype "input"))
      (node (ref "D03") (pin "D1") (pinfunction "P$2_D1") (pintype "bidirectional"))
    )
    (net (code "106") (name "I{slash}O_BMB_02") (class "Default")
      (node (ref "A03") (pin "E1") (pinfunction "P$2_E1") (pintype "bidirectional"))
      (node (ref "C02") (pin "F1") (pinfunction "IN3_F1") (pintype "input"))
      (node (ref "D03") (pin "E1") (pinfunction "P$2_E1") (pintype "bidirectional"))
    )
    (net (code "107") (name "I{slash}O_BMB_03") (class "Default")
      (node (ref "A03") (pin "J1") (pinfunction "P$2_J1") (pintype "bidirectional"))
      (node (ref "C02") (pin "J1") (pinfunction "IN4_J1") (pintype "input"))
      (node (ref "C04") (pin "D2") (pinfunction "D2_D2") (pintype "input"))
      (node (ref "C05") (pin "D2") (pinfunction "D2_D2") (pintype "input"))
      (node (ref "D03") (pin "J1") (pinfunction "P$2_J1") (pintype "bidirectional"))
    )
    (net (code "108") (name "I{slash}O_BMB_04") (class "Default")
      (node (ref "A03") (pin "M1") (pinfunction "P$2_M1") (pintype "bidirectional"))
      (node (ref "C02") (pin "L1") (pinfunction "IN5_L1") (pintype "input"))
      (node (ref "C04") (pin "E2") (pinfunction "E2_E2") (pintype "input"))
      (node (ref "C05") (pin "E2") (pinfunction "E2_E2") (pintype "input"))
      (node (ref "D03") (pin "M1") (pinfunction "P$2_M1") (pintype "bidirectional"))
    )
    (net (code "109") (name "I{slash}O_BMB_05") (class "Default")
      (node (ref "A03") (pin "S1") (pinfunction "P$2_S1") (pintype "bidirectional"))
      (node (ref "C02") (pin "N1") (pinfunction "IN6_N1") (pintype "input"))
      (node (ref "C04") (pin "F2") (pinfunction "F2_F2") (pintype "input"))
      (node (ref "C05") (pin "F2") (pinfunction "F2_F2") (pintype "input"))
      (node (ref "D03") (pin "S1") (pinfunction "P$2_S1") (pintype "bidirectional"))
    )
    (net (code "110") (name "I{slash}O_BMB_06") (class "Default")
      (node (ref "A03") (pin "E2") (pinfunction "P$2_E2") (pintype "bidirectional"))
      (node (ref "C02") (pin "R1") (pinfunction "IN7_R1") (pintype "input"))
      (node (ref "C04") (pin "H2") (pinfunction "H2_H2") (pintype "input"))
      (node (ref "C05") (pin "H2") (pinfunction "H2_H2") (pintype "input"))
      (node (ref "D03") (pin "E2") (pinfunction "P$2_E2") (pintype "bidirectional"))
    )
    (net (code "111") (name "I{slash}O_BMB_07") (class "Default")
      (node (ref "A03") (pin "K2") (pinfunction "P$2_K2") (pintype "bidirectional"))
      (node (ref "C02") (pin "V1") (pinfunction "IN8_V1") (pintype "input"))
      (node (ref "C04") (pin "J2") (pinfunction "J2_J2") (pintype "input"))
      (node (ref "C05") (pin "J2") (pinfunction "J2_J2") (pintype "input"))
      (node (ref "D03") (pin "K2") (pinfunction "P$2_K2") (pintype "bidirectional"))
    )
    (net (code "112") (name "I{slash}O_BMB_08") (class "Default")
      (node (ref "A03") (pin "P2") (pinfunction "P$2_P2") (pintype "bidirectional"))
      (node (ref "C02") (pin "E2") (pinfunction "IN9_E2") (pintype "input"))
      (node (ref "C05") (pin "K2") (pinfunction "K2_K2") (pintype "input"))
      (node (ref "D03") (pin "P2") (pinfunction "P$2_P2") (pintype "bidirectional"))
    )
    (net (code "113") (name "I{slash}O_BMB_09") (class "Default")
      (node (ref "A03") (pin "S2") (pinfunction "P$2_S2") (pintype "bidirectional"))
      (node (ref "C02") (pin "H2") (pinfunction "IN10_H2") (pintype "input"))
      (node (ref "D03") (pin "S2") (pinfunction "P$2_S2") (pintype "bidirectional"))
    )
    (net (code "114") (name "I{slash}O_BMB_10") (class "Default")
      (node (ref "A03") (pin "T2") (pinfunction "P$2_T2") (pintype "bidirectional"))
      (node (ref "C02") (pin "K2") (pinfunction "IN11_K2") (pintype "input"))
      (node (ref "D03") (pin "T2") (pinfunction "P$2_T2") (pintype "bidirectional"))
    )
    (net (code "115") (name "I{slash}O_BMB_11") (class "Default")
      (node (ref "A03") (pin "V2") (pinfunction "P$2_V2") (pintype "bidirectional"))
      (node (ref "C02") (pin "M2") (pinfunction "IN12_M2") (pintype "input"))
      (node (ref "D03") (pin "V2") (pinfunction "P$2_V2") (pintype "bidirectional"))
    )
    (net (code "116") (name "I{slash}O_DATA_IN") (class "Default")
      (node (ref "A05") (pin "M2") (pinfunction "P$2_M2") (pintype "bidirectional"))
      (node (ref "B05") (pin "J2") (pinfunction "E_J2") (pintype "open_collector"))
      (node (ref "D05") (pin "M2") (pinfunction "P$2_M2") (pintype "bidirectional"))
    )
    (net (code "117") (name "I{slash}O_PWR_CLR") (class "Default")
      (node (ref "A02") (pin "V2") (pinfunction "P$2_V2") (pintype "bidirectional"))
      (node (ref "C05") (pin "H1") (pinfunction "IN1_H1") (pintype "input"))
      (node (ref "D02") (pin "V2") (pinfunction "P$2_V2") (pintype "bidirectional"))
    )
    (net (code "118") (name "I{slash}O_TS03") (class "Default")
      (node (ref "A02") (pin "S2") (pinfunction "P$2_S2") (pintype "bidirectional"))
      (node (ref "C04") (pin "H1") (pinfunction "IN1_H1") (pintype "input"))
      (node (ref "D02") (pin "S2") (pinfunction "P$2_S2") (pintype "bidirectional"))
    )
    (net (code "119") (name "I{slash}O_TS04") (class "Default")
      (node (ref "A02") (pin "T2") (pinfunction "P$2_T2") (pintype "bidirectional"))
      (node (ref "D02") (pin "T2") (pinfunction "P$2_T2") (pintype "bidirectional"))
    )
    (net (code "120") (name "I{slash}~{O_0_TO_AC}") (class "Default")
      (node (ref "A04") (pin "P2") (pinfunction "P$2_P2") (pintype "bidirectional"))
      (node (ref "B05") (pin "L1") (pinfunction "E_L1") (pintype "open_collector"))
      (node (ref "D04") (pin "P2") (pinfunction "P$2_P2") (pintype "bidirectional"))
    )
    (net (code "121") (name "I{slash}~{O_1_TO_CA_INH}") (class "Default")
      (node (ref "A06") (pin "M2") (pinfunction "P$2_M2") (pintype "bidirectional"))
      (node (ref "B05") (pin "N2") (pinfunction "D_N2") (pintype "open_collector"))
      (node (ref "D06") (pin "M2") (pinfunction "P$2_M2") (pintype "bidirectional"))
    )
    (net (code "122") (name "I{slash}~{O_ADDR_ACC}") (class "Default")
      (node (ref "A05") (pin "S2") (pinfunction "P$2_S2") (pintype "bidirectional"))
      (node (ref "C02") (pin "U2") (pinfunction "IN15_U2") (pintype "input"))
      (node (ref "D05") (pin "S2") (pinfunction "P$2_S2") (pintype "bidirectional"))
    )
    (net (code "123") (name "I{slash}~{O_BMB_03}") (class "Default")
      (node (ref "A03") (pin "H1") (pinfunction "P$2_H1") (pintype "bidirectional"))
      (node (ref "D03") (pin "H1") (pinfunction "P$2_H1") (pintype "bidirectional"))
    )
    (net (code "124") (name "I{slash}~{O_BMB_04}") (class "Default")
      (node (ref "A03") (pin "L1") (pinfunction "P$2_L1") (pintype "bidirectional"))
      (node (ref "D03") (pin "L1") (pinfunction "P$2_L1") (pintype "bidirectional"))
    )
    (net (code "125") (name "I{slash}~{O_BMB_05}") (class "Default")
      (node (ref "A03") (pin "P1") (pinfunction "P$2_P1") (pintype "bidirectional"))
      (node (ref "D03") (pin "P1") (pinfunction "P$2_P1") (pintype "bidirectional"))
    )
    (net (code "126") (name "I{slash}~{O_BMB_06}") (class "Default")
      (node (ref "A03") (pin "D2") (pinfunction "P$2_D2") (pintype "bidirectional"))
      (node (ref "D03") (pin "D2") (pinfunction "P$2_D2") (pintype "bidirectional"))
    )
    (net (code "127") (name "I{slash}~{O_BMB_07}") (class "Default")
      (node (ref "A03") (pin "H2") (pinfunction "P$2_H2") (pintype "bidirectional"))
      (node (ref "D03") (pin "H2") (pinfunction "P$2_H2") (pintype "bidirectional"))
    )
    (net (code "128") (name "I{slash}~{O_BMB_08}") (class "Default")
      (node (ref "A03") (pin "M2") (pinfunction "P$2_M2") (pintype "bidirectional"))
      (node (ref "C04") (pin "K2") (pinfunction "K2_K2") (pintype "input"))
      (node (ref "D03") (pin "M2") (pinfunction "P$2_M2") (pintype "bidirectional"))
    )
    (net (code "129") (name "I{slash}~{O_BRK_RQ}") (class "Default")
      (node (ref "A05") (pin "K2") (pinfunction "P$2_K2") (pintype "bidirectional"))
      (node (ref "B05") (pin "D1") (pinfunction "D_D1") (pintype "open_collector"))
      (node (ref "D05") (pin "K2") (pinfunction "P$2_K2") (pintype "bidirectional"))
    )
    (net (code "130") (name "I{slash}~{O_BWC0}") (class "Default")
      (node (ref "A06") (pin "P2") (pinfunction "P$2_P2") (pintype "bidirectional"))
      (node (ref "C01") (pin "F1") (pinfunction "IN_F1") (pintype "input"))
      (node (ref "D06") (pin "P2") (pinfunction "P$2_P2") (pintype "bidirectional"))
    )
    (net (code "131") (name "I{slash}~{O_INT_RQ}") (class "Default")
      (node (ref "A04") (pin "M2") (pinfunction "P$2_M2") (pintype "bidirectional"))
      (node (ref "B05") (pin "E1") (pinfunction "E_E1") (pintype "open_collector"))
      (node (ref "D04") (pin "M2") (pinfunction "P$2_M2") (pintype "bidirectional"))
    )
    (net (code "132") (name "I{slash}~{O_SKP_RQ}") (class "Default")
      (node (ref "A04") (pin "K2") (pinfunction "P$2_K2") (pintype "bidirectional"))
      (node (ref "B05") (pin "K1") (pinfunction "D_K1") (pintype "open_collector"))
      (node (ref "D04") (pin "K2") (pinfunction "P$2_K2") (pintype "bidirectional"))
    )
    (net (code "133") (name "LDMF") (class "Default")
      (node (ref "C05") (pin "E1") (pinfunction "E1_E1") (pintype "output"))
      (node (ref "D11") (pin "B1") (pinfunction "C_B1") (pintype "input"))
      (node (ref "D11") (pin "D2") (pinfunction "C_D2") (pintype "input"))
      (node (ref "D11") (pin "H1") (pinfunction "C_H1") (pintype "input"))
    )
    (net (code "134") (name "LPB_00") (class "Default")
      (node (ref "A25") (pin "T2") (pinfunction "P$2_T2") (pintype "bidirectional"))
      (node (ref "C08") (pin "D1") (pinfunction "IN2B_D1") (pintype "input"))
      (node (ref "D08") (pin "E1") (pinfunction "E1_E1") (pintype "output"))
    )
    (net (code "135") (name "LPB_01") (class "Default")
      (node (ref "A25") (pin "U2") (pinfunction "P$2_U2") (pintype "bidirectional"))
      (node (ref "C08") (pin "K1") (pinfunction "IN2B_K1") (pintype "input"))
      (node (ref "D08") (pin "L1") (pinfunction "L1_L1") (pintype "output"))
    )
    (net (code "136") (name "LPB_02") (class "Default")
      (node (ref "A25") (pin "V2") (pinfunction "P$2_V2") (pintype "bidirectional"))
      (node (ref "C08") (pin "R1") (pinfunction "IN2B_R1") (pintype "input"))
      (node (ref "D08") (pin "S1") (pinfunction "S1_S1") (pintype "output"))
    )
    (net (code "137") (name "LPB_03") (class "Default")
      (node (ref "A26") (pin "A2") (pinfunction "P$2_A2") (pintype "bidirectional"))
      (node (ref "C08") (pin "H2") (pinfunction "IN2B_H2") (pintype "input"))
      (node (ref "D08") (pin "H2") (pinfunction "H2_H2") (pintype "output"))
    )
    (net (code "138") (name "LPB_04") (class "Default")
      (node (ref "A26") (pin "B2") (pinfunction "P$2_B2") (pintype "bidirectional"))
      (node (ref "C08") (pin "N2") (pinfunction "IN2B_N2") (pintype "input"))
      (node (ref "D08") (pin "P2") (pinfunction "P2_P2") (pintype "output"))
    )
    (net (code "139") (name "LPB_05") (class "Default")
      (node (ref "A26") (pin "C2") (pinfunction "P$2_C2") (pintype "bidirectional"))
      (node (ref "C08") (pin "U2") (pinfunction "IN2B_U2") (pintype "input"))
      (node (ref "D08") (pin "V2") (pinfunction "V2_V2") (pintype "output"))
    )
    (net (code "140") (name "LPB_NOT_EQ_1") (class "Default")
      (node (ref "A10") (pin "M1") (pinfunction "IN2_M1") (pintype "input"))
      (node (ref "D10") (pin "V2") (pinfunction "OUT_V2") (pintype "output"))
    )
    (net (code "141") (name "LPB_TO_DTB") (class "Default")
      (node (ref "A11") (pin "T2") (pinfunction "OUT_T2") (pintype "output"))
      (node (ref "C08") (pin "C1") (pinfunction "IN2A_C1") (pintype "input"))
      (node (ref "C08") (pin "F2") (pinfunction "IN2A_F2") (pintype "input"))
      (node (ref "C08") (pin "J1") (pinfunction "IN2A_J1") (pintype "input"))
      (node (ref "C08") (pin "M2") (pinfunction "IN2A_M2") (pintype "input"))
      (node (ref "C08") (pin "P1") (pinfunction "IN2A_P1") (pintype "input"))
      (node (ref "C08") (pin "T2") (pinfunction "IN2A_T2") (pintype "input"))
    )
    (net (code "142") (name "MC00") (class "Default")
      (node (ref "A26") (pin "S1") (pinfunction "P$2_S1") (pintype "bidirectional"))
      (node (ref "B13") (pin "E1") (pinfunction "1_E1") (pintype "output"))
      (node (ref "B13") (pin "E2") (pinfunction "D_E2") (pintype "input"))
      (node (ref "D10") (pin "D2") (pinfunction "IN5_D2") (pintype "input"))
    )
    (net (code "143") (name "MC01") (class "Default")
      (node (ref "A08") (pin "L2") (pinfunction "C_L2") (pintype "input"))
      (node (ref "A26") (pin "T1") (pinfunction "P$2_T1") (pintype "bidirectional"))
      (node (ref "B13") (pin "H2") (pinfunction "1_H2") (pintype "output"))
      (node (ref "B13") (pin "J1") (pinfunction "D_J1") (pintype "input"))
      (node (ref "C11") (pin "E1") (pinfunction "IN2_E1") (pintype "input"))
    )
    (net (code "144") (name "MC02") (class "Default")
      (node (ref "A26") (pin "U1") (pinfunction "P$2_U1") (pintype "bidirectional"))
      (node (ref "B11") (pin "U2") (pinfunction "IN2_U2") (pintype "input"))
      (node (ref "B13") (pin "L1") (pinfunction "1_L1") (pintype "output"))
      (node (ref "D12") (pin "D2") (pinfunction "IN1_D2") (pintype "input"))
      (node (ref "D12") (pin "E2") (pinfunction "IN2_E2") (pintype "input"))
    )
    (net (code "145") (name "MF00") (class "Default")
      (node (ref "A25") (pin "V1") (pinfunction "P$2_V1") (pintype "bidirectional"))
      (node (ref "D11") (pin "E1") (pinfunction "1_E1") (pintype "output"))
    )
    (net (code "146") (name "MF01") (class "Default")
      (node (ref "A26") (pin "A1") (pinfunction "P$2_A1") (pintype "bidirectional"))
      (node (ref "D11") (pin "H2") (pinfunction "1_H2") (pintype "output"))
    )
    (net (code "147") (name "MF02") (class "Default")
      (node (ref "A26") (pin "B1") (pinfunction "P$2_B1") (pintype "bidirectional"))
      (node (ref "D11") (pin "L1") (pinfunction "1_L1") (pintype "output"))
    )
    (net (code "148") (name "MKT") (class "Default")
      (node (ref "A26") (pin "H2") (pinfunction "P$2_H2") (pintype "bidirectional"))
      (node (ref "B12") (pin "S2") (pinfunction "IN2_S2") (pintype "input"))
      (node (ref "B13") (pin "V2") (pinfunction "1_V2") (pintype "output"))
      (node (ref "B15") (pin "L1") (pinfunction "IN1_L1") (pintype "input"))
      (node (ref "C15") (pin "L2") (pinfunction "IN1_L2") (pintype "input"))
    )
    (net (code "149") (name "MKTK") (class "Default")
      (node (ref "A08") (pin "R2") (pinfunction "0_R2") (pintype "output"))
      (node (ref "A25") (pin "P1") (pinfunction "P$2_P1") (pintype "bidirectional"))
    )
    (net (code "150") (name "MK_BLK_END") (class "Default")
      (node (ref "A09") (pin "T2") (pinfunction "IN3_T2") (pintype "input"))
      (node (ref "CD18") (pin "BU1") (pinfunction "BU1_BU1") (pintype "output"))
    )
    (net (code "151") (name "MK_BLK_MK") (class "Default")
      (node (ref "CD18") (pin "AE2") (pinfunction "AE2_AE2") (pintype "output"))
      (node (ref "D10") (pin "A1") (pinfunction "IN1_A1") (pintype "input"))
      (node (ref "D10") (pin "B1") (pinfunction "IN2_B1") (pintype "input"))
    )
    (net (code "152") (name "MK_BLK_START") (class "Default")
      (node (ref "CD18") (pin "AJ2") (pinfunction "AJ2_AJ2") (pintype "output"))
    )
    (net (code "153") (name "MK_BLK_SYNC") (class "Default")
      (node (ref "CD18") (pin "BS2") (pinfunction "BS2_BS2") (pintype "output"))
    )
    (net (code "154") (name "MK_DATA") (class "Default")
      (node (ref "CD18") (pin "BP2") (pinfunction "BP2_BP2") (pintype "output"))
    )
    (net (code "155") (name "MK_DATA_SYNC") (class "Default")
      (node (ref "CD18") (pin "AH1") (pinfunction "AH1_AH1") (pintype "output"))
    )
    (net (code "156") (name "MK_END") (class "Default")
      (node (ref "A08") (pin "C1") (pinfunction "D_C1") (pintype "input"))
      (node (ref "CD18") (pin "AF2") (pinfunction "AF2_AF2") (pintype "output"))
    )
    (net (code "157") (name "MOVE") (class "Default")
      (node (ref "D07") (pin "D2") (pinfunction "O0_D2") (pintype "output"))
    )
    (net (code "158") (name "MR00") (class "Default")
      (node (ref "A25") (pin "D1") (pinfunction "P$2_D1") (pintype "bidirectional"))
      (node (ref "B07") (pin "P2") (pinfunction "P2_P2") (pintype "output"))
      (node (ref "B14") (pin "M2") (pinfunction "D_M2") (pintype "input"))
    )
    (net (code "159") (name "MR01") (class "Default")
      (node (ref "A25") (pin "E1") (pinfunction "P$2_E1") (pintype "bidirectional"))
      (node (ref "C07") (pin "P2") (pinfunction "P2_P2") (pintype "output"))
      (node (ref "C12") (pin "B1") (pinfunction "IN2_B1") (pintype "input"))
    )
    (net (code "160") (name "Net-(A08D-D)") (class "Default")
      (node (ref "A08") (pin "E2") (pinfunction "D_E2") (pintype "input"))
      (node (ref "A09") (pin "L1") (pinfunction "OUT_L1") (pintype "output"))
    )
    (net (code "161") (name "Net-(A08E-S)") (class "Default")
      (node (ref "A08") (pin "K1") (pinfunction "S_K1") (pintype "input"))
      (node (ref "A11") (pin "E1") (pinfunction "OUT_E1") (pintype "output"))
    )
    (net (code "162") (name "Net-(A08F-D)") (class "Default")
      (node (ref "A08") (pin "M2") (pinfunction "D_M2") (pintype "input"))
      (node (ref "A09") (pin "J2") (pinfunction "OUT_J2") (pintype "output"))
    )
    (net (code "163") (name "Net-(A08G-C)") (class "Default")
      (node (ref "A08") (pin "N1") (pinfunction "C_N1") (pintype "input"))
      (node (ref "A11") (pin "D2") (pinfunction "OUT_D2") (pintype "output"))
    )
    (net (code "164") (name "Net-(A08G-D)") (class "Default")
      (node (ref "A08") (pin "P1") (pinfunction "D_P1") (pintype "input"))
      (node (ref "A10") (pin "N1") (pinfunction "OUT_N1") (pintype "output"))
    )
    (net (code "165") (name "Net-(A08H-S)") (class "Default")
      (node (ref "A08") (pin "U2") (pinfunction "S_U2") (pintype "input"))
      (node (ref "B10") (pin "S1") (pinfunction "OUT_S1") (pintype "output"))
    )
    (net (code "166") (name "Net-(A09A-OUT)") (class "Default")
      (node (ref "A09") (pin "E1") (pinfunction "OUT_E1") (pintype "output"))
      (node (ref "A11") (pin "A1") (pinfunction "IN_A1") (pintype "input"))
    )
    (net (code "167") (name "Net-(A09D-IN4)") (class "Default")
      (node (ref "A09") (pin "H2") (pinfunction "IN4_H2") (pintype "input"))
      (node (ref "A11") (pin "B1") (pinfunction "OUT_B1") (pintype "output"))
    )
    (net (code "168") (name "Net-(A09E-IN1)") (class "Default")
      (node (ref "A09") (pin "F1") (pinfunction "IN1_F1") (pintype "input"))
      (node (ref "C10") (pin "P2") (pinfunction "OUT_P2") (pintype "output"))
    )
    (net (code "169") (name "Net-(A09E-IN3)") (class "Default")
      (node (ref "A09") (pin "J1") (pinfunction "IN3_J1") (pintype "input"))
      (node (ref "A10") (pin "K1") (pinfunction "OUT_K1") (pintype "output"))
    )
    (net (code "170") (name "Net-(A09F-OUT)") (class "Default")
      (node (ref "A09") (pin "P2") (pinfunction "OUT_P2") (pintype "output"))
      (node (ref "A11") (pin "F1") (pinfunction "IN_F1") (pintype "input"))
    )
    (net (code "171") (name "Net-(A09G-OUT)") (class "Default")
      (node (ref "A09") (pin "S1") (pinfunction "OUT_S1") (pintype "output"))
      (node (ref "A10") (pin "U2") (pinfunction "IN2_U2") (pintype "input"))
    )
    (net (code "172") (name "Net-(A09J-IN4)") (class "Default")
      (node (ref "A09") (pin "U2") (pinfunction "IN4_U2") (pintype "input"))
      (node (ref "C17") (pin "R2") (pinfunction "OUT_R2") (pintype "output"))
    )
    (net (code "173") (name "Net-(A09J-OUT)") (class "Default")
      (node (ref "A09") (pin "V2") (pinfunction "OUT_V2") (pintype "output"))
      (node (ref "A11") (pin "S2") (pinfunction "IN_S2") (pintype "input"))
    )
    (net (code "174") (name "Net-(A10A-IN2)") (class "Default")
      (node (ref "A10") (pin "B1") (pinfunction "IN2_B1") (pintype "input"))
      (node (ref "A10") (pin "F1") (pinfunction "OUT_F1") (pintype "output"))
      (node (ref "B15") (pin "P2") (pinfunction "IN1_P2") (pintype "input"))
    )
    (net (code "175") (name "Net-(A10A-OUT)") (class "Default")
      (node (ref "A10") (pin "C1") (pinfunction "OUT_C1") (pintype "output"))
      (node (ref "A10") (pin "D1") (pinfunction "IN1_D1") (pintype "input"))
    )
    (net (code "176") (name "Net-(A10C-OUT)") (class "Default")
      (node (ref "A10") (pin "F2") (pinfunction "OUT_F2") (pintype "output"))
      (node (ref "A10") (pin "J2") (pinfunction "IN2_J2") (pintype "input"))
    )
    (net (code "177") (name "Net-(A10J-OUT)") (class "Default")
      (node (ref "A10") (pin "S1") (pinfunction "OUT_S1") (pintype "output"))
      (node (ref "A11") (pin "C1") (pinfunction "IN_C1") (pintype "input"))
    )
    (net (code "178") (name "Net-(A10K-OUT)") (class "Default")
      (node (ref "A10") (pin "S2") (pinfunction "OUT_S2") (pintype "output"))
      (node (ref "A10") (pin "T2") (pinfunction "IN1_T2") (pintype "input"))
    )
    (net (code "179") (name "Net-(A10N-OUT)") (class "Default")
      (node (ref "A10") (pin "V2") (pinfunction "OUT_V2") (pintype "output"))
      (node (ref "A11") (pin "D1") (pinfunction "IN_D1") (pintype "input"))
    )
    (net (code "180") (name "Net-(A11G-OUT)") (class "Default")
      (node (ref "A11") (pin "H1") (pinfunction "OUT_H1") (pintype "output"))
      (node (ref "A12") (pin "B1") (pinfunction "IN2_B1") (pintype "input"))
      (node (ref "A12") (pin "D1") (pinfunction "IN1_D1") (pintype "input"))
    )
    (net (code "181") (name "Net-(A11N-IN)") (class "Default")
      (node (ref "A11") (pin "P2") (pinfunction "IN_P2") (pintype "input"))
      (node (ref "A14") (pin "F2") (pinfunction "F2_F2") (pintype "output"))
    )
    (net (code "182") (name "Net-(A11O-IN)") (class "Default")
      (node (ref "A11") (pin "R1") (pinfunction "IN_R1") (pintype "input"))
      (node (ref "B11") (pin "S2") (pinfunction "OUT_S2") (pintype "output"))
    )
    (net (code "183") (name "Net-(A11Q-IN)") (class "Default")
      (node (ref "A11") (pin "V1") (pinfunction "IN_V1") (pintype "input"))
      (node (ref "B08") (pin "V2") (pinfunction "OUT_V2") (pintype "output"))
    )
    (net (code "184") (name "Net-(A11R-IN)") (class "Default")
      (node (ref "A11") (pin "U2") (pinfunction "IN_U2") (pintype "input"))
      (node (ref "A14") (pin "T2") (pinfunction "F2_T2") (pintype "output"))
    )
    (net (code "185") (name "Net-(A12C-OUT)") (class "Default")
      (node (ref "A12") (pin "F2") (pinfunction "OUT_F2") (pintype "output"))
      (node (ref "B10") (pin "A1") (pinfunction "IN1_A1") (pintype "input"))
      (node (ref "B10") (pin "B1") (pinfunction "IN2_B1") (pintype "input"))
    )
    (net (code "186") (name "Net-(A12F-IN2)") (class "Default")
      (node (ref "A12") (pin "J1") (pinfunction "IN2_J1") (pintype "input"))
      (node (ref "A12") (pin "N1") (pinfunction "OUT_N1") (pintype "output"))
      (node (ref "A12") (pin "P1") (pinfunction "IN1_P1") (pintype "input"))
    )
    (net (code "187") (name "Net-(A12G-OUT)") (class "Default")
      (node (ref "A12") (pin "K2") (pinfunction "OUT_K2") (pintype "output"))
      (node (ref "B10") (pin "C1") (pinfunction "IN3_C1") (pintype "input"))
      (node (ref "B10") (pin "D1") (pinfunction "IN4_D1") (pintype "input"))
    )
    (net (code "188") (name "Net-(A12I-OUT)") (class "Default")
      (node (ref "A12") (pin "N2") (pinfunction "OUT_N2") (pintype "output"))
      (node (ref "A12") (pin "T2") (pinfunction "IN1_T2") (pintype "input"))
    )
    (net (code "189") (name "Net-(A12K-OUT)") (class "Default")
      (node (ref "A12") (pin "S2") (pinfunction "OUT_S2") (pintype "output"))
      (node (ref "A12") (pin "U2") (pinfunction "IN2_U2") (pintype "input"))
    )
    (net (code "190") (name "Net-(A14-PadD2)") (class "Default")
      (node (ref "A14") (pin "D2") (pinfunction "D2_D2") (pintype "passive"))
      (node (ref "A14") (pin "E2") (pinfunction "E2_E2") (pintype "passive"))
    )
    (net (code "191") (name "Net-(A14-PadH1)") (class "Default")
      (node (ref "A14") (pin "H1") (pinfunction "H1_H1") (pintype "passive"))
      (node (ref "A14") (pin "L2") (pinfunction "L2_L2") (pintype "passive"))
    )
    (net (code "192") (name "Net-(A14D-D2)") (class "Default")
      (node (ref "A14") (pin "R2") (pinfunction "E2_R2") (pintype "passive"))
      (node (ref "A14") (pin "V2") (pinfunction "D2_V2") (pintype "passive"))
    )
    (net (code "193") (name "Net-(A14D-H1)") (class "Default")
      (node (ref "A14") (pin "S1") (pinfunction "H1_S1") (pintype "passive"))
      (node (ref "A14") (pin "S2") (pinfunction "L2_S2") (pintype "passive"))
    )
    (net (code "194") (name "Net-(A14D-H2)") (class "Default")
      (node (ref "A14") (pin "M2") (pinfunction "H2_M2") (pintype "input"))
      (node (ref "A14") (pin "N2") (pinfunction "J2_N2") (pintype "input"))
      (node (ref "A14") (pin "P2") (pinfunction "K2_P2") (pintype "input"))
      (node (ref "B15") (pin "F2") (pinfunction "OUT_F2") (pintype "output"))
    )
    (net (code "195") (name "Net-(A15A-IN3)") (class "Default")
      (node (ref "A15") (pin "C1") (pinfunction "IN3_C1") (pintype "input"))
      (node (ref "A15") (pin "D1") (pinfunction "IN4_D1") (pintype "input"))
      (node (ref "C17") (pin "D2") (pinfunction "OUT_D2") (pintype "output"))
    )
    (net (code "196") (name "Net-(A15D-IN1)") (class "Default")
      (node (ref "A15") (pin "D2") (pinfunction "IN1_D2") (pintype "input"))
      (node (ref "A15") (pin "E2") (pinfunction "IN2_E2") (pintype "input"))
      (node (ref "C17") (pin "F2") (pinfunction "OUT_F2") (pintype "output"))
    )
    (net (code "197") (name "Net-(A16-PadD2)") (class "Default")
      (node (ref "A16") (pin "D2") (pinfunction "D2_D2") (pintype "passive"))
      (node (ref "A16") (pin "E2") (pinfunction "E2_E2") (pintype "passive"))
    )
    (net (code "198") (name "Net-(A16C-D2)") (class "Default")
      (node (ref "A16") (pin "R2") (pinfunction "E2_R2") (pintype "passive"))
      (node (ref "A16") (pin "S2") (pinfunction "D2_S2") (pintype "passive"))
    )
    (net (code "199") (name "Net-(AB19A-P$2)") (class "Default")
      (node (ref "A18") (pin "D2") (pinfunction "D2_D2") (pintype "input"))
      (node (ref "A18") (pin "J2") (pinfunction "J2_J2") (pintype "output"))
      (node (ref "AB19") (pin "AF2") (pinfunction "P$2_AF2") (pintype "bidirectional"))
    )
    (net (code "200") (name "Net-(AB19B-P$2)") (class "Default")
      (node (ref "A18") (pin "E2") (pinfunction "E2_E2") (pintype "input"))
      (node (ref "A18") (pin "K2") (pinfunction "K2_K2") (pintype "output"))
      (node (ref "AB19") (pin "AH2") (pinfunction "P$2_AH2") (pintype "bidirectional"))
    )
    (net (code "201") (name "Net-(AB19D-P$2)") (class "Default")
      (node (ref "AB19") (pin "AN2") (pinfunction "P$2_AN2") (pintype "bidirectional"))
      (node (ref "B18") (pin "D2") (pinfunction "D2_D2") (pintype "input"))
      (node (ref "B18") (pin "J2") (pinfunction "J2_J2") (pintype "output"))
    )
    (net (code "202") (name "Net-(AB19E-P$2)") (class "Default")
      (node (ref "AB19") (pin "AP2") (pinfunction "P$2_AP2") (pintype "bidirectional"))
      (node (ref "B18") (pin "E2") (pinfunction "E2_E2") (pintype "input"))
      (node (ref "B18") (pin "K2") (pinfunction "K2_K2") (pintype "output"))
    )
    (net (code "203") (name "Net-(AB19H-P$2)") (class "Default")
      (node (ref "A20") (pin "D2") (pinfunction "D2_D2") (pintype "input"))
      (node (ref "A20") (pin "J2") (pinfunction "J2_J2") (pintype "output"))
      (node (ref "AB19") (pin "AV2") (pinfunction "P$2_AV2") (pintype "bidirectional"))
    )
    (net (code "204") (name "Net-(AB19I-P$2)") (class "Default")
      (node (ref "A20") (pin "E2") (pinfunction "E2_E2") (pintype "input"))
      (node (ref "A20") (pin "K2") (pinfunction "K2_K2") (pintype "output"))
      (node (ref "AB19") (pin "BD2") (pinfunction "P$2_BD2") (pintype "bidirectional"))
    )
    (net (code "205") (name "Net-(AB19K-P$2)") (class "Default")
      (node (ref "AB19") (pin "BH2") (pinfunction "P$2_BH2") (pintype "bidirectional"))
      (node (ref "B20") (pin "D2") (pinfunction "D2_D2") (pintype "input"))
      (node (ref "B20") (pin "J2") (pinfunction "J2_J2") (pintype "output"))
    )
    (net (code "206") (name "Net-(AB19L-P$2)") (class "Default")
      (node (ref "AB19") (pin "BJ2") (pinfunction "P$2_BJ2") (pintype "bidirectional"))
      (node (ref "B20") (pin "E2") (pinfunction "E2_E2") (pintype "input"))
      (node (ref "B20") (pin "K2") (pinfunction "K2_K2") (pintype "output"))
    )
    (net (code "207") (name "Net-(AB19N-P$2)") (class "Default")
      (node (ref "A21") (pin "D2") (pinfunction "D2_D2") (pintype "input"))
      (node (ref "A21") (pin "J2") (pinfunction "J2_J2") (pintype "output"))
      (node (ref "AB19") (pin "BN2") (pinfunction "P$2_BN2") (pintype "bidirectional"))
    )
    (net (code "208") (name "Net-(AB19O-P$2)") (class "Default")
      (node (ref "A21") (pin "E2") (pinfunction "E2_E2") (pintype "input"))
      (node (ref "A21") (pin "K2") (pinfunction "K2_K2") (pintype "output"))
      (node (ref "AB19") (pin "BP2") (pinfunction "P$2_BP2") (pintype "bidirectional"))
    )
    (net (code "209") (name "Net-(B06P-IN)") (class "Default")
      (node (ref "B06") (pin "S2") (pinfunction "IN_S2") (pintype "input"))
      (node (ref "B08") (pin "S2") (pinfunction "OUT_S2") (pintype "output"))
    )
    (net (code "210") (name "Net-(B08A-OUT)") (class "Default")
      (node (ref "B08") (pin "C1") (pinfunction "OUT_C1") (pintype "output"))
      (node (ref "B09") (pin "D1") (pinfunction "S_D1") (pintype "input"))
    )
    (net (code "211") (name "Net-(B08B-OUT)") (class "Default")
      (node (ref "B08") (pin "F1") (pinfunction "OUT_F1") (pintype "output"))
      (node (ref "B09") (pin "U2") (pinfunction "S_U2") (pintype "input"))
    )
    (net (code "212") (name "Net-(B08C-OUT)") (class "Default")
      (node (ref "B08") (pin "F2") (pinfunction "OUT_F2") (pintype "output"))
      (node (ref "B09") (pin "K1") (pinfunction "S_K1") (pintype "input"))
    )
    (net (code "213") (name "Net-(B08F-OUT)") (class "Default")
      (node (ref "B08") (pin "K1") (pinfunction "OUT_K1") (pintype "output"))
      (node (ref "B09") (pin "F2") (pinfunction "S_F2") (pintype "input"))
    )
    (net (code "214") (name "Net-(B08H-OUT)") (class "Default")
      (node (ref "B08") (pin "N1") (pinfunction "OUT_N1") (pintype "output"))
      (node (ref "B09") (pin "N2") (pinfunction "S_N2") (pintype "input"))
    )
    (net (code "215") (name "Net-(B08J-OUT)") (class "Default")
      (node (ref "B08") (pin "S1") (pinfunction "OUT_S1") (pintype "output"))
      (node (ref "B09") (pin "R1") (pinfunction "S_R1") (pintype "input"))
    )
    (net (code "216") (name "Net-(B10E-IN1)") (class "Default")
      (node (ref "B10") (pin "F1") (pinfunction "IN1_F1") (pintype "input"))
      (node (ref "B11") (pin "J1") (pinfunction "OUT_J1") (pintype "output"))
    )
    (net (code "217") (name "Net-(B10E-IN4)") (class "Default")
      (node (ref "B10") (pin "K1") (pinfunction "IN4_K1") (pintype "input"))
      (node (ref "C17") (pin "H1") (pinfunction "OUT_H1") (pintype "output"))
    )
    (net (code "218") (name "Net-(B11A-OUT)") (class "Default")
      (node (ref "B11") (pin "D1") (pinfunction "OUT_D1") (pintype "output"))
      (node (ref "B11") (pin "F2") (pinfunction "IN3_F2") (pintype "input"))
    )
    (net (code "219") (name "Net-(B11D-IN1)") (class "Default")
      (node (ref "B11") (pin "D2") (pinfunction "IN1_D2") (pintype "input"))
      (node (ref "B12") (pin "E1") (pinfunction "OUT_E1") (pintype "output"))
    )
    (net (code "220") (name "Net-(B11D-IN2)") (class "Default")
      (node (ref "B11") (pin "E2") (pinfunction "IN2_E2") (pintype "input"))
      (node (ref "B12") (pin "L1") (pinfunction "OUT_L1") (pintype "output"))
    )
    (net (code "221") (name "Net-(B11D-OUT)") (class "Default")
      (node (ref "B11") (pin "H2") (pinfunction "OUT_H2") (pintype "output"))
      (node (ref "C13") (pin "C1") (pinfunction "IN_C1") (pintype "input"))
    )
    (net (code "222") (name "Net-(B11E-IN1)") (class "Default")
      (node (ref "B11") (pin "E1") (pinfunction "IN1_E1") (pintype "input"))
      (node (ref "B11") (pin "U1") (pinfunction "OUT_U1") (pintype "output"))
    )
    (net (code "223") (name "Net-(B11E-IN3)") (class "Default")
      (node (ref "B11") (pin "H1") (pinfunction "IN3_H1") (pintype "input"))
      (node (ref "B11") (pin "N1") (pinfunction "OUT_N1") (pintype "output"))
    )
    (net (code "224") (name "Net-(B11F-IN3)") (class "Default")
      (node (ref "B11") (pin "L2") (pinfunction "IN3_L2") (pintype "input"))
      (node (ref "B15") (pin "S2") (pinfunction "OUT_S2") (pintype "output"))
    )
    (net (code "225") (name "Net-(B11J-OUT)") (class "Default")
      (node (ref "B11") (pin "V1") (pinfunction "OUT_V1") (pintype "output"))
      (node (ref "C17") (pin "J1") (pinfunction "IN_J1") (pintype "input"))
    )
    (net (code "226") (name "Net-(B12D-OUT)") (class "Default")
      (node (ref "B12") (pin "J2") (pinfunction "OUT_J2") (pintype "output"))
      (node (ref "B12") (pin "N2") (pinfunction "IN4_N2") (pintype "input"))
    )
    (net (code "227") (name "Net-(B12F-IN1)") (class "Default")
      (node (ref "B12") (pin "K2") (pinfunction "IN1_K2") (pintype "input"))
      (node (ref "C12") (pin "N1") (pinfunction "OUT_N1") (pintype "output"))
    )
    (net (code "228") (name "Net-(B12F-IN2)") (class "Default")
      (node (ref "B12") (pin "L2") (pinfunction "IN2_L2") (pintype "input"))
      (node (ref "C12") (pin "U1") (pinfunction "OUT_U1") (pintype "output"))
    )
    (net (code "229") (name "Net-(B12F-IN3)") (class "Default")
      (node (ref "B12") (pin "M2") (pinfunction "IN3_M2") (pintype "input"))
      (node (ref "C12") (pin "V1") (pinfunction "OUT_V1") (pintype "output"))
    )
    (net (code "230") (name "Net-(B12G-IN1)") (class "Default")
      (node (ref "B12") (pin "M1") (pinfunction "IN1_M1") (pintype "input"))
      (node (ref "C11") (pin "C1") (pinfunction "OUT_C1") (pintype "output"))
    )
    (net (code "231") (name "Net-(B12G-IN4)") (class "Default")
      (node (ref "B12") (pin "R1") (pinfunction "IN4_R1") (pintype "input"))
      (node (ref "C11") (pin "F1") (pinfunction "OUT_F1") (pintype "output"))
    )
    (net (code "232") (name "Net-(B12G-OUT)") (class "Default")
      (node (ref "B12") (pin "S1") (pinfunction "OUT_S1") (pintype "output"))
      (node (ref "C11") (pin "P1") (pinfunction "IN1_P1") (pintype "input"))
    )
    (net (code "233") (name "Net-(B12J-IN4)") (class "Default")
      (node (ref "B12") (pin "U2") (pinfunction "IN4_U2") (pintype "input"))
      (node (ref "C11") (pin "N1") (pinfunction "OUT_N1") (pintype "output"))
    )
    (net (code "234") (name "Net-(B12J-OUT)") (class "Default")
      (node (ref "B12") (pin "V2") (pinfunction "OUT_V2") (pintype "output"))
      (node (ref "C12") (pin "F1") (pinfunction "IN2_F1") (pintype "input"))
    )
    (net (code "235") (name "Net-(B13F-S)") (class "Default")
      (node (ref "B13") (pin "N2") (pinfunction "S_N2") (pintype "input"))
      (node (ref "B15") (pin "K1") (pinfunction "OUT_K1") (pintype "output"))
    )
    (net (code "236") (name "Net-(B14G-C)") (class "Default")
      (node (ref "B14") (pin "N1") (pinfunction "C_N1") (pintype "input"))
      (node (ref "B14") (pin "S2") (pinfunction "C_S2") (pintype "input"))
      (node (ref "D15") (pin "D2") (pinfunction "D2_D2") (pintype "output"))
    )
    (net (code "237") (name "Net-(B15B-OUT)") (class "Default")
      (node (ref "A14") (pin "H2") (pinfunction "H2_H2") (pintype "input"))
      (node (ref "A14") (pin "J2") (pinfunction "J2_J2") (pintype "input"))
      (node (ref "A14") (pin "K2") (pinfunction "K2_K2") (pintype "input"))
      (node (ref "B15") (pin "F1") (pinfunction "OUT_F1") (pintype "output"))
    )
    (net (code "238") (name "Net-(B15H-OUT)") (class "Default")
      (node (ref "B15") (pin "N1") (pinfunction "OUT_N1") (pintype "output"))
      (node (ref "C17") (pin "F1") (pinfunction "IN_F1") (pintype "input"))
    )
    (net (code "239") (name "Net-(B15J-OUT)") (class "Default")
      (node (ref "B15") (pin "S1") (pinfunction "OUT_S1") (pintype "output"))
      (node (ref "C17") (pin "L1") (pinfunction "IN_L1") (pintype "input"))
    )
    (net (code "240") (name "Net-(B16-PadD2)") (class "Default")
      (node (ref "B16") (pin "D2") (pinfunction "D2_D2") (pintype "passive"))
      (node (ref "B16") (pin "E2") (pinfunction "E2_E2") (pintype "passive"))
    )
    (net (code "241") (name "Net-(B16C-D2)") (class "Default")
      (node (ref "B16") (pin "R2") (pinfunction "E2_R2") (pintype "passive"))
      (node (ref "B16") (pin "S2") (pinfunction "D2_S2") (pintype "passive"))
    )
    (net (code "242") (name "Net-(C08A-OUT)") (class "Default")
      (node (ref "C08") (pin "E1") (pinfunction "OUT_E1") (pintype "output"))
      (node (ref "C09") (pin "D1") (pinfunction "S_D1") (pintype "input"))
    )
    (net (code "243") (name "Net-(C08D-OUT)") (class "Default")
      (node (ref "C08") (pin "J2") (pinfunction "OUT_J2") (pintype "output"))
      (node (ref "C09") (pin "N2") (pinfunction "S_N2") (pintype "input"))
    )
    (net (code "244") (name "Net-(C08E-OUT)") (class "Default")
      (node (ref "C08") (pin "L1") (pinfunction "OUT_L1") (pintype "output"))
      (node (ref "C09") (pin "F2") (pinfunction "S_F2") (pintype "input"))
    )
    (net (code "245") (name "Net-(C08F-OUT)") (class "Default")
      (node (ref "C08") (pin "P2") (pinfunction "OUT_P2") (pintype "output"))
      (node (ref "C09") (pin "R1") (pinfunction "S_R1") (pintype "input"))
    )
    (net (code "246") (name "Net-(C08G-OUT)") (class "Default")
      (node (ref "C08") (pin "S1") (pinfunction "OUT_S1") (pintype "output"))
      (node (ref "C09") (pin "K1") (pinfunction "S_K1") (pintype "input"))
    )
    (net (code "247") (name "Net-(C08J-OUT)") (class "Default")
      (node (ref "C08") (pin "V2") (pinfunction "OUT_V2") (pintype "output"))
      (node (ref "C09") (pin "U2") (pinfunction "S_U2") (pintype "input"))
    )
    (net (code "248") (name "Net-(C10A-OUT)") (class "Default")
      (node (ref "C10") (pin "E1") (pinfunction "OUT_E1") (pintype "output"))
      (node (ref "C14") (pin "C1") (pinfunction "D_C1") (pintype "input"))
    )
    (net (code "249") (name "Net-(C10D-OUT)") (class "Default")
      (node (ref "C10") (pin "J2") (pinfunction "OUT_J2") (pintype "output"))
      (node (ref "C17") (pin "M2") (pinfunction "IN_M2") (pintype "input"))
    )
    (net (code "250") (name "Net-(C10E-OUT)") (class "Default")
      (node (ref "C10") (pin "L1") (pinfunction "OUT_L1") (pintype "output"))
      (node (ref "C14") (pin "E2") (pinfunction "D_E2") (pintype "input"))
    )
    (net (code "251") (name "Net-(C10G-OUT)") (class "Default")
      (node (ref "C10") (pin "S1") (pinfunction "OUT_S1") (pintype "output"))
      (node (ref "C14") (pin "J1") (pinfunction "D_J1") (pintype "input"))
    )
    (net (code "252") (name "Net-(C10J-OUT)") (class "Default")
      (node (ref "C10") (pin "V2") (pinfunction "OUT_V2") (pintype "output"))
      (node (ref "C17") (pin "V1") (pinfunction "IN_V1") (pintype "input"))
    )
    (net (code "253") (name "Net-(C11C-OUT)") (class "Default")
      (node (ref "C11") (pin "F2") (pinfunction "OUT_F2") (pintype "output"))
      (node (ref "C12") (pin "H1") (pinfunction "IN3_H1") (pintype "input"))
    )
    (net (code "254") (name "Net-(C11F-OUT)") (class "Default")
      (node (ref "C11") (pin "K1") (pinfunction "OUT_K1") (pintype "output"))
      (node (ref "C11") (pin "L1") (pinfunction "IN1_L1") (pintype "input"))
    )
    (net (code "255") (name "Net-(C11G-OUT)") (class "Default")
      (node (ref "C11") (pin "K2") (pinfunction "OUT_K2") (pintype "output"))
      (node (ref "D12") (pin "K2") (pinfunction "IN1_K2") (pintype "input"))
      (node (ref "D12") (pin "L2") (pinfunction "IN2_L2") (pintype "input"))
    )
    (net (code "256") (name "Net-(C11J-OUT)") (class "Default")
      (node (ref "C11") (pin "S1") (pinfunction "OUT_S1") (pintype "output"))
      (node (ref "C12") (pin "E1") (pinfunction "IN1_E1") (pintype "input"))
    )
    (net (code "257") (name "Net-(C11K-OUT)") (class "Default")
      (node (ref "C11") (pin "S2") (pinfunction "OUT_S2") (pintype "output"))
      (node (ref "C11") (pin "T2") (pinfunction "IN1_T2") (pintype "input"))
    )
    (net (code "258") (name "Net-(C11N-OUT)") (class "Default")
      (node (ref "C11") (pin "V2") (pinfunction "OUT_V2") (pintype "output"))
      (node (ref "C13") (pin "V1") (pinfunction "IN_V1") (pintype "input"))
    )
    (net (code "259") (name "Net-(C12A-OUT)") (class "Default")
      (node (ref "C12") (pin "D1") (pinfunction "OUT_D1") (pintype "output"))
      (node (ref "C13") (pin "M2") (pinfunction "IN_M2") (pintype "input"))
    )
    (net (code "260") (name "Net-(C12D-OUT)") (class "Default")
      (node (ref "C12") (pin "H2") (pinfunction "OUT_H2") (pintype "output"))
      (node (ref "D12") (pin "M2") (pinfunction "IN3_M2") (pintype "input"))
      (node (ref "D12") (pin "N2") (pinfunction "IN4_N2") (pintype "input"))
    )
    (net (code "261") (name "Net-(C12H-OUT)") (class "Default")
      (node (ref "C12") (pin "S2") (pinfunction "OUT_S2") (pintype "output"))
      (node (ref "C15") (pin "P1") (pinfunction "IN1_P1") (pintype "input"))
    )
    (net (code "262") (name "Net-(C13B-OUT)") (class "Default")
      (node (ref "C13") (pin "D2") (pinfunction "OUT_D2") (pintype "output"))
      (node (ref "C14") (pin "P1") (pinfunction "D_P1") (pintype "input"))
    )
    (net (code "263") (name "Net-(C13L-OUT)") (class "Default")
      (node (ref "C13") (pin "N2") (pinfunction "OUT_N2") (pintype "output"))
      (node (ref "C14") (pin "N2") (pinfunction "S_N2") (pintype "input"))
    )
    (net (code "264") (name "Net-(C13N-IN)") (class "Default")
      (node (ref "C13") (pin "P2") (pinfunction "IN_P2") (pintype "input"))
      (node (ref "C15") (pin "F2") (pinfunction "OUT_F2") (pintype "output"))
    )
    (net (code "265") (name "Net-(C13P-IN)") (class "Default")
      (node (ref "C13") (pin "S2") (pinfunction "IN_S2") (pintype "input"))
      (node (ref "C15") (pin "K2") (pinfunction "OUT_K2") (pintype "output"))
    )
    (net (code "266") (name "Net-(C14F-C)") (class "Default")
      (node (ref "C14") (pin "L2") (pinfunction "C_L2") (pintype "input"))
      (node (ref "C15") (pin "S2") (pinfunction "OUT_S2") (pintype "output"))
    )
    (net (code "267") (name "Net-(C15A-OUT)") (class "Default")
      (node (ref "C15") (pin "C1") (pinfunction "OUT_C1") (pintype "output"))
      (node (ref "C15") (pin "H1") (pinfunction "IN1_H1") (pintype "input"))
    )
    (net (code "268") (name "Net-(C15B-OUT)") (class "Default")
      (node (ref "C15") (pin "F1") (pinfunction "OUT_F1") (pintype "output"))
      (node (ref "C15") (pin "J1") (pinfunction "IN2_J1") (pintype "input"))
    )
    (net (code "269") (name "Net-(C15H-OUT)") (class "Default")
      (node (ref "C15") (pin "N1") (pinfunction "OUT_N1") (pintype "output"))
      (node (ref "C15") (pin "R1") (pinfunction "IN2_R1") (pintype "input"))
    )
    (net (code "270") (name "Net-(C15I-OUT)") (class "Default")
      (node (ref "C15") (pin "N2") (pinfunction "OUT_N2") (pintype "output"))
      (node (ref "C17") (pin "P2") (pinfunction "IN_P2") (pintype "input"))
    )
    (net (code "271") (name "Net-(C16F-IN1)") (class "Default")
      (node (ref "C16") (pin "K2") (pinfunction "IN1_K2") (pintype "input"))
      (node (ref "C16") (pin "L2") (pinfunction "IN2_L2") (pintype "input"))
      (node (ref "C16") (pin "M2") (pinfunction "IN3_M2") (pintype "input"))
      (node (ref "C16") (pin "N2") (pinfunction "IN4_N2") (pintype "input"))
      (node (ref "C17") (pin "B1") (pinfunction "OUT_B1") (pintype "output"))
    )
    (net (code "272") (name "Net-(C16G-OUT)") (class "Default")
      (node (ref "B16") (pin "K2") (pinfunction "K2_K2") (pintype "input"))
      (node (ref "C16") (pin "S1") (pinfunction "OUT_S1") (pintype "output"))
    )
    (net (code "273") (name "Net-(C16J-OUT)") (class "Default")
      (node (ref "A16") (pin "H2") (pinfunction "H2_H2") (pintype "input"))
      (node (ref "C16") (pin "V2") (pinfunction "OUT_V2") (pintype "output"))
    )
    (net (code "274") (name "Net-(C17B-IN)") (class "Default")
      (node (ref "A16") (pin "F2") (pinfunction "F2_F2") (pintype "output"))
      (node (ref "C17") (pin "C1") (pinfunction "IN_C1") (pintype "input"))
    )
    (net (code "275") (name "Net-(C17D-IN)") (class "Default")
      (node (ref "B16") (pin "F2") (pinfunction "F2_F2") (pintype "output"))
      (node (ref "C17") (pin "E2") (pinfunction "IN_E2") (pintype "input"))
    )
    (net (code "276") (name "Net-(C17L-OUT)") (class "Default")
      (node (ref "C17") (pin "N2") (pinfunction "OUT_N2") (pintype "output"))
      (node (ref "D08") (pin "B1") (pinfunction "B1_B1") (pintype "input"))
      (node (ref "D08") (pin "H1") (pinfunction "H1_H1") (pintype "input"))
      (node (ref "D08") (pin "N1") (pinfunction "N1_N1") (pintype "input"))
    )
    (net (code "277") (name "Net-(C17O-IN)") (class "Default")
      (node (ref "C17") (pin "R1") (pinfunction "IN_R1") (pintype "input"))
      (node (ref "D17") (pin "F2") (pinfunction "F2_F2") (pintype "output"))
    )
    (net (code "278") (name "Net-(C17P-IN)") (class "Default")
      (node (ref "C17") (pin "S2") (pinfunction "IN_S2") (pintype "input"))
      (node (ref "D16") (pin "T2") (pinfunction "F2_T2") (pintype "output"))
    )
    (net (code "279") (name "Net-(C17Q-OUT)") (class "Default")
      (node (ref "C17") (pin "U1") (pinfunction "OUT_U1") (pintype "output"))
      (node (ref "D08") (pin "D2") (pinfunction "D2_D2") (pintype "input"))
      (node (ref "D08") (pin "L2") (pinfunction "L2_L2") (pintype "input"))
      (node (ref "D08") (pin "S2") (pinfunction "S2_S2") (pintype "input"))
    )
    (net (code "280") (name "Net-(D09A-OUT)") (class "Default")
      (node (ref "D08") (pin "C1") (pinfunction "C1_C1") (pintype "input"))
      (node (ref "D08") (pin "D1") (pinfunction "D1_D1") (pintype "input"))
      (node (ref "D09") (pin "E1") (pinfunction "OUT_E1") (pintype "output"))
    )
    (net (code "281") (name "Net-(D09D-OUT)") (class "Default")
      (node (ref "D08") (pin "E2") (pinfunction "E2_E2") (pintype "input"))
      (node (ref "D08") (pin "F2") (pinfunction "F2_F2") (pintype "input"))
      (node (ref "D09") (pin "J2") (pinfunction "OUT_J2") (pintype "output"))
    )
    (net (code "282") (name "Net-(D09E-OUT)") (class "Default")
      (node (ref "D08") (pin "J1") (pinfunction "J1_J1") (pintype "input"))
      (node (ref "D08") (pin "K1") (pinfunction "K1_K1") (pintype "input"))
      (node (ref "D09") (pin "L1") (pinfunction "OUT_L1") (pintype "output"))
    )
    (net (code "283") (name "Net-(D09F-OUT)") (class "Default")
      (node (ref "D08") (pin "M2") (pinfunction "M2_M2") (pintype "input"))
      (node (ref "D08") (pin "N2") (pinfunction "N2_N2") (pintype "input"))
      (node (ref "D09") (pin "P2") (pinfunction "OUT_P2") (pintype "output"))
    )
    (net (code "284") (name "Net-(D09G-OUT)") (class "Default")
      (node (ref "D08") (pin "P1") (pinfunction "P1_P1") (pintype "input"))
      (node (ref "D08") (pin "R1") (pinfunction "R1_R1") (pintype "input"))
      (node (ref "D09") (pin "S1") (pinfunction "OUT_S1") (pintype "output"))
    )
    (net (code "285") (name "Net-(D09J-OUT)") (class "Default")
      (node (ref "D08") (pin "T2") (pinfunction "T2_T2") (pintype "input"))
      (node (ref "D08") (pin "U2") (pinfunction "U2_U2") (pintype "input"))
      (node (ref "D09") (pin "V2") (pinfunction "OUT_V2") (pintype "output"))
    )
    (net (code "286") (name "Net-(D10D-OUT)") (class "Default")
      (node (ref "D10") (pin "P2") (pinfunction "OUT_P2") (pintype "output"))
      (node (ref "D14") (pin "J2") (pinfunction "N1_J2") (pintype "input"))
    )
    (net (code "287") (name "Net-(D12A-IN1)") (class "Default")
      (node (ref "D12") (pin "A1") (pinfunction "IN1_A1") (pintype "input"))
      (node (ref "D12") (pin "B1") (pinfunction "IN2_B1") (pintype "input"))
      (node (ref "D12") (pin "C1") (pinfunction "IN3_C1") (pintype "input"))
      (node (ref "D12") (pin "D1") (pinfunction "IN4_D1") (pintype "input"))
      (node (ref "D13") (pin "F2") (pinfunction "F2_F2") (pintype "output"))
    )
    (net (code "288") (name "Net-(D13C-D2)") (class "Default")
      (node (ref "D13") (pin "R2") (pinfunction "E2_R2") (pintype "passive"))
      (node (ref "D13") (pin "S2") (pinfunction "D2_S2") (pintype "passive"))
    )
    (net (code "289") (name "Net-(D14-PadM2)") (class "Default")
      (node (ref "D14") (pin "M2") (pinfunction "M2_M2") (pintype "passive"))
      (node (ref "D14") (pin "V2") (pinfunction "V2_V2") (pintype "passive"))
    )
    (net (code "290") (name "Net-(D14-PadP1)") (class "Default")
      (node (ref "D14") (pin "P1") (pinfunction "P1_P1") (pintype "passive"))
      (node (ref "D14") (pin "V1") (pinfunction "V1_V1") (pintype "passive"))
    )
    (net (code "291") (name "Net-(D14E-M2)") (class "Default")
      (node (ref "D14") (pin "D2") (pinfunction "M2_D2") (pintype "passive"))
      (node (ref "D14") (pin "H1") (pinfunction "P2_H1") (pintype "passive"))
    )
    (net (code "292") (name "Net-(D14E-P1)") (class "Default")
      (node (ref "D14") (pin "A1") (pinfunction "V1_A1") (pintype "passive"))
      (node (ref "D14") (pin "C1") (pinfunction "P1_C1") (pintype "passive"))
    )
    (net (code "293") (name "Net-(D15-PadN2)") (class "Default")
      (node (ref "D15") (pin "N2") (pinfunction "N2_N2") (pintype "passive"))
      (node (ref "D15") (pin "S2") (pinfunction "S2_S2") (pintype "passive"))
    )
    (net (code "294") (name "Net-(D16D-D2)") (class "Default")
      (node (ref "D16") (pin "R2") (pinfunction "E2_R2") (pintype "passive"))
      (node (ref "D16") (pin "V2") (pinfunction "D2_V2") (pintype "passive"))
    )
    (net (code "295") (name "Net-(D16D-H1)") (class "Default")
      (node (ref "D16") (pin "S1") (pinfunction "H1_S1") (pintype "passive"))
      (node (ref "D16") (pin "S2") (pinfunction "L2_S2") (pintype "passive"))
    )
    (net (code "296") (name "Net-(D17-PadD2)") (class "Default")
      (node (ref "D17") (pin "D2") (pinfunction "D2_D2") (pintype "passive"))
      (node (ref "D17") (pin "E2") (pinfunction "E2_E2") (pintype "passive"))
    )
    (net (code "297") (name "Net-(D17C-D2)") (class "Default")
      (node (ref "D17") (pin "R2") (pinfunction "E2_R2") (pintype "passive"))
      (node (ref "D17") (pin "S2") (pinfunction "D2_S2") (pintype "passive"))
    )
    (net (code "298") (name "PAR") (class "Default")
      (node (ref "A08") (pin "U1") (pinfunction "0_U1") (pintype "output"))
      (node (ref "A25") (pin "T1") (pinfunction "P$2_T1") (pintype "bidirectional"))
    )
    (net (code "299") (name "PC+ES") (class "Default")
      (node (ref "A11") (pin "H2") (pinfunction "IN_H2") (pintype "input"))
      (node (ref "A12") (pin "C1") (pinfunction "OUT_C1") (pintype "output"))
    )
    (net (code "300") (name "PWR_CLR") (class "Default")
      (node (ref "C06") (pin "R2") (pinfunction "OUT_R2") (pintype "output"))
    )
    (net (code "301") (name "RD+WD") (class "Default")
      (node (ref "A09") (pin "P1") (pinfunction "IN3_P1") (pintype "input"))
      (node (ref "B08") (pin "N2") (pinfunction "OUT_N2") (pintype "output"))
      (node (ref "B12") (pin "D2") (pinfunction "IN1_D2") (pintype "input"))
      (node (ref "C12") (pin "R1") (pinfunction "IN2_R1") (pintype "input"))
    )
    (net (code "302") (name "RDD_00") (class "Default")
      (node (ref "A21") (pin "U2") (pinfunction "U2_U2") (pintype "output"))
      (node (ref "B09") (pin "M2") (pinfunction "D_M2") (pintype "input"))
      (node (ref "D09") (pin "C1") (pinfunction "IN2A_C1") (pintype "input"))
      (node (ref "D09") (pin "F2") (pinfunction "IN2A_F2") (pintype "input"))
    )
    (net (code "303") (name "RDD_01") (class "Default")
      (node (ref "B09") (pin "P1") (pinfunction "D_P1") (pintype "input"))
      (node (ref "B20") (pin "U2") (pinfunction "U2_U2") (pintype "output"))
      (node (ref "D09") (pin "J1") (pinfunction "IN2A_J1") (pintype "input"))
      (node (ref "D09") (pin "M2") (pinfunction "IN2A_M2") (pintype "input"))
    )
    (net (code "304") (name "RDD_02") (class "Default")
      (node (ref "A20") (pin "U2") (pinfunction "U2_U2") (pintype "output"))
      (node (ref "B09") (pin "E2") (pinfunction "D_E2") (pintype "input"))
      (node (ref "D09") (pin "P1") (pinfunction "IN2A_P1") (pintype "input"))
      (node (ref "D09") (pin "T2") (pinfunction "IN2A_T2") (pintype "input"))
    )
    (net (code "305") (name "RDMK") (class "Default")
      (node (ref "B18") (pin "U2") (pinfunction "U2_U2") (pintype "output"))
      (node (ref "CD18") (pin "AS2") (pinfunction "AS2_AS2") (pintype "input"))
    )
    (net (code "306") (name "RD_EN") (class "Default")
      (node (ref "C11") (pin "J1") (pinfunction "IN2_J1") (pintype "input"))
      (node (ref "C11") (pin "N2") (pinfunction "OUT_N2") (pintype "output"))
    )
    (net (code "307") (name "RD_EN_LPB_00-02") (class "Default")
      (node (ref "C10") (pin "D2") (pinfunction "IN1A_D2") (pintype "input"))
      (node (ref "C13") (pin "T2") (pinfunction "OUT_T2") (pintype "output"))
      (node (ref "D09") (pin "D1") (pinfunction "IN2B_D1") (pintype "input"))
      (node (ref "D09") (pin "K1") (pinfunction "IN2B_K1") (pintype "input"))
      (node (ref "D09") (pin "R1") (pinfunction "IN2B_R1") (pintype "input"))
    )
    (net (code "308") (name "RD_EN_LPB_03-05") (class "Default")
      (node (ref "C10") (pin "R2") (pinfunction "IN1A_R2") (pintype "input"))
      (node (ref "C13") (pin "R2") (pinfunction "OUT_R2") (pintype "output"))
      (node (ref "D09") (pin "H2") (pinfunction "IN2B_H2") (pintype "input"))
      (node (ref "D09") (pin "N2") (pinfunction "IN2B_N2") (pintype "input"))
      (node (ref "D09") (pin "U2") (pinfunction "IN2B_U2") (pintype "input"))
    )
    (net (code "309") (name "READ_ALL") (class "Default")
      (node (ref "D07") (pin "N2") (pinfunction "O3_N2") (pintype "output"))
    )
    (net (code "310") (name "READ_DATA") (class "Default")
      (node (ref "A10") (pin "L1") (pinfunction "IN1_L1") (pintype "input"))
      (node (ref "C11") (pin "H1") (pinfunction "IN1_H1") (pintype "input"))
      (node (ref "D07") (pin "J2") (pinfunction "O2_J2") (pintype "output"))
    )
    (net (code "311") (name "RSTA") (class "Default")
      (node (ref "C04") (pin "A1") (pinfunction "A1_A1") (pintype "output"))
    )
    (net (code "312") (name "RSTB") (class "Default")
      (node (ref "C05") (pin "C1") (pinfunction "C1_C1") (pintype "output"))
    )
    (net (code "313") (name "SE") (class "Default")
      (node (ref "D07") (pin "L2") (pinfunction "O7_L2") (pintype "output"))
    )
    (net (code "314") (name "SEARCH") (class "Default")
      (node (ref "C11") (pin "D2") (pinfunction "IN1_D2") (pintype "input"))
      (node (ref "D07") (pin "E2") (pinfunction "O1_E2") (pintype "output"))
    )
    (net (code "315") (name "SEL") (class "Default")
      (node (ref "A08") (pin "H2") (pinfunction "1_H2") (pintype "output"))
      (node (ref "A25") (pin "S1") (pinfunction "P$2_S1") (pintype "bidirectional"))
    )
    (net (code "316") (name "SHIFT_CK") (class "Default")
      (node (ref "C17") (pin "K1") (pinfunction "OUT_K1") (pintype "output"))
      (node (ref "CD18") (pin "BR2") (pinfunction "BR2_BR2") (pintype "input"))
    )
    (net (code "317") (name "SH_DTB") (class "Default")
      (node (ref "A10") (pin "R2") (pinfunction "IN2_R2") (pintype "input"))
      (node (ref "B09") (pin "B1") (pinfunction "C_B1") (pintype "input"))
      (node (ref "B09") (pin "D2") (pinfunction "C_D2") (pintype "input"))
      (node (ref "B09") (pin "H1") (pinfunction "C_H1") (pintype "input"))
      (node (ref "B09") (pin "L2") (pinfunction "C_L2") (pintype "input"))
      (node (ref "B09") (pin "N1") (pinfunction "C_N1") (pintype "input"))
      (node (ref "B09") (pin "S2") (pinfunction "C_S2") (pintype "input"))
      (node (ref "B10") (pin "E1") (pinfunction "OUT_E1") (pintype "output"))
      (node (ref "C09") (pin "B1") (pinfunction "C_B1") (pintype "input"))
      (node (ref "C09") (pin "D2") (pinfunction "C_D2") (pintype "input"))
      (node (ref "C09") (pin "H1") (pinfunction "C_H1") (pintype "input"))
      (node (ref "C09") (pin "L2") (pinfunction "C_L2") (pintype "input"))
      (node (ref "C09") (pin "N1") (pinfunction "C_N1") (pintype "input"))
      (node (ref "C09") (pin "S2") (pinfunction "C_S2") (pintype "input"))
    )
    (net (code "318") (name "SH_EN") (class "Default")
      (node (ref "A11") (pin "N2") (pinfunction "OUT_N2") (pintype "output"))
      (node (ref "A12") (pin "E2") (pinfunction "IN2_E2") (pintype "input"))
      (node (ref "C10") (pin "A1") (pinfunction "IN1A_A1") (pintype "input"))
      (node (ref "C10") (pin "F1") (pinfunction "IN1A_F1") (pintype "input"))
      (node (ref "C10") (pin "M1") (pinfunction "IN1A_M1") (pintype "input"))
    )
    (net (code "319") (name "SH_ST") (class "Default")
      (node (ref "C17") (pin "A1") (pinfunction "IN_A1") (pintype "input"))
      (node (ref "CD18") (pin "AM1") (pinfunction "AM1_AM1") (pintype "output"))
    )
    (net (code "320") (name "SH_ST-B") (class "Default")
      (node (ref "C16") (pin "P2") (pinfunction "OUT_P2") (pintype "output"))
      (node (ref "CD18") (pin "BC1") (pinfunction "BC1_BC1") (pintype "input"))
    )
    (net (code "321") (name "SINGLE_UNIT") (class "Default")
      (node (ref "A09") (pin "K1") (pinfunction "IN4_K1") (pintype "input"))
      (node (ref "B21") (pin "U2") (pinfunction "OUT_U2") (pintype "output"))
    )
    (net (code "322") (name "SP_DY") (class "Default")
      (node (ref "D14") (pin "H2") (pinfunction "H2_H2") (pintype "output"))
    )
    (net (code "323") (name "ST_BLK_MK") (class "Default")
      (node (ref "A26") (pin "K1") (pinfunction "P$2_K1") (pintype "bidirectional"))
      (node (ref "C13") (pin "E2") (pinfunction "IN_E2") (pintype "input"))
      (node (ref "CD18") (pin "AR2") (pinfunction "AR2_AR2") (pintype "output"))
    )
    (net (code "324") (name "ST_CK") (class "Default")
      (node (ref "A10") (pin "P1") (pinfunction "IN1_P1") (pintype "input"))
      (node (ref "A26") (pin "P1") (pinfunction "P$2_P1") (pintype "bidirectional"))
      (node (ref "C13") (pin "J1") (pinfunction "IN_J1") (pintype "input"))
      (node (ref "CD18") (pin "BR1") (pinfunction "BR1_BR1") (pintype "output"))
      (node (ref "D17") (pin "M2") (pinfunction "K2_M2") (pintype "input"))
      (node (ref "D17") (pin "N2") (pinfunction "J2_N2") (pintype "input"))
      (node (ref "D17") (pin "P2") (pinfunction "H2_P2") (pintype "input"))
    )
    (net (code "325") (name "ST_CK_0P") (class "Default")
      (node (ref "B12") (pin "H2") (pinfunction "IN4_H2") (pintype "input"))
      (node (ref "C12") (pin "S1") (pinfunction "IN3_S1") (pintype "input"))
      (node (ref "C13") (pin "B1") (pinfunction "OUT_B1") (pintype "output"))
    )
    (net (code "326") (name "ST_DATA") (class "Default")
      (node (ref "B12") (pin "A1") (pinfunction "IN1_A1") (pintype "input"))
      (node (ref "C13") (pin "H2") (pinfunction "IN_H2") (pintype "input"))
      (node (ref "C16") (pin "J2") (pinfunction "OUT_J2") (pintype "output"))
    )
    (net (code "327") (name "ST_FINAL") (class "Default")
      (node (ref "A09") (pin "S2") (pinfunction "IN2_S2") (pintype "input"))
      (node (ref "A26") (pin "N1") (pinfunction "P$2_N1") (pintype "bidirectional"))
      (node (ref "C11") (pin "D1") (pinfunction "IN1_D1") (pintype "input"))
      (node (ref "C13") (pin "L1") (pinfunction "IN_L1") (pintype "input"))
      (node (ref "CD18") (pin "BL2") (pinfunction "BL2_BL2") (pintype "output"))
    )
    (net (code "328") (name "ST_IDLE") (class "Default")
      (node (ref "A26") (pin "R1") (pinfunction "P$2_R1") (pintype "bidirectional"))
      (node (ref "C13") (pin "K2") (pinfunction "IN_K2") (pintype "input"))
      (node (ref "CD18") (pin "BD2") (pinfunction "BD2_BD2") (pintype "input"))
    )
    (net (code "329") (name "ST_REV_CK") (class "Default")
      (node (ref "A26") (pin "L1") (pinfunction "P$2_L1") (pintype "bidirectional"))
      (node (ref "B11") (pin "S1") (pinfunction "IN3_S1") (pintype "input"))
      (node (ref "C11") (pin "A1") (pinfunction "IN1_A1") (pintype "input"))
      (node (ref "C13") (pin "D1") (pinfunction "IN_D1") (pintype "input"))
      (node (ref "CD18") (pin "BS1") (pinfunction "BS1_BS1") (pintype "output"))
      (node (ref "D12") (pin "F2") (pinfunction "IN3_F2") (pintype "input"))
      (node (ref "D12") (pin "H2") (pinfunction "IN4_H2") (pintype "input"))
    )
    (net (code "330") (name "SWTM") (class "Default")
      (node (ref "A26") (pin "V2") (pinfunction "P$2_V2") (pintype "bidirectional"))
      (node (ref "B06") (pin "P2") (pinfunction "IN_P2") (pintype "input"))
      (node (ref "B08") (pin "V1") (pinfunction "P$1_V1") (pintype "passive"))
      (node (ref "B11") (pin "B1") (pinfunction "IN2_B1") (pintype "input"))
      (node (ref "C10") (pin "N2") (pinfunction "IN2B_N2") (pintype "input"))
      (node (ref "C12") (pin "P2") (pinfunction "IN2_P2") (pintype "input"))
      (node (ref "C15") (pin "L1") (pinfunction "IN1_L1") (pintype "input"))
    )
    (net (code "331") (name "SYNC") (class "Default")
      (node (ref "B10") (pin "D2") (pinfunction "IN1_D2") (pintype "input"))
      (node (ref "B10") (pin "E2") (pinfunction "IN2_E2") (pintype "input"))
      (node (ref "CD18") (pin "BN2") (pinfunction "BN2_BN2") (pintype "output"))
    )
    (net (code "332") (name "SYNC_EN") (class "Default")
      (node (ref "B11") (pin "M2") (pinfunction "OUT_M2") (pintype "output"))
      (node (ref "CD18") (pin "BH1") (pinfunction "BH1_BH1") (pintype "input"))
    )
    (net (code "333") (name "T3") (class "Default")
      (node (ref "C17") (pin "S1") (pinfunction "OUT_S1") (pintype "output"))
      (node (ref "D12") (pin "N1") (pinfunction "IN2_N1") (pintype "input"))
      (node (ref "D12") (pin "P1") (pinfunction "IN3_P1") (pintype "input"))
    )
    (net (code "334") (name "TIM") (class "Default")
      (node (ref "A08") (pin "L1") (pinfunction "1_L1") (pintype "output"))
      (node (ref "A25") (pin "U1") (pinfunction "P$2_U1") (pintype "bidirectional"))
    )
    (net (code "335") (name "TM_EN") (class "Default")
      (node (ref "A18") (pin "R2") (pinfunction "R2_R2") (pintype "input"))
      (node (ref "B18") (pin "R2") (pinfunction "R2_R2") (pintype "input"))
      (node (ref "C13") (pin "N1") (pinfunction "IN_N1") (pintype "input"))
      (node (ref "C15") (pin "S1") (pinfunction "OUT_S1") (pintype "output"))
      (node (ref "C16") (pin "M1") (pinfunction "IN1_M1") (pintype "input"))
      (node (ref "C16") (pin "R2") (pinfunction "IN1_R2") (pintype "input"))
    )
    (net (code "336") (name "TP00") (class "Default")
      (node (ref "A08") (pin "B1") (pinfunction "C_B1") (pintype "input"))
      (node (ref "A15") (pin "L1") (pinfunction "OUT_L1") (pintype "output"))
      (node (ref "A16") (pin "M2") (pinfunction "K2_M2") (pintype "input"))
      (node (ref "A16") (pin "N2") (pinfunction "J2_N2") (pintype "input"))
      (node (ref "A16") (pin "P2") (pinfunction "H2_P2") (pintype "input"))
      (node (ref "B10") (pin "F2") (pinfunction "IN3_F2") (pintype "input"))
      (node (ref "B10") (pin "H2") (pinfunction "IN4_H2") (pintype "input"))
      (node (ref "B10") (pin "N1") (pinfunction "IN2_N1") (pintype "input"))
      (node (ref "B13") (pin "B1") (pinfunction "C_B1") (pintype "input"))
      (node (ref "B13") (pin "D2") (pinfunction "C_D2") (pintype "input"))
      (node (ref "B13") (pin "H1") (pinfunction "C_H1") (pintype "input"))
      (node (ref "B15") (pin "J1") (pinfunction "IN2_J1") (pintype "input"))
      (node (ref "C15") (pin "E1") (pinfunction "IN2_E1") (pintype "input"))
    )
    (net (code "337") (name "TP00_A") (class "Default")
      (node (ref "A15") (pin "S1") (pinfunction "OUT_S1") (pintype "output"))
      (node (ref "B10") (pin "H1") (pinfunction "IN2_H1") (pintype "input"))
      (node (ref "C12") (pin "E2") (pinfunction "IN2_E2") (pintype "input"))
    )
    (net (code "338") (name "TP01") (class "Default")
      (node (ref "A12") (pin "J2") (pinfunction "IN2_J2") (pintype "input"))
      (node (ref "A15") (pin "P2") (pinfunction "OUT_P2") (pintype "output"))
      (node (ref "B16") (pin "M2") (pinfunction "K2_M2") (pintype "input"))
      (node (ref "B16") (pin "N2") (pinfunction "J2_N2") (pintype "input"))
      (node (ref "B16") (pin "P2") (pinfunction "H2_P2") (pintype "input"))
      (node (ref "C11") (pin "J2") (pinfunction "IN2_J2") (pintype "input"))
      (node (ref "C15") (pin "B1") (pinfunction "IN2_B1") (pintype "input"))
      (node (ref "CD18") (pin "BF1") (pinfunction "BF1_BF1") (pintype "input"))
    )
    (net (code "339") (name "TP01_A") (class "Default")
      (node (ref "A15") (pin "V2") (pinfunction "OUT_V2") (pintype "output"))
      (node (ref "B12") (pin "T2") (pinfunction "IN3_T2") (pintype "input"))
      (node (ref "C15") (pin "M2") (pinfunction "IN2_M2") (pintype "input"))
    )
    (net (code "340") (name "T_TRK") (class "Default")
      (node (ref "A18") (pin "U2") (pinfunction "U2_U2") (pintype "output"))
      (node (ref "B15") (pin "E2") (pinfunction "IN2_E2") (pintype "input"))
      (node (ref "C15") (pin "R2") (pinfunction "IN2_R2") (pintype "input"))
      (node (ref "D14") (pin "S1") (pinfunction "S1_S1") (pintype "input"))
      (node (ref "D14") (pin "U1") (pinfunction "U1_U1") (pintype "input"))
    )
    (net (code "341") (name "U+M_DY") (class "Default")
      (node (ref "D14") (pin "K1") (pinfunction "H2_K1") (pintype "output"))
    )
    (net (code "342") (name "USR_00") (class "Default")
      (node (ref "A07") (pin "V2") (pinfunction "IN2_V2") (pintype "input"))
      (node (ref "A25") (pin "A1") (pinfunction "P$2_A1") (pintype "bidirectional"))
      (node (ref "B07") (pin "E1") (pinfunction "E1_E1") (pintype "output"))
    )
    (net (code "343") (name "USR_01") (class "Default")
      (node (ref "A07") (pin "U2") (pinfunction "IN1_U2") (pintype "input"))
      (node (ref "A25") (pin "B1") (pinfunction "P$2_B1") (pintype "bidirectional"))
      (node (ref "B07") (pin "H2") (pinfunction "H2_H2") (pintype "output"))
    )
    (net (code "344") (name "USR_02") (class "Default")
      (node (ref "A07") (pin "V1") (pinfunction "IN0_V1") (pintype "input"))
      (node (ref "A25") (pin "C1") (pinfunction "P$2_C1") (pintype "bidirectional"))
      (node (ref "B07") (pin "L1") (pinfunction "L1_L1") (pintype "output"))
    )
    (net (code "345") (name "UTS") (class "Default")
      (node (ref "A10") (pin "E1") (pinfunction "IN2_E1") (pintype "input"))
      (node (ref "A26") (pin "J1") (pinfunction "P$2_J1") (pintype "bidirectional"))
      (node (ref "B15") (pin "P1") (pinfunction "IN1_P1") (pintype "input"))
      (node (ref "C14") (pin "R2") (pinfunction "0_R2") (pintype "output"))
    )
    (net (code "346") (name "VCC") (class "Default")
      (node (ref "AB01") (pin "AA2") (pinfunction "VCC_AA2") (pintype "power_in"))
      (node (ref "AB01") (pin "AB1") (pinfunction "VCC_AB1") (pintype "power_in"))
      (node (ref "AB01") (pin "AC1") (pinfunction "VCC_AC1") (pintype "power_in"))
      (node (ref "AB01") (pin "AD1") (pinfunction "VCC_AD1") (pintype "power_in"))
      (node (ref "AB01") (pin "AE1") (pinfunction "VCC_AE1") (pintype "power_in"))
      (node (ref "AB01") (pin "AF1") (pinfunction "VCC_AF1") (pintype "power_in"))
      (node (ref "AB01") (pin "AH1") (pinfunction "VCC_AH1") (pintype "power_in"))
      (node (ref "AB01") (pin "AJ1") (pinfunction "VCC_AJ1") (pintype "power_in"))
      (node (ref "AB01") (pin "AK1") (pinfunction "VCC_AK1") (pintype "power_in"))
      (node (ref "AB01") (pin "AL1") (pinfunction "VCC_AL1") (pintype "power_in"))
      (node (ref "AB01") (pin "BA2") (pinfunction "VCC_BA2") (pintype "power_in"))
      (node (ref "AB01") (pin "BB1") (pinfunction "VCC_BB1") (pintype "power_in"))
      (node (ref "AB01") (pin "BC1") (pinfunction "VCC_BC1") (pintype "power_in"))
      (node (ref "AB01") (pin "BD1") (pinfunction "VCC_BD1") (pintype "power_in"))
      (node (ref "AB01") (pin "BE1") (pinfunction "VCC_BE1") (pintype "power_in"))
    )
    (net (code "347") (name "W+UTS") (class "Default")
      (node (ref "A15") (pin "A1") (pinfunction "IN1_A1") (pintype "input"))
      (node (ref "A15") (pin "H2") (pinfunction "IN4_H2") (pintype "input"))
      (node (ref "C12") (pin "M2") (pinfunction "OUT_M2") (pintype "output"))
    )
    (net (code "348") (name "W-INH") (class "Default")
      (node (ref "A08") (pin "V1") (pinfunction "0_V1") (pintype "output"))
    )
    (net (code "349") (name "W01") (class "Default")
      (node (ref "A26") (pin "J2") (pinfunction "P$2_J2") (pintype "bidirectional"))
      (node (ref "CD18") (pin "BJ2") (pinfunction "BJ2_BJ2") (pintype "output"))
    )
    (net (code "350") (name "W01-W05") (class "Default")
      (node (ref "CD18") (pin "AK1") (pinfunction "AK1_AK1") (pintype "output"))
    )
    (net (code "351") (name "W02") (class "Default")
      (node (ref "A26") (pin "K2") (pinfunction "P$2_K2") (pintype "bidirectional"))
      (node (ref "CD18") (pin "BV2") (pinfunction "BV2_BV2") (pintype "output"))
    )
    (net (code "352") (name "W03") (class "Default")
      (node (ref "A26") (pin "L2") (pinfunction "P$2_L2") (pintype "bidirectional"))
      (node (ref "CD18") (pin "BE2") (pinfunction "BE2_BE2") (pintype "output"))
    )
    (net (code "353") (name "W04") (class "Default")
      (node (ref "A26") (pin "M2") (pinfunction "P$2_M2") (pintype "bidirectional"))
      (node (ref "CD18") (pin "AT2") (pinfunction "AT2_AT2") (pintype "output"))
    )
    (net (code "354") (name "W05") (class "Default")
      (node (ref "A26") (pin "N2") (pinfunction "P$2_N2") (pintype "bidirectional"))
      (node (ref "CD18") (pin "BU2") (pinfunction "BU2_BU2") (pintype "output"))
    )
    (net (code "355") (name "W06") (class "Default")
      (node (ref "A26") (pin "P2") (pinfunction "P$2_P2") (pintype "bidirectional"))
      (node (ref "CD18") (pin "AM2") (pinfunction "AM2_AM2") (pintype "output"))
    )
    (net (code "356") (name "W07") (class "Default")
      (node (ref "A26") (pin "R2") (pinfunction "P$2_R2") (pintype "bidirectional"))
      (node (ref "CD18") (pin "AK2") (pinfunction "AK2_AK2") (pintype "output"))
    )
    (net (code "357") (name "W08") (class "Default")
      (node (ref "A26") (pin "S2") (pinfunction "P$2_S2") (pintype "bidirectional"))
      (node (ref "CD18") (pin "AL1") (pinfunction "AL1_AL1") (pintype "output"))
    )
    (net (code "358") (name "W09") (class "Default")
      (node (ref "A26") (pin "T2") (pinfunction "P$2_T2") (pintype "bidirectional"))
      (node (ref "CD18") (pin "BF2") (pinfunction "BF2_BF2") (pintype "output"))
    )
    (net (code "359") (name "WB00") (class "Default")
      (node (ref "A21") (pin "N2") (pinfunction "N2_N2") (pintype "input"))
      (node (ref "A25") (pin "P2") (pinfunction "P$2_P2") (pintype "bidirectional"))
      (node (ref "B18") (pin "N2") (pinfunction "N2_N2") (pintype "input"))
      (node (ref "C14") (pin "F1") (pinfunction "0_F1") (pintype "output"))
      (node (ref "D09") (pin "A1") (pinfunction "IN1A_A1") (pintype "input"))
    )
    (net (code "360") (name "WB01") (class "Default")
      (node (ref "A25") (pin "R2") (pinfunction "P$2_R2") (pintype "bidirectional"))
      (node (ref "B20") (pin "N2") (pinfunction "N2_N2") (pintype "input"))
      (node (ref "C14") (pin "J2") (pinfunction "0_J2") (pintype "output"))
      (node (ref "D09") (pin "F1") (pinfunction "IN1A_F1") (pintype "input"))
    )
    (net (code "361") (name "WB02") (class "Default")
      (node (ref "A20") (pin "N2") (pinfunction "N2_N2") (pintype "input"))
      (node (ref "A25") (pin "S2") (pinfunction "P$2_S2") (pintype "bidirectional"))
      (node (ref "C14") (pin "M1") (pinfunction "0_M1") (pintype "output"))
      (node (ref "D09") (pin "M1") (pinfunction "IN1A_M1") (pintype "input"))
    )
    (net (code "362") (name "WC") (class "Default")
      (node (ref "A26") (pin "H1") (pinfunction "P$2_H1") (pintype "bidirectional"))
      (node (ref "B10") (pin "M1") (pinfunction "IN1_M1") (pintype "input"))
      (node (ref "B11") (pin "K1") (pinfunction "IN1_K1") (pintype "input"))
      (node (ref "D11") (pin "S1") (pinfunction "1_S1") (pintype "output"))
    )
    (net (code "363") (name "WC0") (class "Default")
      (node (ref "C01") (pin "H1") (pinfunction "OUT_H1") (pintype "output"))
      (node (ref "C06") (pin "M2") (pinfunction "IN_M2") (pintype "input"))
    )
    (net (code "364") (name "WRITE_ALL") (class "Default")
      (node (ref "A08") (pin "S2") (pinfunction "C_S2") (pintype "input"))
      (node (ref "B11") (pin "M1") (pinfunction "IN3_M1") (pintype "input"))
      (node (ref "B12") (pin "F1") (pinfunction "IN1_F1") (pintype "input"))
      (node (ref "D07") (pin "M2") (pinfunction "O5_M2") (pintype "output"))
    )
    (net (code "365") (name "WRITE_DATA") (class "Default")
      (node (ref "A09") (pin "R2") (pinfunction "IN1_R2") (pintype "input"))
      (node (ref "B11") (pin "R1") (pinfunction "IN2_R1") (pintype "input"))
      (node (ref "B12") (pin "B1") (pinfunction "IN2_B1") (pintype "input"))
      (node (ref "B12") (pin "P1") (pinfunction "IN3_P1") (pintype "input"))
      (node (ref "D07") (pin "F2") (pinfunction "O4_F2") (pintype "output"))
    )
    (net (code "366") (name "WRITE_OK") (class "Default")
      (node (ref "A22") (pin "D2") (pinfunction "D2_D2") (pintype "output"))
      (node (ref "B11") (pin "C1") (pinfunction "IN3_C1") (pintype "input"))
      (node (ref "B15") (pin "R1") (pinfunction "IN2_R1") (pintype "input"))
      (node (ref "C17") (pin "H2") (pinfunction "IN_H2") (pintype "input"))
    )
    (net (code "367") (name "WRITE_OK+UTS") (class "Default")
      (node (ref "B12") (pin "D1") (pinfunction "IN4_D1") (pintype "input"))
      (node (ref "B12") (pin "K1") (pinfunction "IN4_K1") (pintype "input"))
      (node (ref "C17") (pin "M1") (pinfunction "OUT_M1") (pintype "output"))
    )
    (net (code "368") (name "WRTM") (class "Default")
      (node (ref "B11") (pin "A1") (pinfunction "IN1_A1") (pintype "input"))
      (node (ref "C10") (pin "K2") (pinfunction "IN1A_K2") (pintype "input"))
      (node (ref "C12") (pin "N2") (pinfunction "IN1_N2") (pintype "input"))
      (node (ref "D07") (pin "H2") (pinfunction "O6_H2") (pintype "output"))
    )
    (net (code "369") (name "WRTM+FR03") (class "Default")
      (node (ref "B08") (pin "K2") (pinfunction "OUT_K2") (pintype "output"))
      (node (ref "C12") (pin "M1") (pinfunction "IN3_M1") (pintype "input"))
      (node (ref "C12") (pin "V2") (pinfunction "IN3_V2") (pintype "input"))
    )
    (net (code "370") (name "WR_EN") (class "Default")
      (node (ref "A20") (pin "R2") (pinfunction "R2_R2") (pintype "input"))
      (node (ref "A21") (pin "R2") (pinfunction "R2_R2") (pintype "input"))
      (node (ref "A26") (pin "F1") (pinfunction "P$2_F1") (pintype "bidirectional"))
      (node (ref "B20") (pin "R2") (pinfunction "R2_R2") (pintype "input"))
      (node (ref "C10") (pin "H2") (pinfunction "IN2B_H2") (pintype "input"))
      (node (ref "C10") (pin "U2") (pinfunction "IN2B_U2") (pintype "input"))
      (node (ref "C12") (pin "D2") (pinfunction "IN1_D2") (pintype "input"))
      (node (ref "C14") (pin "U1") (pinfunction "0_U1") (pintype "output"))
      (node (ref "C15") (pin "A1") (pinfunction "IN1_A1") (pintype "input"))
      (node (ref "C15") (pin "M1") (pinfunction "IN2_M1") (pintype "input"))
      (node (ref "D09") (pin "B1") (pinfunction "IN1B_B1") (pintype "input"))
      (node (ref "D09") (pin "E2") (pinfunction "IN1B_E2") (pintype "input"))
      (node (ref "D09") (pin "H1") (pinfunction "IN1B_H1") (pintype "input"))
      (node (ref "D09") (pin "L2") (pinfunction "IN1B_L2") (pintype "input"))
      (node (ref "D09") (pin "N1") (pinfunction "IN1B_N1") (pintype "input"))
      (node (ref "D09") (pin "S2") (pinfunction "IN1B_S2") (pintype "input"))
    )
    (net (code "371") (name "XOR_TO_LPB") (class "Default")
      (node (ref "C10") (pin "E2") (pinfunction "IN1B_E2") (pintype "input"))
      (node (ref "C10") (pin "F2") (pinfunction "IN2A_F2") (pintype "input"))
      (node (ref "C10") (pin "S2") (pinfunction "IN1B_S2") (pintype "input"))
      (node (ref "C10") (pin "T2") (pinfunction "IN2A_T2") (pintype "input"))
      (node (ref "D12") (pin "P2") (pinfunction "OUT_P2") (pintype "output"))
    )
    (net (code "372") (name "XSAD") (class "Default")
      (node (ref "A09") (pin "R1") (pinfunction "IN4_R1") (pintype "input"))
      (node (ref "A11") (pin "L2") (pinfunction "OUT_L2") (pintype "output"))
    )
    (net (code "373") (name "XSA_DY") (class "Default")
      (node (ref "A08") (pin "D2") (pinfunction "C_D2") (pintype "input"))
      (node (ref "B14") (pin "B1") (pinfunction "C_B1") (pintype "input"))
      (node (ref "B14") (pin "L2") (pinfunction "C_L2") (pintype "input"))
      (node (ref "C17") (pin "T2") (pinfunction "OUT_T2") (pintype "output"))
    )
    (net (code "374") (name "XSTA") (class "Default")
      (node (ref "B07") (pin "B1") (pinfunction "B1_B1") (pintype "input"))
      (node (ref "B07") (pin "D2") (pinfunction "D2_D2") (pintype "input"))
      (node (ref "B07") (pin "H1") (pinfunction "H1_H1") (pintype "input"))
      (node (ref "B07") (pin "L2") (pinfunction "L2_L2") (pintype "input"))
      (node (ref "B07") (pin "N1") (pinfunction "N1_N1") (pintype "input"))
      (node (ref "B07") (pin "S2") (pinfunction "S2_S2") (pintype "input"))
      (node (ref "C04") (pin "E1") (pinfunction "E1_E1") (pintype "output"))
      (node (ref "C07") (pin "B1") (pinfunction "B1_B1") (pintype "input"))
      (node (ref "C07") (pin "D2") (pinfunction "D2_D2") (pintype "input"))
      (node (ref "C07") (pin "H1") (pinfunction "H1_H1") (pintype "input"))
      (node (ref "C07") (pin "L2") (pinfunction "L2_L2") (pintype "input"))
      (node (ref "D11") (pin "N1") (pinfunction "C_N1") (pintype "input"))
      (node (ref "D13") (pin "M2") (pinfunction "K2_M2") (pintype "input"))
      (node (ref "D13") (pin "N2") (pinfunction "J2_N2") (pintype "input"))
      (node (ref "D13") (pin "P2") (pinfunction "H2_P2") (pintype "input"))
    )
    (net (code "375") (name "unconnected-(A07A-O8-PadP2)") (class "Default")
      (node (ref "A07") (pin "P2") (pinfunction "O8_P2") (pintype "output"))
    )
    (net (code "376") (name "unconnected-(A07A-O9-PadR2)") (class "Default")
      (node (ref "A07") (pin "R2") (pinfunction "O9_R2") (pintype "output"))
    )
    (net (code "377") (name "unconnected-(A07A-~{O8}-PadP1)") (class "Default")
      (node (ref "A07") (pin "P1") (pinfunction "~{O8}_P1") (pintype "output"))
    )
    (net (code "378") (name "unconnected-(A07A-~{O9}-PadR1)") (class "Default")
      (node (ref "A07") (pin "R1") (pinfunction "~{O9}_R1") (pintype "output"))
    )
    (net (code "379") (name "unconnected-(A14-PadD1)") (class "Default")
      (node (ref "A14") (pin "D1") (pinfunction "D1_D1") (pintype "passive"))
    )
    (net (code "380") (name "unconnected-(A14-PadE1)") (class "Default")
      (node (ref "A14") (pin "E1") (pinfunction "E1_E1") (pintype "passive"))
    )
    (net (code "381") (name "unconnected-(A14-PadF1)") (class "Default")
      (node (ref "A14") (pin "F1") (pinfunction "F1_F1") (pintype "passive"))
    )
    (net (code "382") (name "unconnected-(A14-PadJ1)") (class "Default")
      (node (ref "A14") (pin "J1") (pinfunction "J1_J1") (pintype "passive"))
    )
    (net (code "383") (name "unconnected-(A14D-D1-PadN1)") (class "Default")
      (node (ref "A14") (pin "N1") (pinfunction "D1_N1") (pintype "passive"))
    )
    (net (code "384") (name "unconnected-(A14D-E1-PadP1)") (class "Default")
      (node (ref "A14") (pin "P1") (pinfunction "E1_P1") (pintype "passive"))
    )
    (net (code "385") (name "unconnected-(A14D-F1-PadR1)") (class "Default")
      (node (ref "A14") (pin "R1") (pinfunction "F1_R1") (pintype "passive"))
    )
    (net (code "386") (name "unconnected-(A14D-J1-PadU1)") (class "Default")
      (node (ref "A14") (pin "U1") (pinfunction "J1_U1") (pintype "passive"))
    )
    (net (code "387") (name "unconnected-(A18-PadH2)") (class "Default")
      (node (ref "A18") (pin "H2") (pinfunction "H2_H2") (pintype "input"))
    )
    (net (code "388") (name "unconnected-(A18-PadL2)") (class "Default")
      (node (ref "A18") (pin "L2") (pinfunction "L2_L2") (pintype "input"))
    )
    (net (code "389") (name "unconnected-(A18-PadM2)") (class "Default")
      (node (ref "A18") (pin "M2") (pinfunction "M2_M2") (pintype "input"))
    )
    (net (code "390") (name "unconnected-(A20-PadH2)") (class "Default")
      (node (ref "A20") (pin "H2") (pinfunction "H2_H2") (pintype "input"))
    )
    (net (code "391") (name "unconnected-(A20-PadL2)") (class "Default")
      (node (ref "A20") (pin "L2") (pinfunction "L2_L2") (pintype "input"))
    )
    (net (code "392") (name "unconnected-(A20-PadM2)") (class "Default")
      (node (ref "A20") (pin "M2") (pinfunction "M2_M2") (pintype "input"))
    )
    (net (code "393") (name "unconnected-(A21-PadH2)") (class "Default")
      (node (ref "A21") (pin "H2") (pinfunction "H2_H2") (pintype "input"))
    )
    (net (code "394") (name "unconnected-(A21-PadL2)") (class "Default")
      (node (ref "A21") (pin "L2") (pinfunction "L2_L2") (pintype "input"))
    )
    (net (code "395") (name "unconnected-(A21-PadM2)") (class "Default")
      (node (ref "A21") (pin "M2") (pinfunction "M2_M2") (pintype "input"))
    )
    (net (code "396") (name "unconnected-(A22-PadE2)") (class "Default")
      (node (ref "A22") (pin "E2") (pinfunction "E2_E2") (pintype "passive"))
    )
    (net (code "397") (name "unconnected-(AB01-PadBM1)") (class "Default")
      (node (ref "AB01") (pin "BM1") (pinfunction "BM1_BM1") (pintype "output"))
    )
    (net (code "398") (name "unconnected-(AB01-PadBN1)") (class "Default")
      (node (ref "AB01") (pin "BN1") (pinfunction "BN1_BN1") (pintype "input"))
    )
    (net (code "399") (name "unconnected-(AB01-PadBP1)") (class "Default")
      (node (ref "AB01") (pin "BP1") (pinfunction "BP1_BP1") (pintype "input"))
    )
    (net (code "400") (name "unconnected-(AB01-PadBR1)") (class "Default")
      (node (ref "AB01") (pin "BR1") (pinfunction "BR1_BR1") (pintype "output"))
    )
    (net (code "401") (name "unconnected-(B05H-B-PadL2)") (class "Default")
      (node (ref "B05") (pin "L2") (pinfunction "B_L2") (pintype "input"))
    )
    (net (code "402") (name "unconnected-(B05H-E-PadP2)") (class "Default")
      (node (ref "B05") (pin "P2") (pinfunction "E_P2") (pintype "open_collector"))
    )
    (net (code "403") (name "unconnected-(B18-PadH2)") (class "Default")
      (node (ref "B18") (pin "H2") (pinfunction "H2_H2") (pintype "input"))
    )
    (net (code "404") (name "unconnected-(B18-PadL2)") (class "Default")
      (node (ref "B18") (pin "L2") (pinfunction "L2_L2") (pintype "input"))
    )
    (net (code "405") (name "unconnected-(B18-PadM2)") (class "Default")
      (node (ref "B18") (pin "M2") (pinfunction "M2_M2") (pintype "input"))
    )
    (net (code "406") (name "unconnected-(B20-PadH2)") (class "Default")
      (node (ref "B20") (pin "H2") (pinfunction "H2_H2") (pintype "input"))
    )
    (net (code "407") (name "unconnected-(B20-PadL2)") (class "Default")
      (node (ref "B20") (pin "L2") (pinfunction "L2_L2") (pintype "input"))
    )
    (net (code "408") (name "unconnected-(B20-PadM2)") (class "Default")
      (node (ref "B20") (pin "M2") (pinfunction "M2_M2") (pintype "input"))
    )
    (net (code "409") (name "unconnected-(B22K-A-PadR2)") (class "Default")
      (node (ref "B22") (pin "R2") (pinfunction "A_R2") (pintype "input"))
    )
    (net (code "410") (name "unconnected-(B22K-D-PadU2)") (class "Default")
      (node (ref "B22") (pin "U2") (pinfunction "D_U2") (pintype "output"))
    )
    (net (code "411") (name "unconnected-(C02A-IN13-PadP2)") (class "Default")
      (node (ref "C02") (pin "P2") (pinfunction "IN13_P2") (pintype "input"))
    )
    (net (code "412") (name "unconnected-(C02A-IN14-PadS2)") (class "Default")
      (node (ref "C02") (pin "S2") (pinfunction "IN14_S2") (pintype "input"))
    )
    (net (code "413") (name "unconnected-(C02A-O13-PadR2)") (class "Default")
      (node (ref "C02") (pin "R2") (pinfunction "O13_R2") (pintype "output"))
    )
    (net (code "414") (name "unconnected-(C02A-O14-PadT2)") (class "Default")
      (node (ref "C02") (pin "T2") (pinfunction "O14_T2") (pintype "output"))
    )
    (net (code "415") (name "unconnected-(C03A-IN13-PadP2)") (class "Default")
      (node (ref "C03") (pin "P2") (pinfunction "IN13_P2") (pintype "input"))
    )
    (net (code "416") (name "unconnected-(C03A-IN14-PadS2)") (class "Default")
      (node (ref "C03") (pin "S2") (pinfunction "IN14_S2") (pintype "input"))
    )
    (net (code "417") (name "unconnected-(C03A-IN15-PadU2)") (class "Default")
      (node (ref "C03") (pin "U2") (pinfunction "IN15_U2") (pintype "input"))
    )
    (net (code "418") (name "unconnected-(C03A-O13-PadR2)") (class "Default")
      (node (ref "C03") (pin "R2") (pinfunction "O13_R2") (pintype "output"))
    )
    (net (code "419") (name "unconnected-(C03A-O14-PadT2)") (class "Default")
      (node (ref "C03") (pin "T2") (pinfunction "O14_T2") (pintype "output"))
    )
    (net (code "420") (name "unconnected-(C03A-O15-PadV2)") (class "Default")
      (node (ref "C03") (pin "V2") (pinfunction "O15_V2") (pintype "output"))
    )
    (net (code "421") (name "unconnected-(C07-PadN1)") (class "Default")
      (node (ref "C07") (pin "N1") (pinfunction "N1_N1") (pintype "input"))
    )
    (net (code "422") (name "unconnected-(C07-PadP1)") (class "Default")
      (node (ref "C07") (pin "P1") (pinfunction "P1_P1") (pintype "input"))
    )
    (net (code "423") (name "unconnected-(C07-PadR1)") (class "Default")
      (node (ref "C07") (pin "R1") (pinfunction "R1_R1") (pintype "input"))
    )
    (net (code "424") (name "unconnected-(C07-PadS1)") (class "Default")
      (node (ref "C07") (pin "S1") (pinfunction "S1_S1") (pintype "output"))
    )
    (net (code "425") (name "unconnected-(C07-PadS2)") (class "Default")
      (node (ref "C07") (pin "S2") (pinfunction "S2_S2") (pintype "input"))
    )
    (net (code "426") (name "unconnected-(C07-PadT2)") (class "Default")
      (node (ref "C07") (pin "T2") (pinfunction "T2_T2") (pintype "input"))
    )
    (net (code "427") (name "unconnected-(C07-PadU1)") (class "Default")
      (node (ref "C07") (pin "U1") (pinfunction "U1_U1") (pintype "output"))
    )
    (net (code "428") (name "unconnected-(C07-PadU2)") (class "Default")
      (node (ref "C07") (pin "U2") (pinfunction "U2_U2") (pintype "input"))
    )
    (net (code "429") (name "unconnected-(C07-PadV1)") (class "Default")
      (node (ref "C07") (pin "V1") (pinfunction "V1_V1") (pintype "output"))
    )
    (net (code "430") (name "unconnected-(C07-PadV2)") (class "Default")
      (node (ref "C07") (pin "V2") (pinfunction "V2_V2") (pintype "output"))
    )
    (net (code "431") (name "unconnected-(CD18-PadAN2)") (class "Default")
      (node (ref "CD18") (pin "AN2") (pinfunction "AN2_AN2") (pintype "output"))
    )
    (net (code "432") (name "unconnected-(CD18-PadAU1)") (class "Default")
      (node (ref "CD18") (pin "AU1") (pinfunction "AU1_AU1") (pintype "output"))
    )
    (net (code "433") (name "unconnected-(D07A-O8-PadP2)") (class "Default")
      (node (ref "D07") (pin "P2") (pinfunction "O8_P2") (pintype "output"))
    )
    (net (code "434") (name "unconnected-(D07A-O9-PadR2)") (class "Default")
      (node (ref "D07") (pin "R2") (pinfunction "O9_R2") (pintype "output"))
    )
    (net (code "435") (name "unconnected-(D07A-~{O8}-PadP1)") (class "Default")
      (node (ref "D07") (pin "P1") (pinfunction "~{O8}_P1") (pintype "output"))
    )
    (net (code "436") (name "unconnected-(D07A-~{O9}-PadR1)") (class "Default")
      (node (ref "D07") (pin "R1") (pinfunction "~{O9}_R1") (pintype "output"))
    )
    (net (code "437") (name "unconnected-(D13-PadD2)") (class "Default")
      (node (ref "D13") (pin "D2") (pinfunction "D2_D2") (pintype "passive"))
    )
    (net (code "438") (name "unconnected-(D13-PadE2)") (class "Default")
      (node (ref "D13") (pin "E2") (pinfunction "E2_E2") (pintype "passive"))
    )
    (net (code "439") (name "unconnected-(D14-PadN2)") (class "Default")
      (node (ref "D14") (pin "N2") (pinfunction "N2_N2") (pintype "passive"))
    )
    (net (code "440") (name "unconnected-(D14-PadP2)") (class "Default")
      (node (ref "D14") (pin "P2") (pinfunction "P2_P2") (pintype "passive"))
    )
    (net (code "441") (name "unconnected-(D14-PadR2)") (class "Default")
      (node (ref "D14") (pin "R2") (pinfunction "R2_R2") (pintype "passive"))
    )
    (net (code "442") (name "unconnected-(D14-PadS2)") (class "Default")
      (node (ref "D14") (pin "S2") (pinfunction "S2_S2") (pintype "passive"))
    )
    (net (code "443") (name "unconnected-(D14-PadU2)") (class "Default")
      (node (ref "D14") (pin "U2") (pinfunction "U2_U2") (pintype "passive"))
    )
    (net (code "444") (name "unconnected-(D14E-N2-PadJ1)") (class "Default")
      (node (ref "D14") (pin "J1") (pinfunction "N2_J1") (pintype "passive"))
    )
    (net (code "445") (name "unconnected-(D14E-R2-PadF1)") (class "Default")
      (node (ref "D14") (pin "F1") (pinfunction "R2_F1") (pintype "passive"))
    )
    (net (code "446") (name "unconnected-(D14E-S2-PadE1)") (class "Default")
      (node (ref "D14") (pin "E1") (pinfunction "S2_E1") (pintype "passive"))
    )
    (net (code "447") (name "unconnected-(D14E-U2-PadD1)") (class "Default")
      (node (ref "D14") (pin "D1") (pinfunction "U2_D1") (pintype "passive"))
    )
    (net (code "448") (name "unconnected-(D14E-V2-PadB1)") (class "Default")
      (node (ref "D14") (pin "B1") (pinfunction "V2_B1") (pintype "passive"))
    )
    (net (code "449") (name "unconnected-(D15-PadE2)") (class "Default")
      (node (ref "D15") (pin "E2") (pinfunction "E2_E2") (pintype "output"))
    )
    (net (code "450") (name "unconnected-(D15-PadM2)") (class "Default")
      (node (ref "D15") (pin "M2") (pinfunction "M2_M2") (pintype "passive"))
    )
    (net (code "451") (name "unconnected-(D15-PadP2)") (class "Default")
      (node (ref "D15") (pin "P2") (pinfunction "P2_P2") (pintype "passive"))
    )
    (net (code "452") (name "unconnected-(D15-PadR2)") (class "Default")
      (node (ref "D15") (pin "R2") (pinfunction "R2_R2") (pintype "passive"))
    )
    (net (code "453") (name "unconnected-(D15-PadT2)") (class "Default")
      (node (ref "D15") (pin "T2") (pinfunction "T2_T2") (pintype "passive"))
    )
    (net (code "454") (name "unconnected-(D16D-D1-PadN1)") (class "Default")
      (node (ref "D16") (pin "N1") (pinfunction "D1_N1") (pintype "passive"))
    )
    (net (code "455") (name "unconnected-(D16D-E1-PadP1)") (class "Default")
      (node (ref "D16") (pin "P1") (pinfunction "E1_P1") (pintype "passive"))
    )
    (net (code "456") (name "unconnected-(D16D-F1-PadR1)") (class "Default")
      (node (ref "D16") (pin "R1") (pinfunction "F1_R1") (pintype "passive"))
    )
    (net (code "457") (name "unconnected-(D16D-J1-PadU1)") (class "Default")
      (node (ref "D16") (pin "U1") (pinfunction "J1_U1") (pintype "passive"))
    )
    (net (code "458") (name "~{0_TO_AC}") (class "Default")
      (node (ref "B05") (pin "H1") (pinfunction "B_H1") (pintype "input"))
      (node (ref "B06") (pin "T2") (pinfunction "OUT_T2") (pintype "output"))
    )
    (net (code "459") (name "~{0_TO_DTB}") (class "Default")
      (node (ref "A11") (pin "L1") (pinfunction "IN_L1") (pintype "input"))
      (node (ref "B09") (pin "A1") (pinfunction "R_A1") (pintype "input"))
      (node (ref "B09") (pin "K2") (pinfunction "R_K2") (pintype "input"))
      (node (ref "B10") (pin "L1") (pinfunction "OUT_L1") (pintype "output"))
      (node (ref "C09") (pin "A1") (pinfunction "R_A1") (pintype "input"))
      (node (ref "C09") (pin "K2") (pinfunction "R_K2") (pintype "input"))
    )
    (net (code "460") (name "~{0_TO_EF}") (class "Default")
      (node (ref "A08") (pin "A1") (pinfunction "R_A1") (pintype "input"))
      (node (ref "A08") (pin "N2") (pinfunction "S_N2") (pintype "input"))
      (node (ref "A08") (pin "R1") (pinfunction "S_R1") (pintype "input"))
      (node (ref "A11") (pin "F2") (pinfunction "OUT_F2") (pintype "output"))
    )
    (net (code "461") (name "~{0_TO_LPB}") (class "Default")
      (node (ref "D08") (pin "A1") (pinfunction "A1_A1") (pintype "input"))
      (node (ref "D08") (pin "K2") (pinfunction "K2_K2") (pintype "input"))
      (node (ref "D12") (pin "J2") (pinfunction "OUT_J2") (pintype "output"))
    )
    (net (code "462") (name "~{0_TO_STATE}") (class "Default")
      (node (ref "C16") (pin "L1") (pinfunction "OUT_L1") (pintype "output"))
      (node (ref "CD18") (pin "AV2") (pinfunction "AV2_AV2") (pintype "input"))
    )
    (net (code "463") (name "~{0_TO_STA}") (class "Default")
      (node (ref "A11") (pin "P1") (pinfunction "OUT_P1") (pintype "output"))
      (node (ref "B07") (pin "A1") (pinfunction "A1_A1") (pintype "input"))
      (node (ref "B07") (pin "K2") (pinfunction "K2_K2") (pintype "input"))
      (node (ref "B11") (pin "P2") (pinfunction "IN2_P2") (pintype "input"))
      (node (ref "C07") (pin "A1") (pinfunction "A1_A1") (pintype "input"))
    )
    (net (code "464") (name "~{0_TO_W}") (class "Default")
      (node (ref "C16") (pin "E1") (pinfunction "OUT_E1") (pintype "output"))
      (node (ref "CD18") (pin "BH2") (pinfunction "BH2_BH2") (pintype "input"))
    )
    (net (code "465") (name "~{00}") (class "Default")
      (node (ref "A07") (pin "D1") (pinfunction "~{O0}_D1") (pintype "output"))
      (node (ref "B22") (pin "S2") (pinfunction "B_S2") (pintype "input"))
    )
    (net (code "466") (name "~{01}") (class "Default")
      (node (ref "A07") (pin "E1") (pinfunction "~{O1}_E1") (pintype "output"))
      (node (ref "A23") (pin "N1") (pinfunction "B_N1") (pintype "input"))
    )
    (net (code "467") (name "~{02}") (class "Default")
      (node (ref "A07") (pin "J1") (pinfunction "~{O2}_J1") (pintype "output"))
      (node (ref "A23") (pin "D2") (pinfunction "A_D2") (pintype "input"))
    )
    (net (code "468") (name "~{03}") (class "Default")
      (node (ref "A07") (pin "N1") (pinfunction "~{O3}_N1") (pintype "output"))
      (node (ref "A23") (pin "E2") (pinfunction "B_E2") (pintype "input"))
    )
    (net (code "469") (name "~{04}") (class "Default")
      (node (ref "A07") (pin "F1") (pinfunction "~{O4}_F1") (pintype "output"))
      (node (ref "A23") (pin "K2") (pinfunction "A_K2") (pintype "input"))
    )
    (net (code "470") (name "~{05}") (class "Default")
      (node (ref "A07") (pin "M1") (pinfunction "~{O5}_M1") (pintype "output"))
      (node (ref "A23") (pin "L2") (pinfunction "B_L2") (pintype "input"))
    )
    (net (code "471") (name "~{06}") (class "Default")
      (node (ref "A07") (pin "H1") (pinfunction "~{O6}_H1") (pintype "output"))
      (node (ref "A23") (pin "R2") (pinfunction "A_R2") (pintype "input"))
    )
    (net (code "472") (name "~{07}") (class "Default")
      (node (ref "A07") (pin "L1") (pinfunction "~{O7}_L1") (pintype "output"))
      (node (ref "A23") (pin "S2") (pinfunction "B_S2") (pintype "input"))
    )
    (net (code "473") (name "~{76}") (class "Default")
      (node (ref "C06") (pin "T2") (pinfunction "OUT_T2") (pintype "output"))
      (node (ref "D12") (pin "R2") (pinfunction "IN1_R2") (pintype "input"))
      (node (ref "D12") (pin "S2") (pinfunction "IN2_S2") (pintype "input"))
    )
    (net (code "474") (name "~{77}") (class "Default")
      (node (ref "C06") (pin "V2") (pinfunction "OUT_V2") (pintype "output"))
      (node (ref "D12") (pin "T2") (pinfunction "IN3_T2") (pintype "input"))
      (node (ref "D12") (pin "U2") (pinfunction "IN4_U2") (pintype "input"))
    )
    (net (code "475") (name "~{ADDR_ACC}") (class "Default")
      (node (ref "B08") (pin "T2") (pinfunction "IN1_T2") (pintype "input"))
      (node (ref "C17") (pin "P1") (pinfunction "OUT_P1") (pintype "output"))
    )
    (net (code "476") (name "~{B-BRK}") (class "Default")
      (node (ref "B02") (pin "C1") (pinfunction "C_C1") (pintype "input"))
      (node (ref "B02") (pin "F2") (pinfunction "C_F2") (pintype "input"))
      (node (ref "B02") (pin "J1") (pinfunction "C_J1") (pintype "input"))
      (node (ref "B02") (pin "M2") (pinfunction "C_M2") (pintype "input"))
      (node (ref "B02") (pin "P1") (pinfunction "C_P1") (pintype "input"))
      (node (ref "B02") (pin "T2") (pinfunction "C_T2") (pintype "input"))
      (node (ref "B10") (pin "V2") (pinfunction "OUT_V2") (pintype "output"))
    )
    (net (code "477") (name "~{BAC_00}") (class "Default")
      (node (ref "B06") (pin "A1") (pinfunction "IN_A1") (pintype "input"))
      (node (ref "C03") (pin "B1") (pinfunction "O1_B1") (pintype "output"))
      (node (ref "D10") (pin "F1") (pinfunction "IN1_F1") (pintype "input"))
    )
    (net (code "478") (name "~{BAC_01}") (class "Default")
      (node (ref "B06") (pin "D1") (pinfunction "IN_D1") (pintype "input"))
      (node (ref "C03") (pin "E1") (pinfunction "O2_E1") (pintype "output"))
      (node (ref "D10") (pin "H1") (pinfunction "IN2_H1") (pintype "input"))
    )
    (net (code "479") (name "~{BAC_02}") (class "Default")
      (node (ref "B06") (pin "F1") (pinfunction "IN_F1") (pintype "input"))
      (node (ref "C03") (pin "H1") (pinfunction "O3_H1") (pintype "output"))
      (node (ref "D10") (pin "J1") (pinfunction "IN3_J1") (pintype "input"))
    )
    (net (code "480") (name "~{BAC_03}") (class "Default")
      (node (ref "B06") (pin "J1") (pinfunction "IN_J1") (pintype "input"))
      (node (ref "C03") (pin "K1") (pinfunction "O4_K1") (pintype "output"))
      (node (ref "D10") (pin "K1") (pinfunction "IN4_K1") (pintype "input"))
    )
    (net (code "481") (name "~{BAC_04}") (class "Default")
      (node (ref "B06") (pin "L1") (pinfunction "IN_L1") (pintype "input"))
      (node (ref "C03") (pin "M1") (pinfunction "O5_M1") (pintype "output"))
      (node (ref "D10") (pin "K2") (pinfunction "IN5_K2") (pintype "input"))
    )
    (net (code "482") (name "~{BAC_05}") (class "Default")
      (node (ref "B06") (pin "N1") (pinfunction "IN_N1") (pintype "input"))
      (node (ref "C03") (pin "P1") (pinfunction "O6_P1") (pintype "output"))
    )
    (net (code "483") (name "~{BAC_06}") (class "Default")
      (node (ref "B06") (pin "R1") (pinfunction "IN_R1") (pintype "input"))
      (node (ref "C03") (pin "S1") (pinfunction "O7_S1") (pintype "output"))
    )
    (net (code "484") (name "~{BAC_07}") (class "Default")
      (node (ref "B06") (pin "V1") (pinfunction "IN_V1") (pintype "input"))
      (node (ref "C03") (pin "U1") (pinfunction "O8_U1") (pintype "output"))
    )
    (net (code "485") (name "~{BAC_08}") (class "Default")
      (node (ref "B06") (pin "C1") (pinfunction "IN_C1") (pintype "input"))
      (node (ref "C03") (pin "F2") (pinfunction "O9_F2") (pintype "output"))
    )
    (net (code "486") (name "~{BAC_09}") (class "Default")
      (node (ref "B06") (pin "E2") (pinfunction "IN_E2") (pintype "input"))
      (node (ref "C03") (pin "J2") (pinfunction "O10_J2") (pintype "output"))
    )
    (net (code "487") (name "~{BAC_10}") (class "Default")
      (node (ref "A10") (pin "D2") (pinfunction "IN1_D2") (pintype "input"))
      (node (ref "B06") (pin "H2") (pinfunction "IN_H2") (pintype "input"))
      (node (ref "C03") (pin "L2") (pinfunction "O11_L2") (pintype "output"))
    )
    (net (code "488") (name "~{BAC_11}") (class "Default")
      (node (ref "B06") (pin "K2") (pinfunction "IN_K2") (pintype "input"))
      (node (ref "C03") (pin "N2") (pinfunction "O12_N2") (pintype "output"))
      (node (ref "C11") (pin "R2") (pinfunction "IN2_R2") (pintype "input"))
    )
    (net (code "489") (name "~{BLK_IN_SYNC}") (class "Default")
      (node (ref "A10") (pin "A1") (pinfunction "IN1_A1") (pintype "input"))
      (node (ref "C13") (pin "R1") (pinfunction "IN_R1") (pintype "input"))
      (node (ref "D10") (pin "J2") (pinfunction "OUT_J2") (pintype "output"))
    )
    (net (code "490") (name "~{BMB_00}") (class "Default")
      (node (ref "C02") (pin "B1") (pinfunction "O1_B1") (pintype "output"))
      (node (ref "C06") (pin "A1") (pinfunction "IN_A1") (pintype "input"))
    )
    (net (code "491") (name "~{BMB_01}") (class "Default")
      (node (ref "C02") (pin "E1") (pinfunction "O2_E1") (pintype "output"))
      (node (ref "C06") (pin "D1") (pinfunction "IN_D1") (pintype "input"))
    )
    (net (code "492") (name "~{BMB_02}") (class "Default")
      (node (ref "C02") (pin "H1") (pinfunction "O3_H1") (pintype "output"))
      (node (ref "C06") (pin "F1") (pinfunction "IN_F1") (pintype "input"))
    )
    (net (code "493") (name "~{BMB_03}") (class "Default")
      (node (ref "C02") (pin "K1") (pinfunction "O4_K1") (pintype "output"))
      (node (ref "C06") (pin "J1") (pinfunction "IN_J1") (pintype "input"))
    )
    (net (code "494") (name "~{BMB_04}") (class "Default")
      (node (ref "C02") (pin "M1") (pinfunction "O5_M1") (pintype "output"))
      (node (ref "C06") (pin "L1") (pinfunction "IN_L1") (pintype "input"))
    )
    (net (code "495") (name "~{BMB_05}") (class "Default")
      (node (ref "C02") (pin "P1") (pinfunction "O6_P1") (pintype "output"))
      (node (ref "C06") (pin "N1") (pinfunction "IN_N1") (pintype "input"))
    )
    (net (code "496") (name "~{BMB_06}") (class "Default")
      (node (ref "C02") (pin "S1") (pinfunction "O7_S1") (pintype "output"))
      (node (ref "C06") (pin "R1") (pinfunction "IN_R1") (pintype "input"))
    )
    (net (code "497") (name "~{BMB_07}") (class "Default")
      (node (ref "C02") (pin "U1") (pinfunction "O8_U1") (pintype "output"))
      (node (ref "C06") (pin "V1") (pinfunction "IN_V1") (pintype "input"))
    )
    (net (code "498") (name "~{BMB_08}") (class "Default")
      (node (ref "C02") (pin "F2") (pinfunction "O9_F2") (pintype "output"))
      (node (ref "C06") (pin "C1") (pinfunction "IN_C1") (pintype "input"))
    )
    (net (code "499") (name "~{BMB_09}") (class "Default")
      (node (ref "C02") (pin "J2") (pinfunction "O10_J2") (pintype "output"))
      (node (ref "C06") (pin "E2") (pinfunction "IN_E2") (pintype "input"))
    )
    (net (code "500") (name "~{BMB_10}") (class "Default")
      (node (ref "C02") (pin "L2") (pinfunction "O11_L2") (pintype "output"))
      (node (ref "C06") (pin "H2") (pinfunction "IN_H2") (pintype "input"))
    )
    (net (code "501") (name "~{BMB_11}") (class "Default")
      (node (ref "C02") (pin "N2") (pinfunction "O12_N2") (pintype "output"))
      (node (ref "C06") (pin "K2") (pinfunction "IN_K2") (pintype "input"))
    )
    (net (code "502") (name "~{BMR00}") (class "Default")
      (node (ref "A23") (pin "H1") (pinfunction "B_H1") (pintype "input"))
      (node (ref "B14") (pin "R2") (pinfunction "0_R2") (pintype "output"))
    )
    (net (code "503") (name "~{BMR01}") (class "Default")
      (node (ref "A23") (pin "A1") (pinfunction "A_A1") (pintype "input"))
      (node (ref "B14") (pin "E1") (pinfunction "1_E1") (pintype "output"))
    )
    (net (code "504") (name "~{C00}") (class "Default")
      (node (ref "A12") (pin "P2") (pinfunction "IN1_P2") (pintype "input"))
      (node (ref "B13") (pin "P1") (pinfunction "D_P1") (pintype "input"))
      (node (ref "B13") (pin "S2") (pinfunction "C_S2") (pintype "input"))
      (node (ref "B13") (pin "U1") (pinfunction "0_U1") (pintype "output"))
      (node (ref "B15") (pin "H1") (pinfunction "IN1_H1") (pintype "input"))
      (node (ref "C15") (pin "J2") (pinfunction "IN2_J2") (pintype "input"))
    )
    (net (code "505") (name "~{C01}") (class "Default")
      (node (ref "A12") (pin "R2") (pinfunction "IN2_R2") (pintype "input"))
      (node (ref "B10") (pin "P1") (pinfunction "IN3_P1") (pintype "input"))
      (node (ref "B13") (pin "M2") (pinfunction "D_M2") (pintype "input"))
      (node (ref "B13") (pin "R2") (pinfunction "0_R2") (pintype "output"))
      (node (ref "C12") (pin "F2") (pinfunction "IN3_F2") (pintype "input"))
      (node (ref "D10") (pin "D1") (pinfunction "IN4_D1") (pintype "input"))
    )
    (net (code "506") (name "~{CK00}") (class "Default")
      (node (ref "A18") (pin "N2") (pinfunction "N2_N2") (pintype "input"))
      (node (ref "B14") (pin "T2") (pinfunction "D_T2") (pintype "input"))
      (node (ref "B14") (pin "U1") (pinfunction "0_U1") (pintype "output"))
    )
    (net (code "507") (name "~{CK01}") (class "Default")
      (node (ref "B14") (pin "V1") (pinfunction "0_V1") (pintype "output"))
      (node (ref "C16") (pin "S2") (pinfunction "IN2_S2") (pintype "input"))
      (node (ref "C16") (pin "T2") (pinfunction "IN3_T2") (pintype "input"))
      (node (ref "C16") (pin "U2") (pinfunction "IN4_U2") (pintype "input"))
    )
    (net (code "508") (name "~{CLR_DF}") (class "Default")
      (node (ref "A11") (pin "U1") (pinfunction "OUT_U1") (pintype "output"))
      (node (ref "D11") (pin "N2") (pinfunction "S_N2") (pintype "input"))
    )
    (net (code "509") (name "~{CLR_DTF}") (class "Default")
      (node (ref "C13") (pin "U1") (pinfunction "OUT_U1") (pintype "output"))
      (node (ref "D11") (pin "U2") (pinfunction "S_U2") (pintype "input"))
    )
    (net (code "510") (name "~{CSTA}") (class "Default")
      (node (ref "A10") (pin "L2") (pinfunction "IN1_L2") (pintype "input"))
      (node (ref "C04") (pin "D1") (pinfunction "D1_D1") (pintype "output"))
    )
    (net (code "511") (name "~{DATA}") (class "Default")
      (node (ref "B12") (pin "N1") (pinfunction "IN2_N1") (pintype "input"))
      (node (ref "C11") (pin "L2") (pinfunction "IN1_L2") (pintype "input"))
      (node (ref "C13") (pin "H1") (pinfunction "OUT_H1") (pintype "output"))
      (node (ref "C16") (pin "D2") (pinfunction "IN1_D2") (pintype "input"))
    )
    (net (code "512") (name "~{DB_00}") (class "Default")
      (node (ref "A06") (pin "B1") (pinfunction "P$2_B1") (pintype "bidirectional"))
      (node (ref "B02") (pin "D1") (pinfunction "D_D1") (pintype "open_collector"))
      (node (ref "D06") (pin "B1") (pinfunction "P$2_B1") (pintype "bidirectional"))
    )
    (net (code "513") (name "~{DB_01}") (class "Default")
      (node (ref "A06") (pin "D1") (pinfunction "P$2_D1") (pintype "bidirectional"))
      (node (ref "B02") (pin "E1") (pinfunction "E_E1") (pintype "open_collector"))
      (node (ref "D06") (pin "D1") (pinfunction "P$2_D1") (pintype "bidirectional"))
    )
    (net (code "514") (name "~{DB_02}") (class "Default")
      (node (ref "A06") (pin "E1") (pinfunction "P$2_E1") (pintype "bidirectional"))
      (node (ref "B02") (pin "K1") (pinfunction "D_K1") (pintype "open_collector"))
      (node (ref "D06") (pin "E1") (pinfunction "P$2_E1") (pintype "bidirectional"))
    )
    (net (code "515") (name "~{DB_03}") (class "Default")
      (node (ref "A06") (pin "H1") (pinfunction "P$2_H1") (pintype "bidirectional"))
      (node (ref "B02") (pin "L1") (pinfunction "E_L1") (pintype "open_collector"))
      (node (ref "D06") (pin "H1") (pinfunction "P$2_H1") (pintype "bidirectional"))
    )
    (net (code "516") (name "~{DB_04}") (class "Default")
      (node (ref "A06") (pin "J1") (pinfunction "P$2_J1") (pintype "bidirectional"))
      (node (ref "B02") (pin "R1") (pinfunction "D_R1") (pintype "open_collector"))
      (node (ref "D06") (pin "J1") (pinfunction "P$2_J1") (pintype "bidirectional"))
    )
    (net (code "517") (name "~{DB_05}") (class "Default")
      (node (ref "A06") (pin "L1") (pinfunction "P$2_L1") (pintype "bidirectional"))
      (node (ref "B02") (pin "S1") (pinfunction "E_S1") (pintype "open_collector"))
      (node (ref "D06") (pin "L1") (pinfunction "P$2_L1") (pintype "bidirectional"))
    )
    (net (code "518") (name "~{DB_06}") (class "Default")
      (node (ref "A06") (pin "M1") (pinfunction "P$2_M1") (pintype "bidirectional"))
      (node (ref "B02") (pin "H2") (pinfunction "D_H2") (pintype "open_collector"))
      (node (ref "D06") (pin "M1") (pinfunction "P$2_M1") (pintype "bidirectional"))
    )
    (net (code "519") (name "~{DB_07}") (class "Default")
      (node (ref "A06") (pin "P1") (pinfunction "P$2_P1") (pintype "bidirectional"))
      (node (ref "B02") (pin "J2") (pinfunction "E_J2") (pintype "open_collector"))
      (node (ref "D06") (pin "P1") (pinfunction "P$2_P1") (pintype "bidirectional"))
    )
    (net (code "520") (name "~{DB_08}") (class "Default")
      (node (ref "A06") (pin "S1") (pinfunction "P$2_S1") (pintype "bidirectional"))
      (node (ref "B02") (pin "N2") (pinfunction "D_N2") (pintype "open_collector"))
      (node (ref "D06") (pin "S1") (pinfunction "P$2_S1") (pintype "bidirectional"))
    )
    (net (code "521") (name "~{DB_09}") (class "Default")
      (node (ref "A06") (pin "D2") (pinfunction "P$2_D2") (pintype "bidirectional"))
      (node (ref "B02") (pin "P2") (pinfunction "E_P2") (pintype "open_collector"))
      (node (ref "D06") (pin "D2") (pinfunction "P$2_D2") (pintype "bidirectional"))
    )
    (net (code "522") (name "~{DB_10}") (class "Default")
      (node (ref "A06") (pin "E2") (pinfunction "P$2_E2") (pintype "bidirectional"))
      (node (ref "B02") (pin "U2") (pinfunction "D_U2") (pintype "open_collector"))
      (node (ref "D06") (pin "E2") (pinfunction "P$2_E2") (pintype "bidirectional"))
    )
    (net (code "523") (name "~{DB_11}") (class "Default")
      (node (ref "A06") (pin "H2") (pinfunction "P$2_H2") (pintype "bidirectional"))
      (node (ref "B02") (pin "V2") (pinfunction "E_V2") (pintype "open_collector"))
      (node (ref "D06") (pin "H2") (pinfunction "P$2_H2") (pintype "bidirectional"))
    )
    (net (code "524") (name "~{DF}") (class "Default")
      (node (ref "B05") (pin "A1") (pinfunction "A_A1") (pintype "input"))
      (node (ref "B12") (pin "J1") (pinfunction "IN3_J1") (pintype "input"))
      (node (ref "D11") (pin "P2") (pinfunction "1_P2") (pintype "output"))
    )
    (net (code "525") (name "~{DTB_00}") (class "Default")
      (node (ref "B02") (pin "A1") (pinfunction "A_A1") (pintype "input"))
      (node (ref "C09") (pin "F1") (pinfunction "0_F1") (pintype "output"))
    )
    (net (code "526") (name "~{DTB_01}") (class "Default")
      (node (ref "B02") (pin "B1") (pinfunction "B_B1") (pintype "input"))
      (node (ref "C09") (pin "J2") (pinfunction "0_J2") (pintype "output"))
    )
    (net (code "527") (name "~{DTB_02}") (class "Default")
      (node (ref "B02") (pin "F1") (pinfunction "A_F1") (pintype "input"))
      (node (ref "C09") (pin "M1") (pinfunction "0_M1") (pintype "output"))
    )
    (net (code "528") (name "~{DTB_03}") (class "Default")
      (node (ref "B02") (pin "H1") (pinfunction "B_H1") (pintype "input"))
      (node (ref "C09") (pin "R2") (pinfunction "0_R2") (pintype "output"))
    )
    (net (code "529") (name "~{DTB_04}") (class "Default")
      (node (ref "B02") (pin "M1") (pinfunction "A_M1") (pintype "input"))
      (node (ref "C09") (pin "U1") (pinfunction "0_U1") (pintype "output"))
    )
    (net (code "530") (name "~{DTB_05}") (class "Default")
      (node (ref "B02") (pin "N1") (pinfunction "B_N1") (pintype "input"))
      (node (ref "C09") (pin "V1") (pinfunction "0_V1") (pintype "output"))
    )
    (net (code "531") (name "~{DTB_06}") (class "Default")
      (node (ref "B02") (pin "D2") (pinfunction "A_D2") (pintype "input"))
      (node (ref "B09") (pin "F1") (pinfunction "0_F1") (pintype "output"))
    )
    (net (code "532") (name "~{DTB_07}") (class "Default")
      (node (ref "B02") (pin "E2") (pinfunction "B_E2") (pintype "input"))
      (node (ref "B09") (pin "V1") (pinfunction "0_V1") (pintype "output"))
    )
    (net (code "533") (name "~{DTB_08}") (class "Default")
      (node (ref "B02") (pin "K2") (pinfunction "A_K2") (pintype "input"))
      (node (ref "B09") (pin "M1") (pinfunction "0_M1") (pintype "output"))
    )
    (net (code "534") (name "~{DTB_09}") (class "Default")
      (node (ref "B02") (pin "L2") (pinfunction "B_L2") (pintype "input"))
      (node (ref "B09") (pin "R2") (pinfunction "0_R2") (pintype "output"))
    )
    (net (code "535") (name "~{DTB_10}") (class "Default")
      (node (ref "B02") (pin "R2") (pinfunction "A_R2") (pintype "input"))
      (node (ref "B09") (pin "U1") (pinfunction "0_U1") (pintype "output"))
    )
    (net (code "536") (name "~{DTB_11}") (class "Default")
      (node (ref "B02") (pin "S2") (pinfunction "B_S2") (pintype "input"))
      (node (ref "B09") (pin "J2") (pinfunction "0_J2") (pintype "output"))
    )
    (net (code "537") (name "~{DTF}") (class "Default")
      (node (ref "B04") (pin "L2") (pinfunction "B_L2") (pintype "input"))
      (node (ref "B12") (pin "C1") (pinfunction "IN3_C1") (pintype "input"))
      (node (ref "D11") (pin "V2") (pinfunction "1_V2") (pintype "output"))
    )
    (net (code "538") (name "~{DTSF}") (class "Default")
      (node (ref "C05") (pin "B1") (pinfunction "B1_B1") (pintype "output"))
    )
    (net (code "539") (name "~{EA_00}") (class "Default")
      (node (ref "A06") (pin "V2") (pinfunction "P$2_V2") (pintype "bidirectional"))
      (node (ref "B05") (pin "R1") (pinfunction "D_R1") (pintype "open_collector"))
      (node (ref "D06") (pin "V2") (pinfunction "P$2_V2") (pintype "bidirectional"))
    )
    (net (code "540") (name "~{EA_01}") (class "Default")
      (node (ref "A06") (pin "T2") (pinfunction "P$2_T2") (pintype "bidirectional"))
      (node (ref "B05") (pin "S1") (pinfunction "E_S1") (pintype "open_collector"))
      (node (ref "D06") (pin "T2") (pinfunction "P$2_T2") (pintype "bidirectional"))
    )
    (net (code "541") (name "~{EA_02}") (class "Default")
      (node (ref "A06") (pin "S2") (pinfunction "P$2_S2") (pintype "bidirectional"))
      (node (ref "B05") (pin "H2") (pinfunction "D_H2") (pintype "open_collector"))
      (node (ref "D06") (pin "S2") (pinfunction "P$2_S2") (pintype "bidirectional"))
    )
    (net (code "542") (name "~{EF}") (class "Default")
      (node (ref "A11") (pin "K1") (pinfunction "OUT_K1") (pintype "output"))
      (node (ref "B04") (pin "A1") (pinfunction "A_A1") (pintype "input"))
    )
    (net (code "543") (name "~{END}") (class "Default")
      (node (ref "A08") (pin "F1") (pinfunction "0_F1") (pintype "output"))
      (node (ref "A09") (pin "M2") (pinfunction "IN3_M2") (pintype "input"))
      (node (ref "B04") (pin "F1") (pinfunction "A_F1") (pintype "input"))
    )
    (net (code "544") (name "~{ENI}") (class "Default")
      (node (ref "B03") (pin "L2") (pinfunction "B_L2") (pintype "input"))
      (node (ref "C07") (pin "M1") (pinfunction "M1_M1") (pintype "output"))
    )
    (net (code "545") (name "~{FR_00}") (class "Default")
      (node (ref "B03") (pin "N1") (pinfunction "B_N1") (pintype "input"))
      (node (ref "B07") (pin "U1") (pinfunction "U1_U1") (pintype "output"))
      (node (ref "C12") (pin "K1") (pinfunction "IN1_K1") (pintype "input"))
      (node (ref "C12") (pin "P1") (pinfunction "IN1_P1") (pintype "input"))
    )
    (net (code "546") (name "~{FR_01}") (class "Default")
      (node (ref "A12") (pin "H2") (pinfunction "IN1_H2") (pintype "input"))
      (node (ref "B03") (pin "D2") (pinfunction "A_D2") (pintype "input"))
      (node (ref "B05") (pin "E2") (pinfunction "B_E2") (pintype "input"))
      (node (ref "B07") (pin "V1") (pinfunction "V1_V1") (pintype "output"))
    )
    (net (code "547") (name "~{FR_02}") (class "Default")
      (node (ref "B03") (pin "E2") (pinfunction "B_E2") (pintype "input"))
      (node (ref "C07") (pin "F1") (pinfunction "F1_F1") (pintype "output"))
    )
    (net (code "548") (name "~{FR_03}") (class "Default")
      (node (ref "B03") (pin "K2") (pinfunction "A_K2") (pintype "input"))
      (node (ref "B08") (pin "J2") (pinfunction "IN2_J2") (pintype "input"))
      (node (ref "C07") (pin "J2") (pinfunction "J2_J2") (pintype "output"))
    )
    (net (code "549") (name "~{IM_00}") (class "Default")
      (node (ref "A04") (pin "B1") (pinfunction "P$2_B1") (pintype "bidirectional"))
      (node (ref "B03") (pin "D1") (pinfunction "D_D1") (pintype "open_collector"))
      (node (ref "B04") (pin "D1") (pinfunction "D_D1") (pintype "open_collector"))
      (node (ref "D04") (pin "B1") (pinfunction "P$2_B1") (pintype "bidirectional"))
    )
    (net (code "550") (name "~{IM_01}") (class "Default")
      (node (ref "A04") (pin "D1") (pinfunction "P$2_D1") (pintype "bidirectional"))
      (node (ref "B03") (pin "E1") (pinfunction "E_E1") (pintype "open_collector"))
      (node (ref "B04") (pin "E1") (pinfunction "E_E1") (pintype "open_collector"))
      (node (ref "D04") (pin "D1") (pinfunction "P$2_D1") (pintype "bidirectional"))
    )
    (net (code "551") (name "~{IM_02}") (class "Default")
      (node (ref "A04") (pin "E1") (pinfunction "P$2_E1") (pintype "bidirectional"))
      (node (ref "B03") (pin "K1") (pinfunction "D_K1") (pintype "open_collector"))
      (node (ref "B04") (pin "K1") (pinfunction "D_K1") (pintype "open_collector"))
      (node (ref "D04") (pin "E1") (pinfunction "P$2_E1") (pintype "bidirectional"))
    )
    (net (code "552") (name "~{IM_03}") (class "Default")
      (node (ref "A04") (pin "H1") (pinfunction "P$2_H1") (pintype "bidirectional"))
      (node (ref "B03") (pin "L1") (pinfunction "E_L1") (pintype "open_collector"))
      (node (ref "B04") (pin "L1") (pinfunction "E_L1") (pintype "open_collector"))
      (node (ref "D04") (pin "H1") (pinfunction "P$2_H1") (pintype "bidirectional"))
    )
    (net (code "553") (name "~{IM_04}") (class "Default")
      (node (ref "A04") (pin "J1") (pinfunction "P$2_J1") (pintype "bidirectional"))
      (node (ref "B03") (pin "R1") (pinfunction "D_R1") (pintype "open_collector"))
      (node (ref "B04") (pin "R1") (pinfunction "D_R1") (pintype "open_collector"))
      (node (ref "D04") (pin "J1") (pinfunction "P$2_J1") (pintype "bidirectional"))
    )
    (net (code "554") (name "~{IM_05}") (class "Default")
      (node (ref "A04") (pin "L1") (pinfunction "P$2_L1") (pintype "bidirectional"))
      (node (ref "B03") (pin "S1") (pinfunction "E_S1") (pintype "open_collector"))
      (node (ref "B04") (pin "S1") (pinfunction "E_S1") (pintype "open_collector"))
      (node (ref "D04") (pin "L1") (pinfunction "P$2_L1") (pintype "bidirectional"))
    )
    (net (code "555") (name "~{IM_06}") (class "Default")
      (node (ref "A04") (pin "M1") (pinfunction "P$2_M1") (pintype "bidirectional"))
      (node (ref "B03") (pin "H2") (pinfunction "D_H2") (pintype "open_collector"))
      (node (ref "B04") (pin "H2") (pinfunction "D_H2") (pintype "open_collector"))
      (node (ref "D04") (pin "M1") (pinfunction "P$2_M1") (pintype "bidirectional"))
    )
    (net (code "556") (name "~{IM_07}") (class "Default")
      (node (ref "A04") (pin "P1") (pinfunction "P$2_P1") (pintype "bidirectional"))
      (node (ref "B03") (pin "J2") (pinfunction "E_J2") (pintype "open_collector"))
      (node (ref "B04") (pin "J2") (pinfunction "E_J2") (pintype "open_collector"))
      (node (ref "D04") (pin "P1") (pinfunction "P$2_P1") (pintype "bidirectional"))
    )
    (net (code "557") (name "~{IM_08}") (class "Default")
      (node (ref "A04") (pin "S1") (pinfunction "P$2_S1") (pintype "bidirectional"))
      (node (ref "B03") (pin "N2") (pinfunction "D_N2") (pintype "open_collector"))
      (node (ref "B04") (pin "N2") (pinfunction "D_N2") (pintype "open_collector"))
      (node (ref "D04") (pin "S1") (pinfunction "P$2_S1") (pintype "bidirectional"))
    )
    (net (code "558") (name "~{IM_09}") (class "Default")
      (node (ref "A04") (pin "D2") (pinfunction "P$2_D2") (pintype "bidirectional"))
      (node (ref "B03") (pin "P2") (pinfunction "E_P2") (pintype "open_collector"))
      (node (ref "D04") (pin "D2") (pinfunction "P$2_D2") (pintype "bidirectional"))
    )
    (net (code "559") (name "~{IM_10}") (class "Default")
      (node (ref "A04") (pin "E2") (pinfunction "P$2_E2") (pintype "bidirectional"))
      (node (ref "D04") (pin "E2") (pinfunction "P$2_E2") (pintype "bidirectional"))
    )
    (net (code "560") (name "~{IM_11}") (class "Default")
      (node (ref "A04") (pin "H2") (pinfunction "P$2_H2") (pintype "bidirectional"))
      (node (ref "B04") (pin "P2") (pinfunction "E_P2") (pintype "open_collector"))
      (node (ref "D04") (pin "H2") (pinfunction "P$2_H2") (pintype "bidirectional"))
    )
    (net (code "561") (name "~{INT_RQ}") (class "Default")
      (node (ref "A12") (pin "K1") (pinfunction "OUT_K1") (pintype "output"))
      (node (ref "B05") (pin "B1") (pinfunction "B_B1") (pintype "input"))
    )
    (net (code "562") (name "~{LDMF}") (class "Default")
      (node (ref "B08") (pin "P2") (pinfunction "IN1_P2") (pintype "input"))
      (node (ref "C05") (pin "F1") (pinfunction "F1_F1") (pintype "output"))
    )
    (net (code "563") (name "~{LPB_00}") (class "Default")
      (node (ref "D08") (pin "F1") (pinfunction "F1_F1") (pintype "output"))
      (node (ref "D10") (pin "M1") (pinfunction "IN1_M1") (pintype "input"))
    )
    (net (code "564") (name "~{LPB_01}") (class "Default")
      (node (ref "D08") (pin "M1") (pinfunction "M1_M1") (pintype "output"))
      (node (ref "D10") (pin "N1") (pinfunction "IN2_N1") (pintype "input"))
    )
    (net (code "565") (name "~{LPB_02}") (class "Default")
      (node (ref "D08") (pin "U1") (pinfunction "U1_U1") (pintype "output"))
      (node (ref "D10") (pin "P1") (pinfunction "IN3_P1") (pintype "input"))
    )
    (net (code "566") (name "~{LPB_03}") (class "Default")
      (node (ref "D08") (pin "J2") (pinfunction "J2_J2") (pintype "output"))
      (node (ref "D10") (pin "R1") (pinfunction "IN4_R1") (pintype "input"))
    )
    (net (code "567") (name "~{LPB_04}") (class "Default")
      (node (ref "D08") (pin "R2") (pinfunction "R2_R2") (pintype "output"))
      (node (ref "D10") (pin "R2") (pinfunction "IN5_R2") (pintype "input"))
    )
    (net (code "568") (name "~{LPB_05}") (class "Default")
      (node (ref "D08") (pin "V1") (pinfunction "V1_V1") (pintype "output"))
      (node (ref "D10") (pin "S2") (pinfunction "IN6_S2") (pintype "input"))
      (node (ref "D10") (pin "T2") (pinfunction "IN7_T2") (pintype "input"))
      (node (ref "D10") (pin "U2") (pinfunction "IN8_U2") (pintype "input"))
    )
    (net (code "569") (name "~{M-STOP}") (class "Default")
      (node (ref "A11") (pin "S1") (pinfunction "OUT_S1") (pintype "output"))
      (node (ref "B14") (pin "D1") (pinfunction "S_D1") (pintype "input"))
      (node (ref "C07") (pin "K2") (pinfunction "K2_K2") (pintype "input"))
      (node (ref "D14") (pin "L1") (pinfunction "M1_L1") (pintype "input"))
    )
    (net (code "570") (name "~{MB_TO_DTB}") (class "Default")
      (node (ref "D12") (pin "F1") (pinfunction "IN1_F1") (pintype "input"))
      (node (ref "D12") (pin "H1") (pinfunction "IN2_H1") (pintype "input"))
      (node (ref "D12") (pin "J1") (pinfunction "IN3_J1") (pintype "input"))
      (node (ref "D12") (pin "K1") (pinfunction "IN4_K1") (pintype "input"))
      (node (ref "D12") (pin "S1") (pinfunction "OUT_S1") (pintype "output"))
    )
    (net (code "571") (name "~{MC00}") (class "Default")
      (node (ref "A10") (pin "R1") (pinfunction "IN2_R1") (pintype "input"))
      (node (ref "B11") (pin "T2") (pinfunction "IN1_T2") (pintype "input"))
      (node (ref "B13") (pin "F1") (pinfunction "0_F1") (pintype "output"))
    )
    (net (code "572") (name "~{MC01}") (class "Default")
      (node (ref "B11") (pin "P1") (pinfunction "IN1_P1") (pintype "input"))
      (node (ref "B13") (pin "J2") (pinfunction "0_J2") (pintype "output"))
      (node (ref "C11") (pin "B1") (pinfunction "IN2_B1") (pintype "input"))
      (node (ref "D10") (pin "E2") (pinfunction "IN6_E2") (pintype "input"))
    )
    (net (code "573") (name "~{MC02}") (class "Default")
      (node (ref "B13") (pin "C1") (pinfunction "D_C1") (pintype "input"))
      (node (ref "B13") (pin "M1") (pinfunction "0_M1") (pintype "output"))
      (node (ref "D10") (pin "F2") (pinfunction "IN7_F2") (pintype "input"))
    )
    (net (code "574") (name "~{MF00}") (class "Default")
      (node (ref "B04") (pin "D2") (pinfunction "A_D2") (pintype "input"))
      (node (ref "B05") (pin "M1") (pinfunction "A_M1") (pintype "input"))
      (node (ref "D11") (pin "F1") (pinfunction "0_F1") (pintype "output"))
    )
    (net (code "575") (name "~{MF01}") (class "Default")
      (node (ref "B04") (pin "E2") (pinfunction "B_E2") (pintype "input"))
      (node (ref "B05") (pin "N1") (pinfunction "B_N1") (pintype "input"))
      (node (ref "D11") (pin "J2") (pinfunction "0_J2") (pintype "output"))
    )
    (net (code "576") (name "~{MF02}") (class "Default")
      (node (ref "B04") (pin "K2") (pinfunction "A_K2") (pintype "input"))
      (node (ref "B05") (pin "D2") (pinfunction "A_D2") (pintype "input"))
      (node (ref "D11") (pin "M1") (pinfunction "0_M1") (pintype "output"))
    )
    (net (code "577") (name "~{MKTK}") (class "Default")
      (node (ref "A08") (pin "P2") (pinfunction "1_P2") (pintype "output"))
      (node (ref "A09") (pin "K2") (pinfunction "IN1_K2") (pintype "input"))
      (node (ref "B04") (pin "B1") (pinfunction "B_B1") (pintype "input"))
    )
    (net (code "578") (name "~{MKT}") (class "Default")
      (node (ref "B10") (pin "R1") (pinfunction "IN4_R1") (pintype "input"))
      (node (ref "B13") (pin "T2") (pinfunction "D_T2") (pintype "input"))
      (node (ref "B13") (pin "V1") (pinfunction "0_V1") (pintype "output"))
      (node (ref "C14") (pin "N1") (pinfunction "C_N1") (pintype "input"))
      (node (ref "D10") (pin "H2") (pinfunction "IN8_H2") (pintype "input"))
    )
    (net (code "579") (name "~{MK_BLK_END}") (class "Default")
      (node (ref "A09") (pin "C1") (pinfunction "IN3_C1") (pintype "input"))
      (node (ref "CD18") (pin "BV1") (pinfunction "BV1_BV1") (pintype "output"))
    )
    (net (code "580") (name "~{MK_BLK_MK}") (class "Default")
      (node (ref "CD18") (pin "AD2") (pinfunction "AD2_AD2") (pintype "output"))
    )
    (net (code "581") (name "~{MK_BLK_START}") (class "Default")
      (node (ref "A09") (pin "A1") (pinfunction "IN1_A1") (pintype "input"))
      (node (ref "CD18") (pin "AF1") (pinfunction "AF1_AF1") (pintype "output"))
    )
    (net (code "582") (name "~{MK_BLK_SYNC}") (class "Default")
      (node (ref "CD18") (pin "BT2") (pinfunction "BT2_BT2") (pintype "output"))
    )
    (net (code "583") (name "~{MK_DATA_SYNC}") (class "Default")
      (node (ref "CD18") (pin "AJ1") (pinfunction "AJ1_AJ1") (pintype "output"))
    )
    (net (code "584") (name "~{MK_DATA}") (class "Default")
      (node (ref "A09") (pin "B1") (pinfunction "IN2_B1") (pintype "input"))
      (node (ref "CD18") (pin "AU2") (pinfunction "AU2_AU2") (pintype "output"))
    )
    (net (code "585") (name "~{MK_END}") (class "Default")
      (node (ref "A09") (pin "D1") (pinfunction "IN4_D1") (pintype "input"))
      (node (ref "CD18") (pin "AH2") (pinfunction "AH2_AH2") (pintype "output"))
    )
    (net (code "586") (name "~{MOVE}") (class "Default")
      (node (ref "A09") (pin "F2") (pinfunction "IN3_F2") (pintype "input"))
      (node (ref "D07") (pin "D1") (pinfunction "~{O0}_D1") (pintype "output"))
    )
    (net (code "587") (name "~{MR00}") (class "Default")
      (node (ref "B03") (pin "H1") (pinfunction "B_H1") (pintype "input"))
      (node (ref "B07") (pin "R2") (pinfunction "R2_R2") (pintype "output"))
    )
    (net (code "588") (name "~{MR01}") (class "Default")
      (node (ref "B03") (pin "M1") (pinfunction "A_M1") (pintype "input"))
      (node (ref "B14") (pin "C1") (pinfunction "D_C1") (pintype "input"))
      (node (ref "C07") (pin "R2") (pinfunction "R2_R2") (pintype "output"))
    )
    (net (code "589") (name "~{PAR}") (class "Default")
      (node (ref "A08") (pin "S1") (pinfunction "1_S1") (pintype "output"))
      (node (ref "A12") (pin "E1") (pinfunction "IN2_E1") (pintype "input"))
      (node (ref "B04") (pin "M1") (pinfunction "A_M1") (pintype "input"))
    )
    (net (code "590") (name "~{PC+ES}") (class "Default")
      (node (ref "A11") (pin "J2") (pinfunction "OUT_J2") (pintype "output"))
      (node (ref "B11") (pin "R2") (pinfunction "IN3_R2") (pintype "input"))
    )
    (net (code "591") (name "~{PWR_CLR}") (class "Default")
      (node (ref "A10") (pin "H2") (pinfunction "IN1_H2") (pintype "input"))
      (node (ref "A10") (pin "M2") (pinfunction "IN2_M2") (pintype "input"))
      (node (ref "A12") (pin "A1") (pinfunction "IN1_A1") (pintype "input"))
      (node (ref "A23") (pin "M1") (pinfunction "A_M1") (pintype "input"))
      (node (ref "B08") (pin "U2") (pinfunction "IN2_U2") (pintype "input"))
      (node (ref "C05") (pin "K1") (pinfunction "OUT_K1") (pintype "output"))
      (node (ref "C06") (pin "P2") (pinfunction "IN_P2") (pintype "input"))
      (node (ref "C11") (pin "U2") (pinfunction "IN2_U2") (pintype "input"))
      (node (ref "C14") (pin "R1") (pinfunction "S_R1") (pintype "input"))
      (node (ref "D11") (pin "A1") (pinfunction "R_A1") (pintype "input"))
    )
    (net (code "592") (name "~{RDD_00}") (class "Default")
      (node (ref "A21") (pin "V2") (pinfunction "V2_V2") (pintype "output"))
    )
    (net (code "593") (name "~{RDD_01}") (class "Default")
      (node (ref "B20") (pin "V2") (pinfunction "V2_V2") (pintype "output"))
    )
    (net (code "594") (name "~{RDD_02}") (class "Default")
      (node (ref "A20") (pin "V2") (pinfunction "V2_V2") (pintype "output"))
    )
    (net (code "595") (name "~{RDMK}") (class "Default")
      (node (ref "B18") (pin "V2") (pinfunction "V2_V2") (pintype "output"))
    )
    (net (code "596") (name "~{READ_ALL}") (class "Default")
      (node (ref "C11") (pin "M1") (pinfunction "IN2_M1") (pintype "input"))
      (node (ref "D07") (pin "N1") (pinfunction "~{O3}_N1") (pintype "output"))
    )
    (net (code "597") (name "~{READ_DATA}") (class "Default")
      (node (ref "B08") (pin "L2") (pinfunction "IN1_L2") (pintype "input"))
      (node (ref "B11") (pin "J2") (pinfunction "IN1_J2") (pintype "input"))
      (node (ref "D07") (pin "J1") (pinfunction "~{O2}_J1") (pintype "output"))
    )
    (net (code "598") (name "~{RSTA}") (class "Default")
      (node (ref "B03") (pin "C1") (pinfunction "C_C1") (pintype "input"))
      (node (ref "B03") (pin "F2") (pinfunction "C_F2") (pintype "input"))
      (node (ref "B03") (pin "J1") (pinfunction "C_J1") (pintype "input"))
      (node (ref "B03") (pin "M2") (pinfunction "C_M2") (pintype "input"))
      (node (ref "B03") (pin "P1") (pinfunction "C_P1") (pintype "input"))
      (node (ref "C04") (pin "B1") (pinfunction "B1_B1") (pintype "output"))
    )
    (net (code "599") (name "~{RSTB}") (class "Default")
      (node (ref "B04") (pin "C1") (pinfunction "C_C1") (pintype "input"))
      (node (ref "B04") (pin "F2") (pinfunction "C_F2") (pintype "input"))
      (node (ref "B04") (pin "J1") (pinfunction "C_J1") (pintype "input"))
      (node (ref "B04") (pin "M2") (pinfunction "C_M2") (pintype "input"))
      (node (ref "B04") (pin "P1") (pinfunction "C_P1") (pintype "input"))
      (node (ref "C05") (pin "D1") (pinfunction "D1_D1") (pintype "output"))
    )
    (net (code "600") (name "~{SEARCH}") (class "Default")
      (node (ref "B05") (pin "K2") (pinfunction "A_K2") (pintype "input"))
      (node (ref "B11") (pin "K2") (pinfunction "IN2_K2") (pintype "input"))
      (node (ref "D07") (pin "E1") (pinfunction "~{O1}_E1") (pintype "output"))
    )
    (net (code "601") (name "~{SEL}") (class "Default")
      (node (ref "A08") (pin "J2") (pinfunction "0_J2") (pintype "output"))
      (node (ref "A09") (pin "N2") (pinfunction "IN4_N2") (pintype "input"))
      (node (ref "B04") (pin "H1") (pinfunction "B_H1") (pintype "input"))
    )
    (net (code "602") (name "~{SE}") (class "Default")
      (node (ref "A09") (pin "H1") (pinfunction "IN2_H1") (pintype "input"))
      (node (ref "D07") (pin "L1") (pinfunction "~{O7}_L1") (pintype "output"))
    )
    (net (code "603") (name "~{SH_EN}") (class "Default")
      (node (ref "A11") (pin "M2") (pinfunction "IN_M2") (pintype "input"))
      (node (ref "A12") (pin "V2") (pinfunction "OUT_V2") (pintype "output"))
      (node (ref "C10") (pin "C1") (pinfunction "IN2A_C1") (pintype "input"))
      (node (ref "C10") (pin "J1") (pinfunction "IN2A_J1") (pintype "input"))
      (node (ref "C10") (pin "P1") (pinfunction "IN2A_P1") (pintype "input"))
    )
    (net (code "604") (name "~{SKP_RQ}") (class "Default")
      (node (ref "A12") (pin "S1") (pinfunction "OUT_S1") (pintype "output"))
      (node (ref "B05") (pin "F1") (pinfunction "A_F1") (pintype "input"))
    )
    (net (code "605") (name "~{SP_DY}") (class "Default")
      (node (ref "C14") (pin "M2") (pinfunction "D_M2") (pintype "input"))
      (node (ref "D14") (pin "F2") (pinfunction "F2_F2") (pintype "output"))
    )
    (net (code "606") (name "~{ST_BLK_MK}") (class "Default")
      (node (ref "A09") (pin "D2") (pinfunction "IN1_D2") (pintype "input"))
      (node (ref "A09") (pin "M1") (pinfunction "IN1_M1") (pintype "input"))
      (node (ref "C13") (pin "F2") (pinfunction "OUT_F2") (pintype "output"))
    )
    (net (code "607") (name "~{ST_CK_0P}") (class "Default")
      (node (ref "C13") (pin "A1") (pinfunction "IN_A1") (pintype "input"))
      (node (ref "D17") (pin "L2") (pinfunction "F2_L2") (pintype "output"))
    )
    (net (code "608") (name "~{ST_CK}") (class "Default")
      (node (ref "C13") (pin "K1") (pinfunction "OUT_K1") (pintype "output"))
      (node (ref "C16") (pin "E2") (pinfunction "IN2_E2") (pintype "input"))
    )
    (net (code "609") (name "~{ST_DATA}") (class "Default")
      (node (ref "C13") (pin "J2") (pinfunction "OUT_J2") (pintype "output"))
    )
    (net (code "610") (name "~{ST_FINAL}") (class "Default")
      (node (ref "C11") (pin "M2") (pinfunction "IN2_M2") (pintype "input"))
      (node (ref "C13") (pin "M1") (pinfunction "OUT_M1") (pintype "output"))
      (node (ref "C16") (pin "F2") (pinfunction "IN3_F2") (pintype "input"))
    )
    (net (code "611") (name "~{ST_IDLE}") (class "Default")
      (node (ref "A09") (pin "E2") (pinfunction "IN2_E2") (pintype "input"))
      (node (ref "A09") (pin "N1") (pinfunction "IN2_N1") (pintype "input"))
      (node (ref "C13") (pin "L2") (pinfunction "OUT_L2") (pintype "output"))
    )
    (net (code "612") (name "~{ST_REV_CK}") (class "Default")
      (node (ref "C13") (pin "E1") (pinfunction "OUT_E1") (pintype "output"))
    )
    (net (code "613") (name "~{SWTM}") (class "Default")
      (node (ref "B06") (pin "R2") (pinfunction "OUT_R2") (pintype "output"))
      (node (ref "C10") (pin "L2") (pinfunction "IN1B_L2") (pintype "input"))
    )
    (net (code "614") (name "~{SYNC-P}") (class "Default")
      (node (ref "B10") (pin "J2") (pinfunction "OUT_J2") (pintype "output"))
      (node (ref "B13") (pin "A1") (pinfunction "R_A1") (pintype "input"))
      (node (ref "B13") (pin "K2") (pinfunction "R_K2") (pintype "input"))
    )
    (net (code "615") (name "~{SYNC}") (class "Default")
      (node (ref "CD18") (pin "BM2") (pinfunction "BM2_BM2") (pintype "output"))
    )
    (net (code "616") (name "~{TIM}") (class "Default")
      (node (ref "A08") (pin "M1") (pinfunction "0_M1") (pintype "output"))
      (node (ref "A09") (pin "L2") (pinfunction "IN2_L2") (pintype "input"))
      (node (ref "B04") (pin "N1") (pinfunction "B_N1") (pintype "input"))
    )
    (net (code "617") (name "~{TM_EN}") (class "Default")
      (node (ref "B15") (pin "D1") (pinfunction "IN1_D1") (pintype "input"))
      (node (ref "B15") (pin "D2") (pinfunction "IN1_D2") (pintype "input"))
      (node (ref "C12") (pin "C1") (pinfunction "IN3_C1") (pintype "input"))
      (node (ref "C12") (pin "K2") (pinfunction "IN2_K2") (pintype "input"))
      (node (ref "C13") (pin "P1") (pinfunction "OUT_P1") (pintype "output"))
      (node (ref "D15") (pin "J2") (pinfunction "J2_J2") (pintype "input"))
      (node (ref "D15") (pin "K2") (pinfunction "K2_K2") (pintype "input"))
    )
    (net (code "618") (name "~{TP00_A}") (class "Default")
      (node (ref "A15") (pin "M1") (pinfunction "IN1_M1") (pintype "input"))
      (node (ref "A15") (pin "N1") (pinfunction "IN2_N1") (pintype "input"))
      (node (ref "A15") (pin "P1") (pinfunction "IN3_P1") (pintype "input"))
      (node (ref "A15") (pin "R1") (pinfunction "IN4_R1") (pintype "input"))
      (node (ref "A16") (pin "L2") (pinfunction "F2_L2") (pintype "output"))
    )
    (net (code "619") (name "~{TP0_XTLK_DY}") (class "Default")
      (node (ref "A11") (pin "R2") (pinfunction "OUT_R2") (pintype "output"))
      (node (ref "A15") (pin "F2") (pinfunction "IN3_F2") (pintype "input"))
      (node (ref "A16") (pin "J2") (pinfunction "J2_J2") (pintype "input"))
      (node (ref "A16") (pin "K2") (pinfunction "K2_K2") (pintype "input"))
    )
    (net (code "620") (name "~{TP00}") (class "Default")
      (node (ref "A15") (pin "E1") (pinfunction "OUT_E1") (pintype "output"))
      (node (ref "A15") (pin "F1") (pinfunction "IN1_F1") (pintype "input"))
      (node (ref "A15") (pin "H1") (pinfunction "IN2_H1") (pintype "input"))
      (node (ref "A15") (pin "J1") (pinfunction "IN3_J1") (pintype "input"))
      (node (ref "A15") (pin "K1") (pinfunction "IN4_K1") (pintype "input"))
      (node (ref "B13") (pin "N1") (pinfunction "C_N1") (pintype "input"))
      (node (ref "CD18") (pin "AN1") (pinfunction "AN1_AN1") (pintype "input"))
    )
    (net (code "621") (name "~{TP01_A}") (class "Default")
      (node (ref "A15") (pin "R2") (pinfunction "IN1_R2") (pintype "input"))
      (node (ref "A15") (pin "S2") (pinfunction "IN2_S2") (pintype "input"))
      (node (ref "A15") (pin "T2") (pinfunction "IN3_T2") (pintype "input"))
      (node (ref "A15") (pin "U2") (pinfunction "IN4_U2") (pintype "input"))
      (node (ref "B16") (pin "L2") (pinfunction "F2_L2") (pintype "output"))
    )
    (net (code "622") (name "~{TP1_XTLK_DY}") (class "Default")
      (node (ref "A11") (pin "V2") (pinfunction "OUT_V2") (pintype "output"))
      (node (ref "A15") (pin "B1") (pinfunction "IN2_B1") (pintype "input"))
      (node (ref "B16") (pin "H2") (pinfunction "H2_H2") (pintype "input"))
      (node (ref "B16") (pin "J2") (pinfunction "J2_J2") (pintype "input"))
    )
    (net (code "623") (name "~{TP01}") (class "Default")
      (node (ref "A15") (pin "J2") (pinfunction "OUT_J2") (pintype "output"))
      (node (ref "A15") (pin "K2") (pinfunction "IN1_K2") (pintype "input"))
      (node (ref "A15") (pin "L2") (pinfunction "IN2_L2") (pintype "input"))
      (node (ref "A15") (pin "M2") (pinfunction "IN3_M2") (pintype "input"))
      (node (ref "A15") (pin "N2") (pinfunction "IN4_N2") (pintype "input"))
      (node (ref "B13") (pin "L2") (pinfunction "C_L2") (pintype "input"))
    )
    (net (code "624") (name "~{TS03}") (class "Default")
      (node (ref "C04") (pin "K1") (pinfunction "OUT_K1") (pintype "output"))
      (node (ref "D17") (pin "H2") (pinfunction "H2_H2") (pintype "input"))
      (node (ref "D17") (pin "J2") (pinfunction "J2_J2") (pintype "input"))
      (node (ref "D17") (pin "K2") (pinfunction "K2_K2") (pintype "input"))
    )
    (net (code "625") (name "~{T_00}") (class "Default")
      (node (ref "A24") (pin "V2") (pinfunction "P$2_V2") (pintype "bidirectional"))
      (node (ref "B22") (pin "V2") (pinfunction "E_V2") (pintype "output"))
      (node (ref "B23") (pin "V2") (pinfunction "P$1_V2") (pintype "passive"))
    )
    (net (code "626") (name "~{T_01}") (class "Default")
      (node (ref "A23") (pin "S1") (pinfunction "E_S1") (pintype "output"))
      (node (ref "A24") (pin "M2") (pinfunction "P$2_M2") (pintype "bidirectional"))
      (node (ref "B23") (pin "M2") (pinfunction "P$1_M2") (pintype "passive"))
    )
    (net (code "627") (name "~{T_02}") (class "Default")
      (node (ref "A23") (pin "H2") (pinfunction "D_H2") (pintype "output"))
      (node (ref "A24") (pin "N2") (pinfunction "P$2_N2") (pintype "bidirectional"))
      (node (ref "B23") (pin "N2") (pinfunction "P$1_N2") (pintype "passive"))
    )
    (net (code "628") (name "~{T_03}") (class "Default")
      (node (ref "A23") (pin "J2") (pinfunction "E_J2") (pintype "output"))
      (node (ref "A24") (pin "P2") (pinfunction "P$2_P2") (pintype "bidirectional"))
      (node (ref "B23") (pin "P2") (pinfunction "P$1_P2") (pintype "passive"))
    )
    (net (code "629") (name "~{T_04}") (class "Default")
      (node (ref "A23") (pin "N2") (pinfunction "D_N2") (pintype "output"))
      (node (ref "A24") (pin "R2") (pinfunction "P$2_R2") (pintype "bidirectional"))
      (node (ref "B23") (pin "R2") (pinfunction "P$1_R2") (pintype "passive"))
    )
    (net (code "630") (name "~{T_05}") (class "Default")
      (node (ref "A23") (pin "P2") (pinfunction "E_P2") (pintype "output"))
      (node (ref "A24") (pin "S2") (pinfunction "P$2_S2") (pintype "bidirectional"))
      (node (ref "B23") (pin "S2") (pinfunction "P$1_S2") (pintype "passive"))
    )
    (net (code "631") (name "~{T_06}") (class "Default")
      (node (ref "A23") (pin "U2") (pinfunction "D_U2") (pintype "output"))
      (node (ref "A24") (pin "T2") (pinfunction "P$2_T2") (pintype "bidirectional"))
      (node (ref "B23") (pin "T2") (pinfunction "P$1_T2") (pintype "passive"))
    )
    (net (code "632") (name "~{T_07}") (class "Default")
      (node (ref "A23") (pin "V2") (pinfunction "E_V2") (pintype "output"))
      (node (ref "A24") (pin "U2") (pinfunction "P$2_U2") (pintype "bidirectional"))
      (node (ref "B23") (pin "U2") (pinfunction "P$1_U2") (pintype "passive"))
    )
    (net (code "633") (name "~{T_FWD}") (class "Default")
      (node (ref "A23") (pin "K1") (pinfunction "D_K1") (pintype "output"))
      (node (ref "A24") (pin "E2") (pinfunction "P$2_E2") (pintype "bidirectional"))
      (node (ref "B23") (pin "H2") (pinfunction "P$1_H2") (pintype "passive"))
    )
    (net (code "634") (name "~{T_GO}") (class "Default")
      (node (ref "A23") (pin "D1") (pinfunction "D_D1") (pintype "output"))
      (node (ref "A24") (pin "C2") (pinfunction "P$2_C2") (pintype "bidirectional"))
      (node (ref "B23") (pin "D2") (pinfunction "P$1_D2") (pintype "passive"))
    )
    (net (code "635") (name "~{T_PWR_CLR}") (class "Default")
      (node (ref "A23") (pin "R1") (pinfunction "D_R1") (pintype "output"))
      (node (ref "A24") (pin "H2") (pinfunction "P$2_H2") (pintype "bidirectional"))
      (node (ref "B23") (pin "K2") (pinfunction "P$1_K2") (pintype "passive"))
    )
    (net (code "636") (name "~{T_REV}") (class "Default")
      (node (ref "A23") (pin "L1") (pinfunction "E_L1") (pintype "output"))
      (node (ref "A24") (pin "F2") (pinfunction "P$2_F2") (pintype "bidirectional"))
      (node (ref "B23") (pin "J2") (pinfunction "P$1_J2") (pintype "passive"))
    )
    (net (code "637") (name "~{T_SINGLE_UNIT}") (class "Default")
      (node (ref "A24") (pin "K2") (pinfunction "P$2_K2") (pintype "bidirectional"))
      (node (ref "B21") (pin "T2") (pinfunction "IN_T2") (pintype "input"))
    )
    (net (code "638") (name "~{T_STOP}") (class "Default")
      (node (ref "A23") (pin "E1") (pinfunction "E_E1") (pintype "output"))
      (node (ref "A24") (pin "D2") (pinfunction "P$2_D2") (pintype "bidirectional"))
      (node (ref "B23") (pin "E2") (pinfunction "P$1_E2") (pintype "passive"))
    )
    (net (code "639") (name "~{T_TRK}") (class "Default")
      (node (ref "A18") (pin "V2") (pinfunction "V2_V2") (pintype "output"))
      (node (ref "B15") (pin "E1") (pinfunction "IN2_E1") (pintype "input"))
    )
    (net (code "640") (name "~{T_WRITE_OK}") (class "Default")
      (node (ref "A22") (pin "H2") (pinfunction "H2_H2") (pintype "input"))
      (node (ref "A24") (pin "L2") (pinfunction "P$2_L2") (pintype "bidirectional"))
      (node (ref "B23") (pin "L2") (pinfunction "P$1_L2") (pintype "passive"))
    )
    (net (code "641") (name "~{U+M_DY}") (class "Default")
      (node (ref "C12") (pin "A1") (pinfunction "IN1_A1") (pintype "input"))
      (node (ref "C12") (pin "R2") (pinfunction "IN3_R2") (pintype "input"))
      (node (ref "D14") (pin "E2") (pinfunction "F2_E2") (pintype "output"))
      (node (ref "D14") (pin "N1") (pinfunction "N1_N1") (pintype "input"))
    )
    (net (code "642") (name "~{USR_00}") (class "Default")
      (node (ref "B03") (pin "A1") (pinfunction "A_A1") (pintype "input"))
      (node (ref "B07") (pin "F1") (pinfunction "F1_F1") (pintype "output"))
    )
    (net (code "643") (name "~{USR_01}") (class "Default")
      (node (ref "B03") (pin "B1") (pinfunction "B_B1") (pintype "input"))
      (node (ref "B07") (pin "J2") (pinfunction "J2_J2") (pintype "output"))
    )
    (net (code "644") (name "~{USR_02}") (class "Default")
      (node (ref "B03") (pin "F1") (pinfunction "A_F1") (pintype "input"))
      (node (ref "B07") (pin "M1") (pinfunction "M1_M1") (pintype "output"))
    )
    (net (code "645") (name "~{UTS}") (class "Default")
      (node (ref "C12") (pin "L2") (pinfunction "IN3_L2") (pintype "input"))
      (node (ref "C14") (pin "P2") (pinfunction "1_P2") (pintype "output"))
      (node (ref "C15") (pin "P2") (pinfunction "IN1_P2") (pintype "input"))
      (node (ref "C16") (pin "A1") (pinfunction "IN1_A1") (pintype "input"))
      (node (ref "C16") (pin "B1") (pinfunction "IN2_B1") (pintype "input"))
      (node (ref "C16") (pin "C1") (pinfunction "IN3_C1") (pintype "input"))
      (node (ref "C16") (pin "D1") (pinfunction "IN4_D1") (pintype "input"))
      (node (ref "C16") (pin "F1") (pinfunction "IN1_F1") (pintype "input"))
      (node (ref "C16") (pin "H1") (pinfunction "IN2_H1") (pintype "input"))
      (node (ref "C16") (pin "J1") (pinfunction "IN3_J1") (pintype "input"))
      (node (ref "C16") (pin "K1") (pinfunction "IN4_K1") (pintype "input"))
    )
    (net (code "646") (name "~{W-INH}") (class "Default")
      (node (ref "A08") (pin "V2") (pinfunction "1_V2") (pintype "output"))
      (node (ref "B11") (pin "L1") (pinfunction "IN2_L1") (pintype "input"))
      (node (ref "B12") (pin "H1") (pinfunction "IN2_H1") (pintype "input"))
    )
    (net (code "647") (name "~{WB00}") (class "Default")
      (node (ref "A21") (pin "P2") (pinfunction "P2_P2") (pintype "input"))
      (node (ref "B18") (pin "P2") (pinfunction "P2_P2") (pintype "input"))
      (node (ref "C10") (pin "D1") (pinfunction "IN2B_D1") (pintype "input"))
      (node (ref "C14") (pin "E1") (pinfunction "1_E1") (pintype "output"))
    )
    (net (code "648") (name "~{WB01}") (class "Default")
      (node (ref "B20") (pin "P2") (pinfunction "P2_P2") (pintype "input"))
      (node (ref "C10") (pin "K1") (pinfunction "IN2B_K1") (pintype "input"))
      (node (ref "C14") (pin "H2") (pinfunction "1_H2") (pintype "output"))
    )
    (net (code "649") (name "~{WB02}") (class "Default")
      (node (ref "A20") (pin "P2") (pinfunction "P2_P2") (pintype "input"))
      (node (ref "C10") (pin "R1") (pinfunction "IN2B_R1") (pintype "input"))
      (node (ref "C14") (pin "L1") (pinfunction "1_L1") (pintype "output"))
    )
    (net (code "650") (name "~{WC0}") (class "Default")
      (node (ref "C06") (pin "N2") (pinfunction "OUT_N2") (pintype "output"))
      (node (ref "D11") (pin "R1") (pinfunction "S_R1") (pintype "input"))
    )
    (net (code "651") (name "~{WC}") (class "Default")
      (node (ref "B12") (pin "F2") (pinfunction "IN3_F2") (pintype "input"))
      (node (ref "C12") (pin "T2") (pinfunction "IN1_T2") (pintype "input"))
      (node (ref "D11") (pin "M2") (pinfunction "D_M2") (pintype "input"))
      (node (ref "D11") (pin "U1") (pinfunction "0_U1") (pintype "output"))
    )
    (net (code "652") (name "~{WRITE_ALL}") (class "Default")
      (node (ref "D07") (pin "M1") (pinfunction "~{O5}_M1") (pintype "output"))
    )
    (net (code "653") (name "~{WRITE_DATA}") (class "Default")
      (node (ref "B08") (pin "M2") (pinfunction "IN2_M2") (pintype "input"))
      (node (ref "D07") (pin "F1") (pinfunction "~{O4}_F1") (pintype "output"))
    )
    (net (code "654") (name "~{WRITE_OK}") (class "Default")
      (node (ref "A10") (pin "J1") (pinfunction "IN2_J1") (pintype "input"))
      (node (ref "C17") (pin "J2") (pinfunction "OUT_J2") (pintype "output"))
    )
    (net (code "655") (name "~{WRTM}") (class "Default")
      (node (ref "B08") (pin "H2") (pinfunction "IN1_H2") (pintype "input"))
      (node (ref "C10") (pin "M2") (pinfunction "IN2A_M2") (pintype "input"))
      (node (ref "D07") (pin "H1") (pinfunction "~{O6}_H1") (pintype "output"))
    )
    (net (code "656") (name "~{WR_EN}") (class "Default")
      (node (ref "B11") (pin "F1") (pinfunction "IN2_F1") (pintype "input"))
      (node (ref "C11") (pin "H2") (pinfunction "IN1_H2") (pintype "input"))
      (node (ref "C12") (pin "J2") (pinfunction "IN1_J2") (pintype "input"))
      (node (ref "C14") (pin "S1") (pinfunction "1_S1") (pintype "output"))
      (node (ref "C15") (pin "D2") (pinfunction "IN1_D2") (pintype "input"))
      (node (ref "C15") (pin "H2") (pinfunction "IN1_H2") (pintype "input"))
    )
    (net (code "657") (name "~{XSAD}") (class "Default")
      (node (ref "A11") (pin "K2") (pinfunction "IN_K2") (pintype "input"))
      (node (ref "D13") (pin "L2") (pinfunction "F2_L2") (pintype "output"))
    )
    (net (code "658") (name "~{XSTA}") (class "Default")
      (node (ref "B08") (pin "R2") (pinfunction "IN2_R2") (pintype "input"))
      (node (ref "C04") (pin "F1") (pinfunction "F1_F1") (pintype "output"))
      (node (ref "D13") (pin "H2") (pinfunction "H2_H2") (pintype "input"))
      (node (ref "D13") (pin "J2") (pinfunction "J2_J2") (pintype "input"))
      (node (ref "D13") (pin "K2") (pinfunction "K2_K2") (pintype "input"))
      (node (ref "D14") (pin "K2") (pinfunction "U1_K2") (pintype "input"))
      (node (ref "D14") (pin "L2") (pinfunction "S1_L2") (pintype "input"))
      (node (ref "D16") (pin "M2") (pinfunction "H2_M2") (pintype "input"))
      (node (ref "D16") (pin "N2") (pinfunction "J2_N2") (pintype "input"))
    )
  )
)
